# bm812i.net
KiCad netlist of a schematic drawn in EAGLE
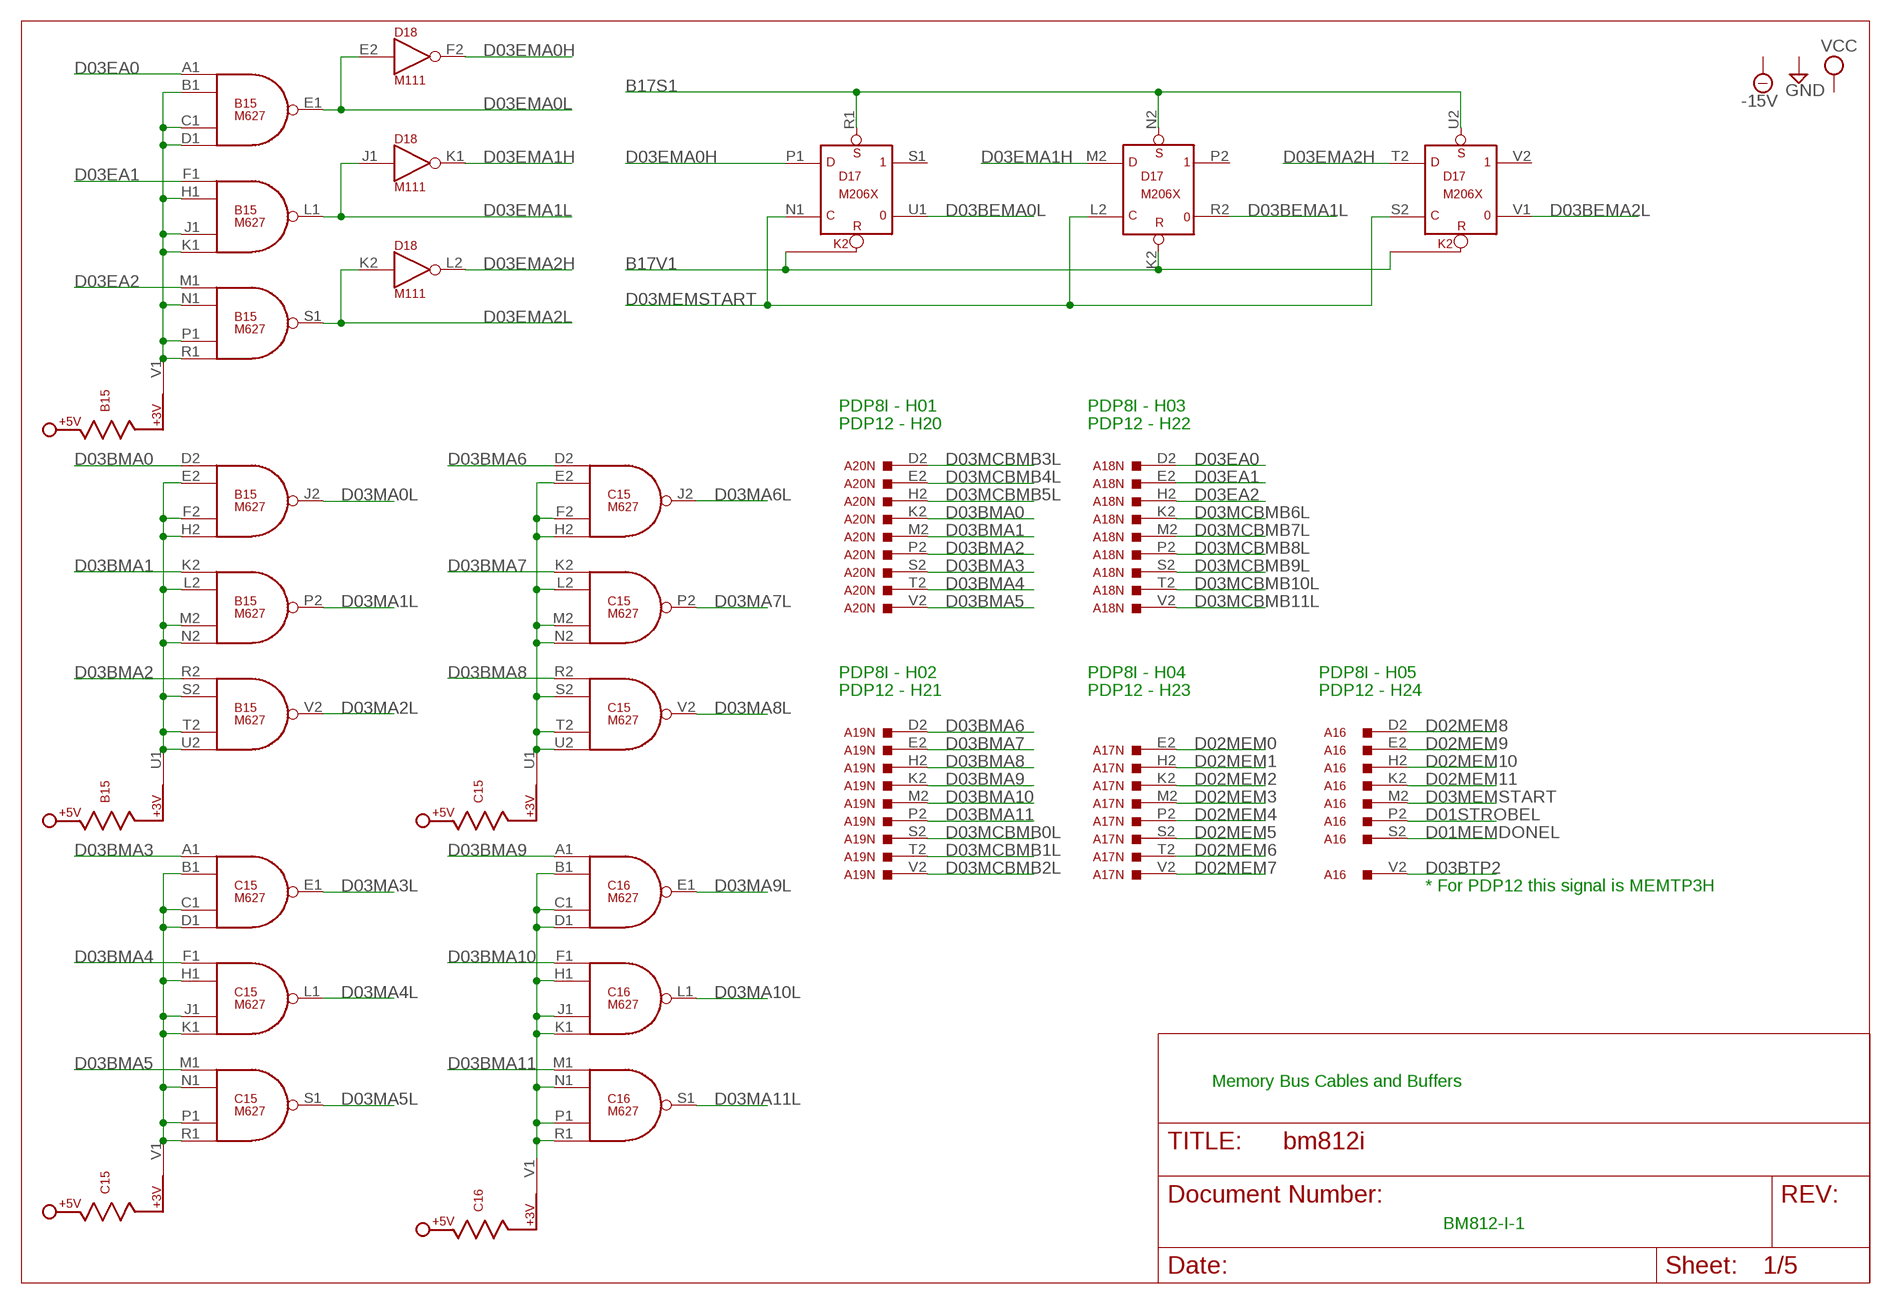
[diagram p0: schematic, sheet 1]
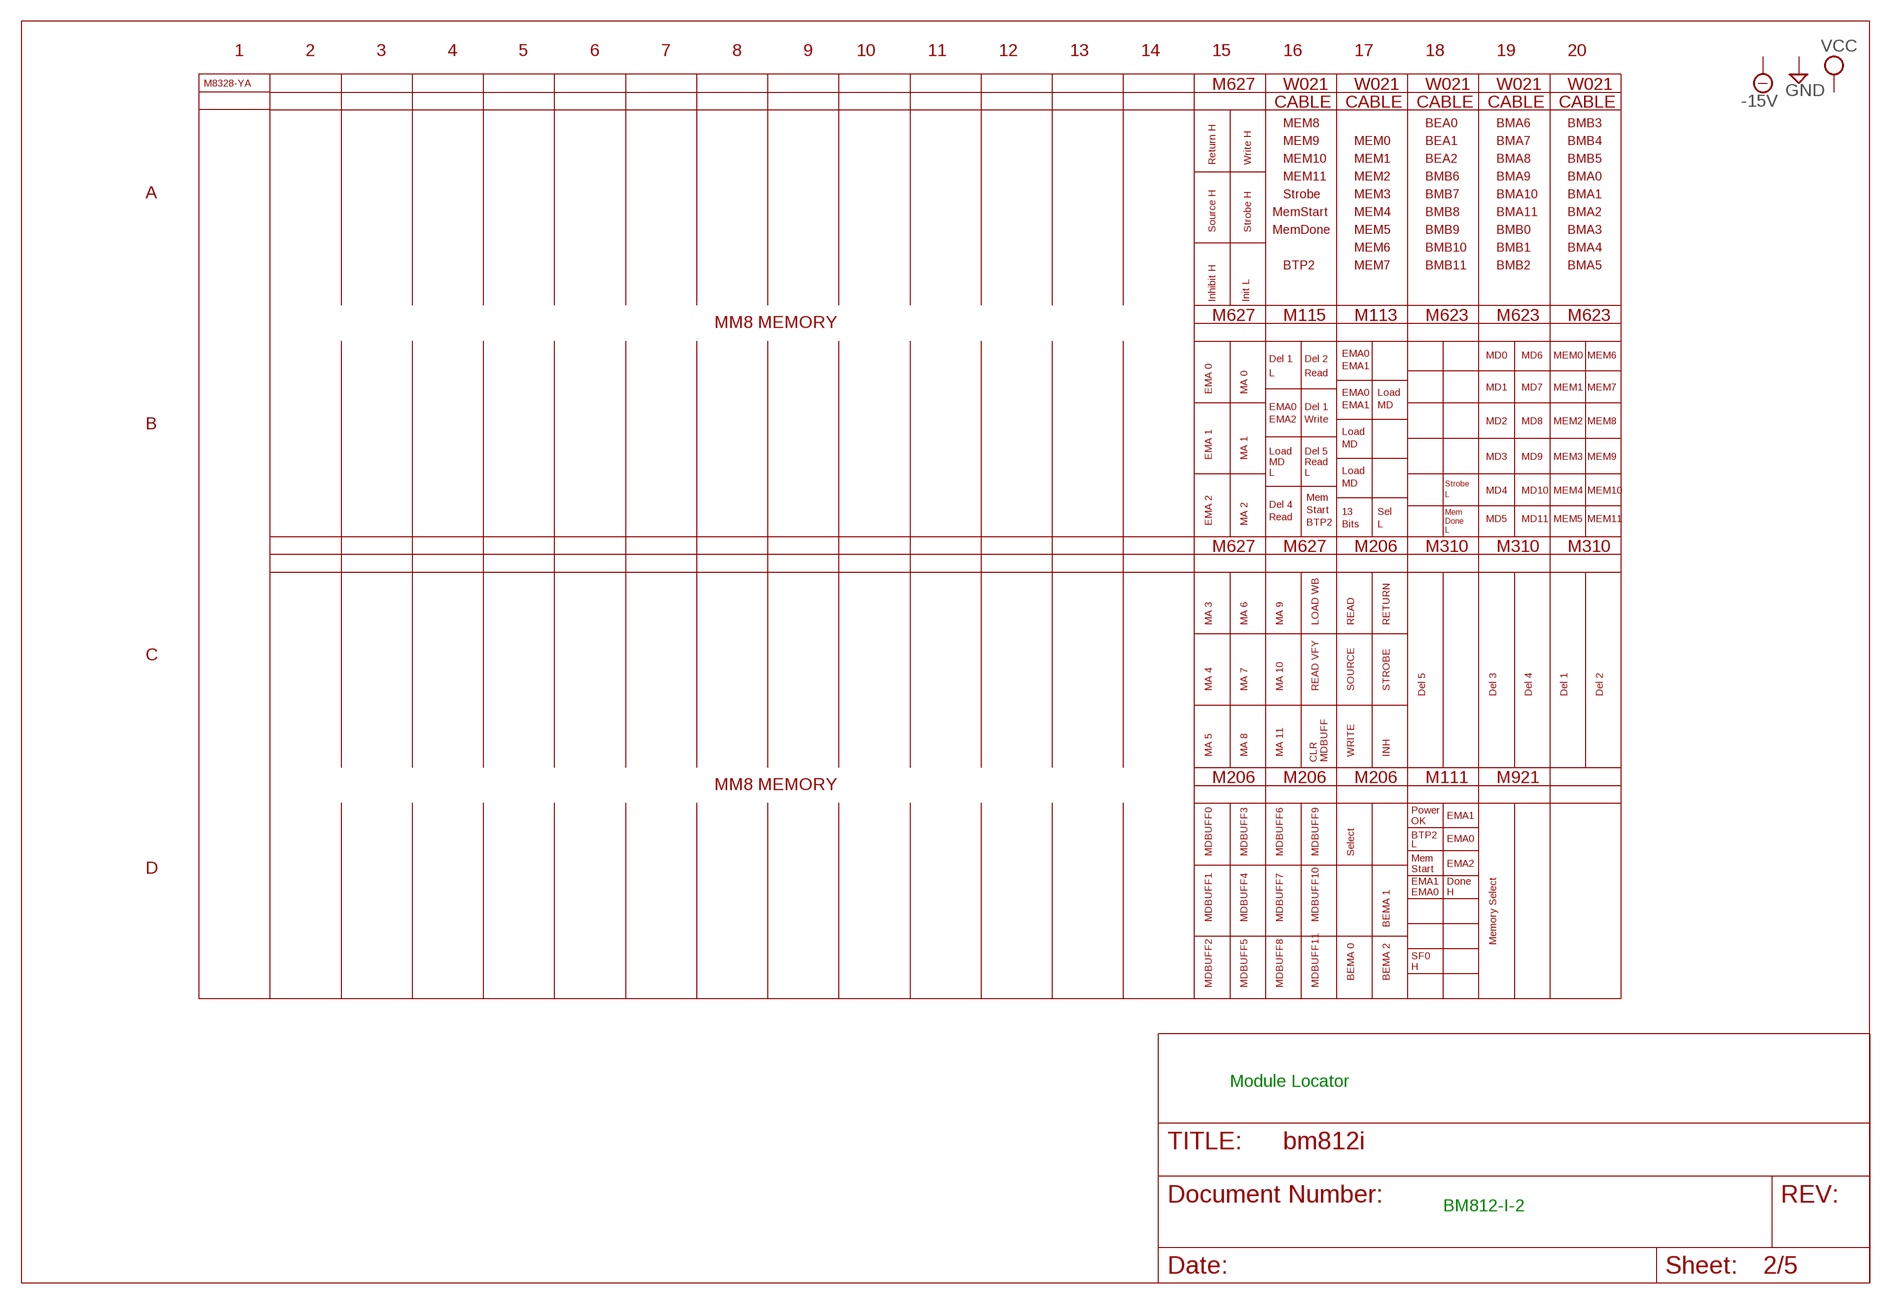
[diagram p1: schematic, sheet 2]
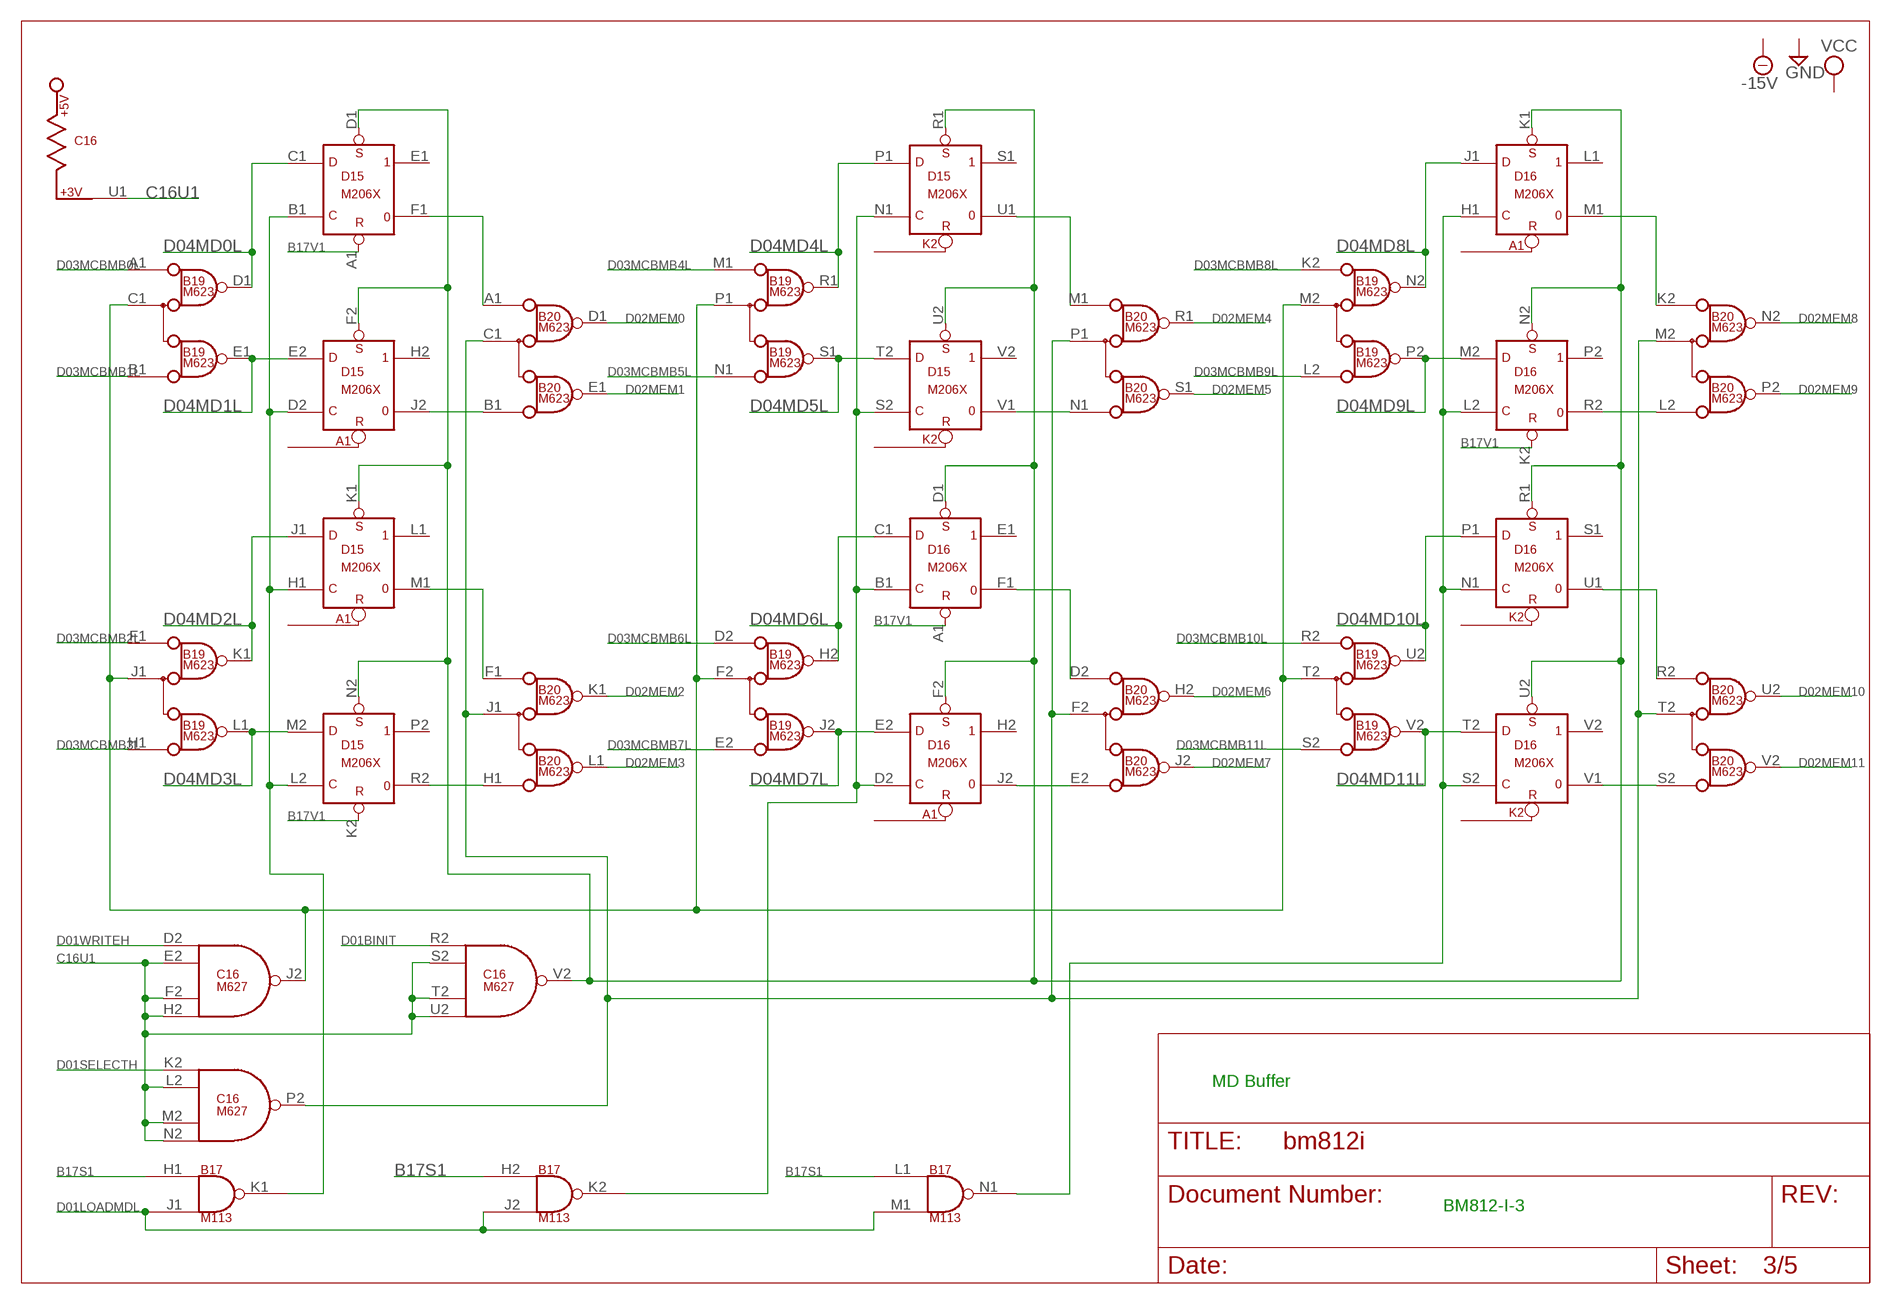
[diagram p2: schematic, sheet 3]
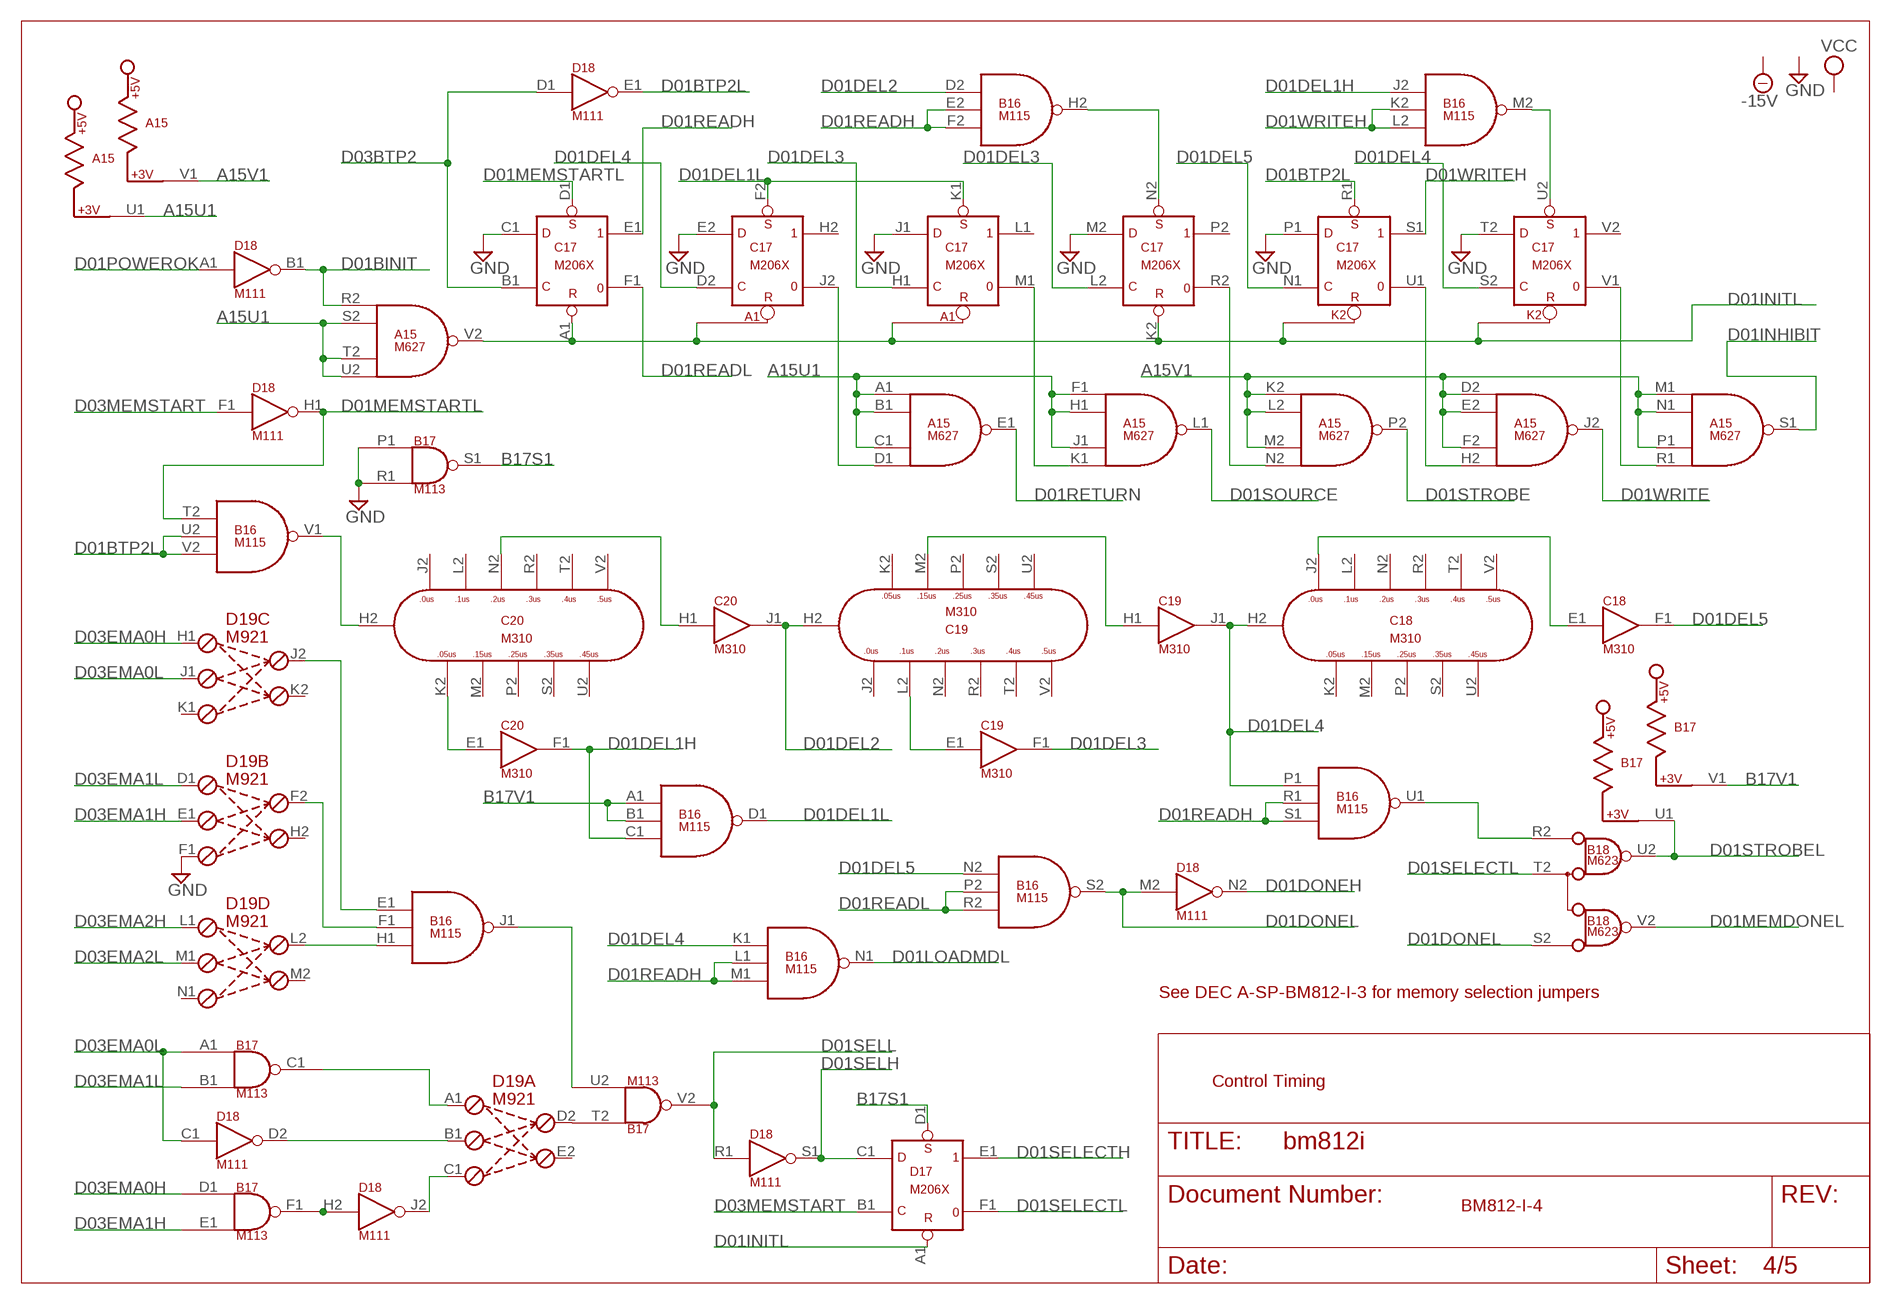
[diagram p3: schematic, sheet 4]
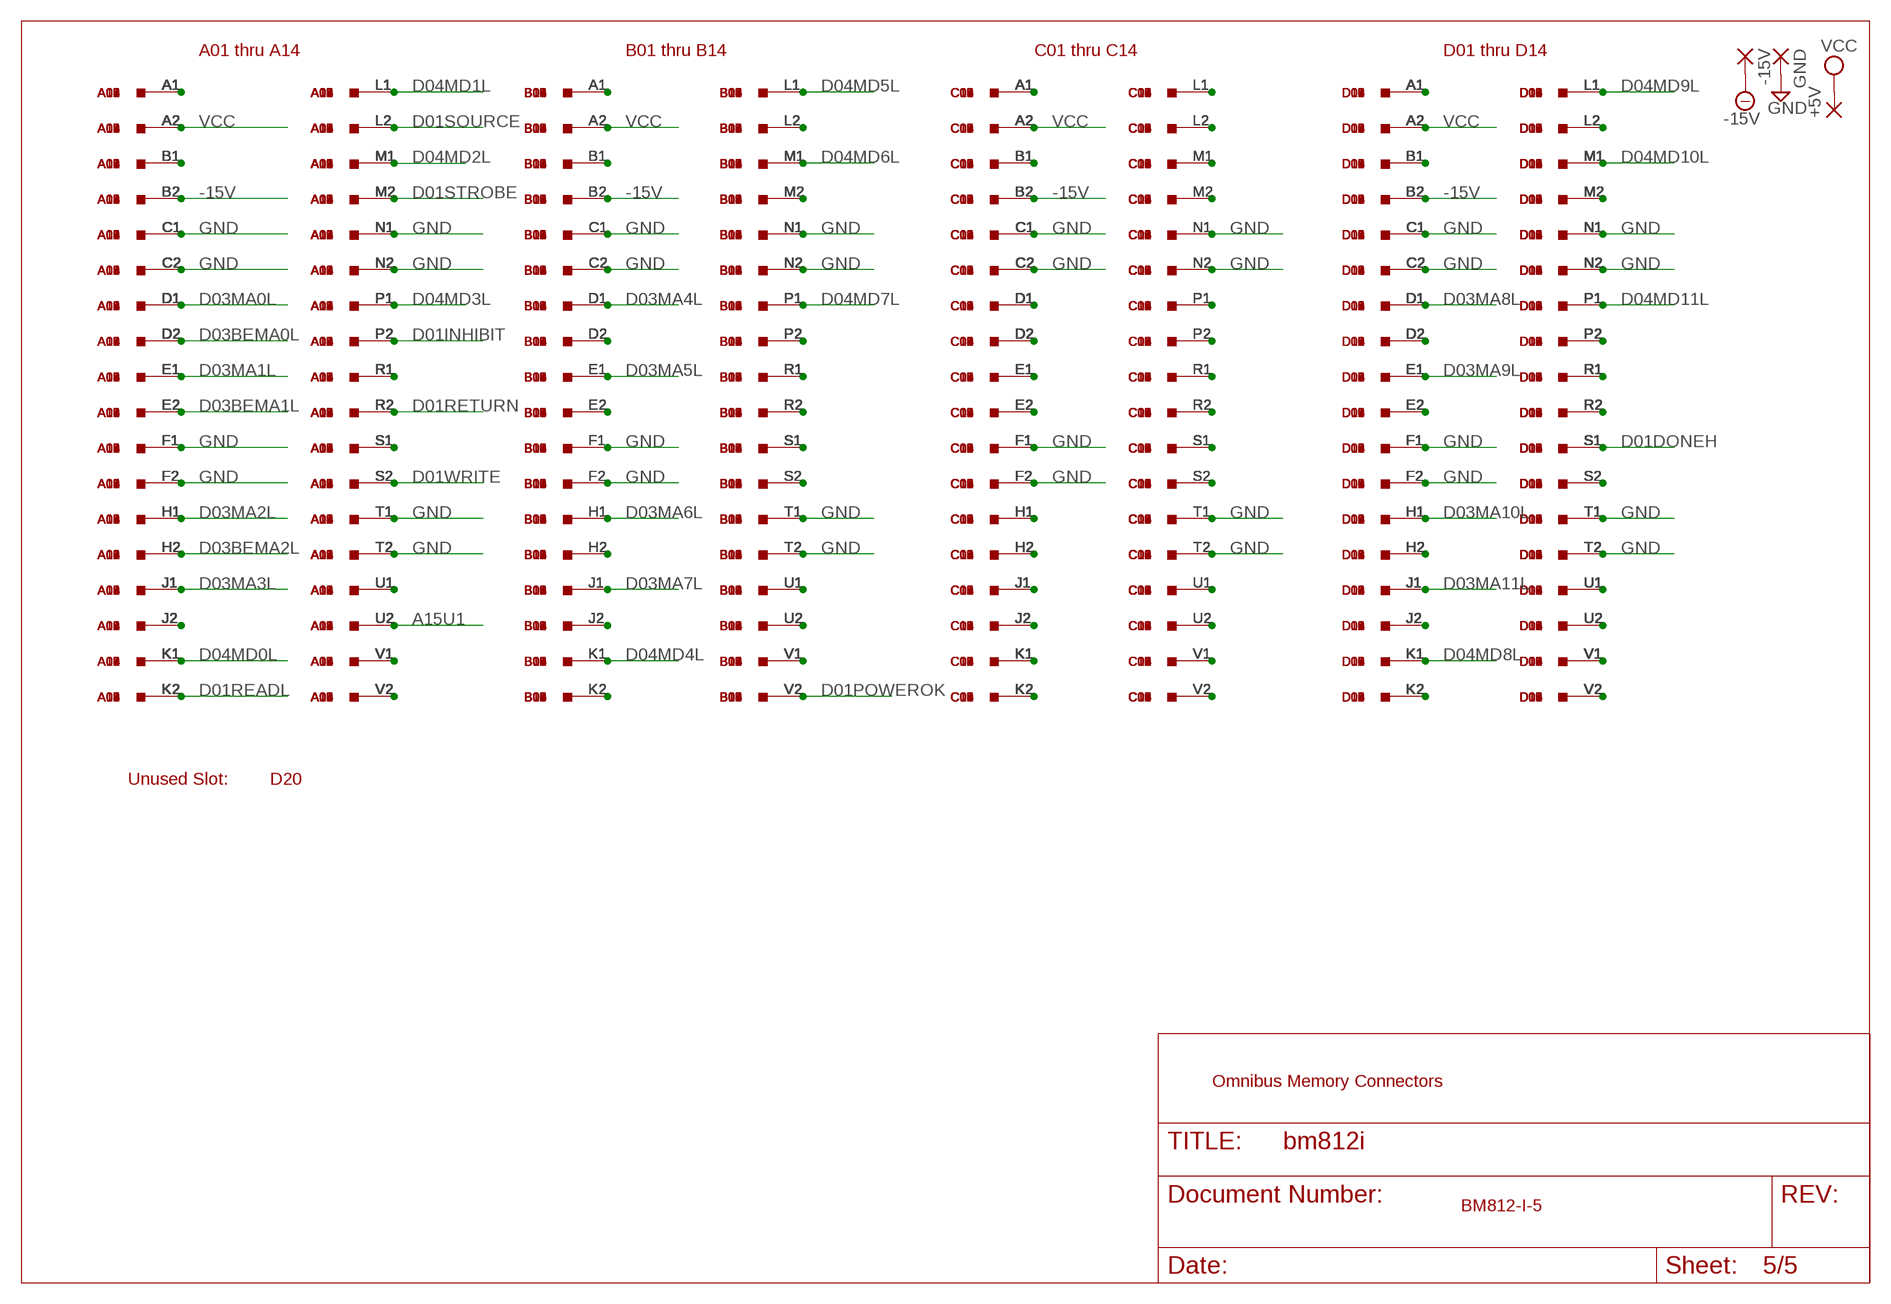
[diagram p4: schematic, sheet 5]

(export (version "E")
  (design (tool "Eeschema 10.0.6"))
  (components
    (comp (ref "+5V")
      (value "2,54/0,8")
      (footprint "eagle-import:2,54_0,8")
      (libsource (lib "eagle-import") (part "2,54/0,8"))
    )
    (comp (ref "-15V")
      (value "2,54/0,8")
      (footprint "eagle-import:2,54_0,8")
      (libsource (lib "eagle-import") (part "2,54/0,8"))
    )
    (comp (ref "A01")
      (value "M916")
      (footprint "eagle-import:H807")
      (libsource (lib "eagle-import") (part "M916"))
    )
    (comp (ref "A02")
      (value "M916")
      (footprint "eagle-import:H807")
      (libsource (lib "eagle-import") (part "M916"))
    )
    (comp (ref "A03")
      (value "M916")
      (footprint "eagle-import:H807")
      (libsource (lib "eagle-import") (part "M916"))
    )
    (comp (ref "A04")
      (value "M916")
      (footprint "eagle-import:H807")
      (libsource (lib "eagle-import") (part "M916"))
    )
    (comp (ref "A05")
      (value "M916")
      (footprint "eagle-import:H807")
      (libsource (lib "eagle-import") (part "M916"))
    )
    (comp (ref "A06")
      (value "M916")
      (footprint "eagle-import:H807")
      (libsource (lib "eagle-import") (part "M916"))
    )
    (comp (ref "A07")
      (value "M916")
      (footprint "eagle-import:H807")
      (libsource (lib "eagle-import") (part "M916"))
    )
    (comp (ref "A08")
      (value "M916")
      (footprint "eagle-import:H807")
      (libsource (lib "eagle-import") (part "M916"))
    )
    (comp (ref "A09")
      (value "M916")
      (footprint "eagle-import:H807")
      (libsource (lib "eagle-import") (part "M916"))
    )
    (comp (ref "A10")
      (value "M916")
      (footprint "eagle-import:H807")
      (libsource (lib "eagle-import") (part "M916"))
    )
    (comp (ref "A11")
      (value "M916")
      (footprint "eagle-import:H807")
      (libsource (lib "eagle-import") (part "M916"))
    )
    (comp (ref "A12")
      (value "M916")
      (footprint "eagle-import:H807")
      (libsource (lib "eagle-import") (part "M916"))
    )
    (comp (ref "A13")
      (value "M916")
      (footprint "eagle-import:H807")
      (libsource (lib "eagle-import") (part "M916"))
    )
    (comp (ref "A14")
      (value "M916")
      (footprint "eagle-import:H807")
      (libsource (lib "eagle-import") (part "M916"))
    )
    (comp (ref "B01")
      (value "M916")
      (footprint "eagle-import:H807")
      (libsource (lib "eagle-import") (part "M916"))
    )
    (comp (ref "B02")
      (value "M916")
      (footprint "eagle-import:H807")
      (libsource (lib "eagle-import") (part "M916"))
    )
    (comp (ref "B03")
      (value "M916")
      (footprint "eagle-import:H807")
      (libsource (lib "eagle-import") (part "M916"))
    )
    (comp (ref "B04")
      (value "M916")
      (footprint "eagle-import:H807")
      (libsource (lib "eagle-import") (part "M916"))
    )
    (comp (ref "B05")
      (value "M916")
      (footprint "eagle-import:H807")
      (libsource (lib "eagle-import") (part "M916"))
    )
    (comp (ref "B06")
      (value "M916")
      (footprint "eagle-import:H807")
      (libsource (lib "eagle-import") (part "M916"))
    )
    (comp (ref "B07")
      (value "M916")
      (footprint "eagle-import:H807")
      (libsource (lib "eagle-import") (part "M916"))
    )
    (comp (ref "B08")
      (value "M916")
      (footprint "eagle-import:H807")
      (libsource (lib "eagle-import") (part "M916"))
    )
    (comp (ref "B09")
      (value "M916")
      (footprint "eagle-import:H807")
      (libsource (lib "eagle-import") (part "M916"))
    )
    (comp (ref "B10")
      (value "M916")
      (footprint "eagle-import:H807")
      (libsource (lib "eagle-import") (part "M916"))
    )
    (comp (ref "B11")
      (value "M916")
      (footprint "eagle-import:H807")
      (libsource (lib "eagle-import") (part "M916"))
    )
    (comp (ref "B12")
      (value "M916")
      (footprint "eagle-import:H807")
      (libsource (lib "eagle-import") (part "M916"))
    )
    (comp (ref "B13")
      (value "M916")
      (footprint "eagle-import:H807")
      (libsource (lib "eagle-import") (part "M916"))
    )
    (comp (ref "B14")
      (value "M916")
      (footprint "eagle-import:H807")
      (libsource (lib "eagle-import") (part "M916"))
    )
    (comp (ref "C01")
      (value "M916")
      (footprint "eagle-import:H807")
      (libsource (lib "eagle-import") (part "M916"))
    )
    (comp (ref "C02")
      (value "M916")
      (footprint "eagle-import:H807")
      (libsource (lib "eagle-import") (part "M916"))
    )
    (comp (ref "C03")
      (value "M916")
      (footprint "eagle-import:H807")
      (libsource (lib "eagle-import") (part "M916"))
    )
    (comp (ref "C04")
      (value "M916")
      (footprint "eagle-import:H807")
      (libsource (lib "eagle-import") (part "M916"))
    )
    (comp (ref "C05")
      (value "M916")
      (footprint "eagle-import:H807")
      (libsource (lib "eagle-import") (part "M916"))
    )
    (comp (ref "C06")
      (value "M916")
      (footprint "eagle-import:H807")
      (libsource (lib "eagle-import") (part "M916"))
    )
    (comp (ref "C07")
      (value "M916")
      (footprint "eagle-import:H807")
      (libsource (lib "eagle-import") (part "M916"))
    )
    (comp (ref "C08")
      (value "M916")
      (footprint "eagle-import:H807")
      (libsource (lib "eagle-import") (part "M916"))
    )
    (comp (ref "C09")
      (value "M916")
      (footprint "eagle-import:H807")
      (libsource (lib "eagle-import") (part "M916"))
    )
    (comp (ref "C10")
      (value "M916")
      (footprint "eagle-import:H807")
      (libsource (lib "eagle-import") (part "M916"))
    )
    (comp (ref "C11")
      (value "M916")
      (footprint "eagle-import:H807")
      (libsource (lib "eagle-import") (part "M916"))
    )
    (comp (ref "C12")
      (value "M916")
      (footprint "eagle-import:H807")
      (libsource (lib "eagle-import") (part "M916"))
    )
    (comp (ref "C13")
      (value "M916")
      (footprint "eagle-import:H807")
      (libsource (lib "eagle-import") (part "M916"))
    )
    (comp (ref "C14")
      (value "M916")
      (footprint "eagle-import:H807")
      (libsource (lib "eagle-import") (part "M916"))
    )
    (comp (ref "D01")
      (value "M916")
      (footprint "eagle-import:H807")
      (libsource (lib "eagle-import") (part "M916"))
    )
    (comp (ref "D02")
      (value "M916")
      (footprint "eagle-import:H807")
      (libsource (lib "eagle-import") (part "M916"))
    )
    (comp (ref "D03")
      (value "M916")
      (footprint "eagle-import:H807")
      (libsource (lib "eagle-import") (part "M916"))
    )
    (comp (ref "D04")
      (value "M916")
      (footprint "eagle-import:H807")
      (libsource (lib "eagle-import") (part "M916"))
    )
    (comp (ref "D05")
      (value "M916")
      (footprint "eagle-import:H807")
      (libsource (lib "eagle-import") (part "M916"))
    )
    (comp (ref "D06")
      (value "M916")
      (footprint "eagle-import:H807")
      (libsource (lib "eagle-import") (part "M916"))
    )
    (comp (ref "D07")
      (value "M916")
      (footprint "eagle-import:H807")
      (libsource (lib "eagle-import") (part "M916"))
    )
    (comp (ref "D08")
      (value "M916")
      (footprint "eagle-import:H807")
      (libsource (lib "eagle-import") (part "M916"))
    )
    (comp (ref "D09")
      (value "M916")
      (footprint "eagle-import:H807")
      (libsource (lib "eagle-import") (part "M916"))
    )
    (comp (ref "D10")
      (value "M916")
      (footprint "eagle-import:H807")
      (libsource (lib "eagle-import") (part "M916"))
    )
    (comp (ref "D11")
      (value "M916")
      (footprint "eagle-import:H807")
      (libsource (lib "eagle-import") (part "M916"))
    )
    (comp (ref "D12")
      (value "M916")
      (footprint "eagle-import:H807")
      (libsource (lib "eagle-import") (part "M916"))
    )
    (comp (ref "D13")
      (value "M916")
      (footprint "eagle-import:H807")
      (libsource (lib "eagle-import") (part "M916"))
    )
    (comp (ref "D14")
      (value "M916")
      (footprint "eagle-import:H807")
      (libsource (lib "eagle-import") (part "M916"))
    )
    (comp (ref "D20")
      (value "H807")
      (footprint "eagle-import:H807")
      (libsource (lib "eagle-import") (part "H807"))
    )
    (comp (ref "GND")
      (value "2,54/0,8")
      (footprint "eagle-import:2,54_0,8")
      (libsource (lib "eagle-import") (part "2,54/0,8"))
    )
    (comp (ref "A16")
      (value "M903")
      (footprint "eagle-import:H807")
      (libsource (lib "eagle-import") (part "M903"))
    )
    (comp (ref "A17N")
      (value "M903")
      (footprint "eagle-import:H807")
      (libsource (lib "eagle-import") (part "M903"))
    )
    (comp (ref "A18N")
      (value "M903")
      (footprint "eagle-import:H807")
      (libsource (lib "eagle-import") (part "M903"))
    )
    (comp (ref "A19N")
      (value "M903")
      (footprint "eagle-import:H807")
      (libsource (lib "eagle-import") (part "M903"))
    )
    (comp (ref "A20N")
      (value "M903")
      (footprint "eagle-import:H807")
      (libsource (lib "eagle-import") (part "M903"))
    )
    (comp (ref "B15")
      (value "M627")
      (footprint "eagle-import:H807")
      (libsource (lib "eagle-import") (part "M627"))
    )
    (comp (ref "C15")
      (value "M627")
      (footprint "eagle-import:H807")
      (libsource (lib "eagle-import") (part "M627"))
    )
    (comp (ref "C16")
      (value "M627")
      (footprint "eagle-import:H807")
      (libsource (lib "eagle-import") (part "M627"))
    )
    (comp (ref "D17")
      (value "M206X")
      (footprint "eagle-import:H807")
      (libsource (lib "eagle-import") (part "M206X"))
    )
    (comp (ref "D18")
      (value "M111")
      (footprint "eagle-import:H807")
      (libsource (lib "eagle-import") (part "M111"))
    )
    (comp (ref "A15")
      (value "M627")
      (footprint "eagle-import:H807")
      (libsource (lib "eagle-import") (part "M627"))
    )
    (comp (ref "B16")
      (value "M115")
      (footprint "eagle-import:H807")
      (libsource (lib "eagle-import") (part "M115"))
    )
    (comp (ref "B17")
      (value "M113")
      (footprint "eagle-import:H807")
      (libsource (lib "eagle-import") (part "M113"))
    )
    (comp (ref "B18")
      (value "M623")
      (footprint "eagle-import:H807")
      (libsource (lib "eagle-import") (part "M623"))
    )
    (comp (ref "C17")
      (value "M206X")
      (footprint "eagle-import:H807")
      (libsource (lib "eagle-import") (part "M206X"))
    )
    (comp (ref "C18")
      (value "M310")
      (footprint "eagle-import:H807")
      (libsource (lib "eagle-import") (part "M310"))
    )
    (comp (ref "C19")
      (value "M310")
      (footprint "eagle-import:H807")
      (libsource (lib "eagle-import") (part "M310"))
    )
    (comp (ref "C20")
      (value "M310")
      (footprint "eagle-import:H807")
      (libsource (lib "eagle-import") (part "M310"))
    )
    (comp (ref "D19")
      (value "M921")
      (footprint "eagle-import:H807")
      (libsource (lib "eagle-import") (part "M921"))
    )
    (comp (ref "B19")
      (value "M623")
      (footprint "eagle-import:H807")
      (libsource (lib "eagle-import") (part "M623"))
    )
    (comp (ref "B20")
      (value "M623")
      (footprint "eagle-import:H807")
      (libsource (lib "eagle-import") (part "M623"))
    )
    (comp (ref "D15")
      (value "M206X")
      (footprint "eagle-import:H807")
      (libsource (lib "eagle-import") (part "M206X"))
    )
    (comp (ref "D16")
      (value "M206X")
      (footprint "eagle-import:H807")
      (libsource (lib "eagle-import") (part "M206X"))
    )
  )
  (nets
    (net (code "1") (name "-15V") (class "Default")
      (node (ref "-15V") (pin "1") (pinfunction "P_1") (pintype "passive"))
      (node (ref "A01") (pin "B2") (pinfunction "P$2_B2") (pintype "bidirectional"))
      (node (ref "A02") (pin "B2") (pinfunction "P$2_B2") (pintype "bidirectional"))
      (node (ref "A03") (pin "B2") (pinfunction "P$2_B2") (pintype "bidirectional"))
      (node (ref "A04") (pin "B2") (pinfunction "P$2_B2") (pintype "bidirectional"))
      (node (ref "A05") (pin "B2") (pinfunction "P$2_B2") (pintype "bidirectional"))
      (node (ref "A06") (pin "B2") (pinfunction "P$2_B2") (pintype "bidirectional"))
      (node (ref "A07") (pin "B2") (pinfunction "P$2_B2") (pintype "bidirectional"))
      (node (ref "A08") (pin "B2") (pinfunction "P$2_B2") (pintype "bidirectional"))
      (node (ref "A09") (pin "B2") (pinfunction "P$2_B2") (pintype "bidirectional"))
      (node (ref "A10") (pin "B2") (pinfunction "P$2_B2") (pintype "bidirectional"))
      (node (ref "A11") (pin "B2") (pinfunction "P$2_B2") (pintype "bidirectional"))
      (node (ref "A12") (pin "B2") (pinfunction "P$2_B2") (pintype "bidirectional"))
      (node (ref "A13") (pin "B2") (pinfunction "P$2_B2") (pintype "bidirectional"))
      (node (ref "A14") (pin "B2") (pinfunction "P$2_B2") (pintype "bidirectional"))
      (node (ref "B01") (pin "B2") (pinfunction "P$2_B2") (pintype "bidirectional"))
      (node (ref "B02") (pin "B2") (pinfunction "P$2_B2") (pintype "bidirectional"))
      (node (ref "B03") (pin "B2") (pinfunction "P$2_B2") (pintype "bidirectional"))
      (node (ref "B04") (pin "B2") (pinfunction "P$2_B2") (pintype "bidirectional"))
      (node (ref "B05") (pin "B2") (pinfunction "P$2_B2") (pintype "bidirectional"))
      (node (ref "B06") (pin "B2") (pinfunction "P$2_B2") (pintype "bidirectional"))
      (node (ref "B07") (pin "B2") (pinfunction "P$2_B2") (pintype "bidirectional"))
      (node (ref "B08") (pin "B2") (pinfunction "P$2_B2") (pintype "bidirectional"))
      (node (ref "B09") (pin "B2") (pinfunction "P$2_B2") (pintype "bidirectional"))
      (node (ref "B10") (pin "B2") (pinfunction "P$2_B2") (pintype "bidirectional"))
      (node (ref "B11") (pin "B2") (pinfunction "P$2_B2") (pintype "bidirectional"))
      (node (ref "B12") (pin "B2") (pinfunction "P$2_B2") (pintype "bidirectional"))
      (node (ref "B13") (pin "B2") (pinfunction "P$2_B2") (pintype "bidirectional"))
      (node (ref "B14") (pin "B2") (pinfunction "P$2_B2") (pintype "bidirectional"))
      (node (ref "C01") (pin "B2") (pinfunction "P$2_B2") (pintype "bidirectional"))
      (node (ref "C02") (pin "B2") (pinfunction "P$2_B2") (pintype "bidirectional"))
      (node (ref "C03") (pin "B2") (pinfunction "P$2_B2") (pintype "bidirectional"))
      (node (ref "C04") (pin "B2") (pinfunction "P$2_B2") (pintype "bidirectional"))
      (node (ref "C05") (pin "B2") (pinfunction "P$2_B2") (pintype "bidirectional"))
      (node (ref "C06") (pin "B2") (pinfunction "P$2_B2") (pintype "bidirectional"))
      (node (ref "C07") (pin "B2") (pinfunction "P$2_B2") (pintype "bidirectional"))
      (node (ref "C08") (pin "B2") (pinfunction "P$2_B2") (pintype "bidirectional"))
      (node (ref "C09") (pin "B2") (pinfunction "P$2_B2") (pintype "bidirectional"))
      (node (ref "C10") (pin "B2") (pinfunction "P$2_B2") (pintype "bidirectional"))
      (node (ref "C11") (pin "B2") (pinfunction "P$2_B2") (pintype "bidirectional"))
      (node (ref "C12") (pin "B2") (pinfunction "P$2_B2") (pintype "bidirectional"))
      (node (ref "C13") (pin "B2") (pinfunction "P$2_B2") (pintype "bidirectional"))
      (node (ref "C14") (pin "B2") (pinfunction "P$2_B2") (pintype "bidirectional"))
      (node (ref "D01") (pin "B2") (pinfunction "P$2_B2") (pintype "bidirectional"))
      (node (ref "D02") (pin "B2") (pinfunction "P$2_B2") (pintype "bidirectional"))
      (node (ref "D03") (pin "B2") (pinfunction "P$2_B2") (pintype "bidirectional"))
      (node (ref "D04") (pin "B2") (pinfunction "P$2_B2") (pintype "bidirectional"))
      (node (ref "D05") (pin "B2") (pinfunction "P$2_B2") (pintype "bidirectional"))
      (node (ref "D06") (pin "B2") (pinfunction "P$2_B2") (pintype "bidirectional"))
      (node (ref "D07") (pin "B2") (pinfunction "P$2_B2") (pintype "bidirectional"))
      (node (ref "D08") (pin "B2") (pinfunction "P$2_B2") (pintype "bidirectional"))
      (node (ref "D09") (pin "B2") (pinfunction "P$2_B2") (pintype "bidirectional"))
      (node (ref "D10") (pin "B2") (pinfunction "P$2_B2") (pintype "bidirectional"))
      (node (ref "D11") (pin "B2") (pinfunction "P$2_B2") (pintype "bidirectional"))
      (node (ref "D12") (pin "B2") (pinfunction "P$2_B2") (pintype "bidirectional"))
      (node (ref "D13") (pin "B2") (pinfunction "P$2_B2") (pintype "bidirectional"))
      (node (ref "D14") (pin "B2") (pinfunction "P$2_B2") (pintype "bidirectional"))
    )
    (net (code "2") (name "A15U1") (class "Default")
      (node (ref "A01") (pin "U2") (pinfunction "P$2_U2") (pintype "bidirectional"))
      (node (ref "A02") (pin "U2") (pinfunction "P$2_U2") (pintype "bidirectional"))
      (node (ref "A03") (pin "U2") (pinfunction "P$2_U2") (pintype "bidirectional"))
      (node (ref "A04") (pin "U2") (pinfunction "P$2_U2") (pintype "bidirectional"))
      (node (ref "A05") (pin "U2") (pinfunction "P$2_U2") (pintype "bidirectional"))
      (node (ref "A06") (pin "U2") (pinfunction "P$2_U2") (pintype "bidirectional"))
      (node (ref "A07") (pin "U2") (pinfunction "P$2_U2") (pintype "bidirectional"))
      (node (ref "A08") (pin "U2") (pinfunction "P$2_U2") (pintype "bidirectional"))
      (node (ref "A09") (pin "U2") (pinfunction "P$2_U2") (pintype "bidirectional"))
      (node (ref "A10") (pin "U2") (pinfunction "P$2_U2") (pintype "bidirectional"))
      (node (ref "A11") (pin "U2") (pinfunction "P$2_U2") (pintype "bidirectional"))
      (node (ref "A12") (pin "U2") (pinfunction "P$2_U2") (pintype "bidirectional"))
      (node (ref "A13") (pin "U2") (pinfunction "P$2_U2") (pintype "bidirectional"))
      (node (ref "A14") (pin "U2") (pinfunction "P$2_U2") (pintype "bidirectional"))
      (node (ref "A15") (pin "A1") (pinfunction "IN1_A1") (pintype "input"))
      (node (ref "A15") (pin "B1") (pinfunction "IN2_B1") (pintype "input"))
      (node (ref "A15") (pin "C1") (pinfunction "IN3_C1") (pintype "input"))
      (node (ref "A15") (pin "F1") (pinfunction "IN1_F1") (pintype "input"))
      (node (ref "A15") (pin "H1") (pinfunction "IN2_H1") (pintype "input"))
      (node (ref "A15") (pin "J1") (pinfunction "IN3_J1") (pintype "input"))
      (node (ref "A15") (pin "S2") (pinfunction "IN2_S2") (pintype "input"))
      (node (ref "A15") (pin "T2") (pinfunction "IN3_T2") (pintype "input"))
      (node (ref "A15") (pin "U1") (pinfunction "P$1_U1") (pintype "passive"))
      (node (ref "A15") (pin "U2") (pinfunction "IN4_U2") (pintype "input"))
    )
    (net (code "3") (name "A15V1") (class "Default")
      (node (ref "A15") (pin "D2") (pinfunction "IN1_D2") (pintype "input"))
      (node (ref "A15") (pin "E2") (pinfunction "IN2_E2") (pintype "input"))
      (node (ref "A15") (pin "F2") (pinfunction "IN3_F2") (pintype "input"))
      (node (ref "A15") (pin "K2") (pinfunction "IN1_K2") (pintype "input"))
      (node (ref "A15") (pin "L2") (pinfunction "IN2_L2") (pintype "input"))
      (node (ref "A15") (pin "M1") (pinfunction "IN1_M1") (pintype "input"))
      (node (ref "A15") (pin "M2") (pinfunction "IN3_M2") (pintype "input"))
      (node (ref "A15") (pin "N1") (pinfunction "IN2_N1") (pintype "input"))
      (node (ref "A15") (pin "P1") (pinfunction "IN3_P1") (pintype "input"))
      (node (ref "A15") (pin "V1") (pinfunction "P$1_V1") (pintype "passive"))
    )
    (net (code "4") (name "B17S1") (class "Default")
      (node (ref "B17") (pin "H1") (pinfunction "IN1_H1") (pintype "input"))
      (node (ref "B17") (pin "H2") (pinfunction "IN1_H2") (pintype "input"))
      (node (ref "B17") (pin "L1") (pinfunction "IN1_L1") (pintype "input"))
      (node (ref "B17") (pin "S1") (pinfunction "OUT_S1") (pintype "output"))
      (node (ref "D17") (pin "D1") (pinfunction "S_D1") (pintype "input"))
      (node (ref "D17") (pin "N2") (pinfunction "S_N2") (pintype "input"))
      (node (ref "D17") (pin "R1") (pinfunction "S_R1") (pintype "input"))
      (node (ref "D17") (pin "U2") (pinfunction "S_U2") (pintype "input"))
    )
    (net (code "5") (name "B17V1") (class "Default")
      (node (ref "B16") (pin "A1") (pinfunction "IN1_A1") (pintype "input"))
      (node (ref "B16") (pin "B1") (pinfunction "IN2_B1") (pintype "input"))
      (node (ref "B17") (pin "V1") (pinfunction "P$1_V1") (pintype "passive"))
      (node (ref "D15") (pin "A1") (pinfunction "R_A1") (pintype "input"))
      (node (ref "D15") (pin "K2") (pinfunction "R_K2") (pintype "input"))
      (node (ref "D16") (pin "A1") (pinfunction "R_A1") (pintype "input"))
      (node (ref "D16") (pin "K2") (pinfunction "R_K2") (pintype "input"))
      (node (ref "D17") (pin "K2") (pinfunction "R_K2") (pintype "input"))
    )
    (net (code "6") (name "C16U1") (class "Default")
      (node (ref "C16") (pin "E2") (pinfunction "IN2_E2") (pintype "input"))
      (node (ref "C16") (pin "F2") (pinfunction "IN3_F2") (pintype "input"))
      (node (ref "C16") (pin "H2") (pinfunction "IN4_H2") (pintype "input"))
      (node (ref "C16") (pin "L2") (pinfunction "IN2_L2") (pintype "input"))
      (node (ref "C16") (pin "M2") (pinfunction "IN3_M2") (pintype "input"))
      (node (ref "C16") (pin "N2") (pinfunction "IN4_N2") (pintype "input"))
      (node (ref "C16") (pin "S2") (pinfunction "IN2_S2") (pintype "input"))
      (node (ref "C16") (pin "T2") (pinfunction "IN3_T2") (pintype "input"))
      (node (ref "C16") (pin "U1") (pinfunction "P$1_U1") (pintype "passive"))
      (node (ref "C16") (pin "U2") (pinfunction "IN4_U2") (pintype "input"))
    )
    (net (code "7") (name "D01BINIT") (class "Default")
      (node (ref "A15") (pin "R2") (pinfunction "IN1_R2") (pintype "input"))
      (node (ref "C16") (pin "R2") (pinfunction "IN1_R2") (pintype "input"))
      (node (ref "D18") (pin "B1") (pinfunction "OUT_B1") (pintype "output"))
    )
    (net (code "8") (name "D01BTP2L") (class "Default")
      (node (ref "B16") (pin "U2") (pinfunction "IN2_U2") (pintype "input"))
      (node (ref "B16") (pin "V2") (pinfunction "IN3_V2") (pintype "input"))
      (node (ref "C17") (pin "R1") (pinfunction "S_R1") (pintype "input"))
      (node (ref "D18") (pin "E1") (pinfunction "OUT_E1") (pintype "output"))
    )
    (net (code "9") (name "D01DEL1H") (class "Default")
      (node (ref "B16") (pin "C1") (pinfunction "IN3_C1") (pintype "input"))
      (node (ref "B16") (pin "J2") (pinfunction "IN1_J2") (pintype "input"))
      (node (ref "C20") (pin "F1") (pinfunction "OUT_F1") (pintype "output"))
    )
    (net (code "10") (name "D01DEL1L") (class "Default")
      (node (ref "B16") (pin "D1") (pinfunction "OUT_D1") (pintype "output"))
      (node (ref "C17") (pin "F2") (pinfunction "S_F2") (pintype "input"))
      (node (ref "C17") (pin "K1") (pinfunction "S_K1") (pintype "input"))
    )
    (net (code "11") (name "D01DEL2") (class "Default")
      (node (ref "B16") (pin "D2") (pinfunction "IN1_D2") (pintype "input"))
      (node (ref "C19") (pin "H2") (pinfunction "H2_H2") (pintype "input"))
      (node (ref "C20") (pin "J1") (pinfunction "OUT_J1") (pintype "output"))
    )
    (net (code "12") (name "D01DEL3") (class "Default")
      (node (ref "C17") (pin "H1") (pinfunction "C_H1") (pintype "input"))
      (node (ref "C17") (pin "L2") (pinfunction "C_L2") (pintype "input"))
      (node (ref "C19") (pin "F1") (pinfunction "OUT_F1") (pintype "output"))
    )
    (net (code "13") (name "D01DEL4") (class "Default")
      (node (ref "B16") (pin "K1") (pinfunction "IN1_K1") (pintype "input"))
      (node (ref "B16") (pin "P1") (pinfunction "IN1_P1") (pintype "input"))
      (node (ref "C17") (pin "D2") (pinfunction "C_D2") (pintype "input"))
      (node (ref "C17") (pin "S2") (pinfunction "C_S2") (pintype "input"))
      (node (ref "C18") (pin "H2") (pinfunction "H2_H2") (pintype "input"))
      (node (ref "C19") (pin "J1") (pinfunction "OUT_J1") (pintype "output"))
    )
    (net (code "14") (name "D01DEL5") (class "Default")
      (node (ref "B16") (pin "N2") (pinfunction "IN1_N2") (pintype "input"))
      (node (ref "C17") (pin "N1") (pinfunction "C_N1") (pintype "input"))
      (node (ref "C18") (pin "F1") (pinfunction "OUT_F1") (pintype "output"))
    )
    (net (code "15") (name "D01DONEH") (class "Default")
      (node (ref "D01") (pin "S1") (pinfunction "P$2_S1") (pintype "bidirectional"))
      (node (ref "D02") (pin "S1") (pinfunction "P$2_S1") (pintype "bidirectional"))
      (node (ref "D03") (pin "S1") (pinfunction "P$2_S1") (pintype "bidirectional"))
      (node (ref "D04") (pin "S1") (pinfunction "P$2_S1") (pintype "bidirectional"))
      (node (ref "D05") (pin "S1") (pinfunction "P$2_S1") (pintype "bidirectional"))
      (node (ref "D06") (pin "S1") (pinfunction "P$2_S1") (pintype "bidirectional"))
      (node (ref "D07") (pin "S1") (pinfunction "P$2_S1") (pintype "bidirectional"))
      (node (ref "D08") (pin "S1") (pinfunction "P$2_S1") (pintype "bidirectional"))
      (node (ref "D09") (pin "S1") (pinfunction "P$2_S1") (pintype "bidirectional"))
      (node (ref "D10") (pin "S1") (pinfunction "P$2_S1") (pintype "bidirectional"))
      (node (ref "D11") (pin "S1") (pinfunction "P$2_S1") (pintype "bidirectional"))
      (node (ref "D12") (pin "S1") (pinfunction "P$2_S1") (pintype "bidirectional"))
      (node (ref "D13") (pin "S1") (pinfunction "P$2_S1") (pintype "bidirectional"))
      (node (ref "D14") (pin "S1") (pinfunction "P$2_S1") (pintype "bidirectional"))
      (node (ref "D18") (pin "N2") (pinfunction "OUT_N2") (pintype "output"))
    )
    (net (code "16") (name "D01DONEL") (class "Default")
      (node (ref "B16") (pin "S2") (pinfunction "OUT_S2") (pintype "output"))
      (node (ref "B18") (pin "S2") (pinfunction "B_S2") (pintype "input"))
      (node (ref "D18") (pin "M2") (pinfunction "IN_M2") (pintype "input"))
    )
    (net (code "17") (name "D01INHIBIT") (class "Default")
      (node (ref "A01") (pin "P2") (pinfunction "P$2_P2") (pintype "bidirectional"))
      (node (ref "A02") (pin "P2") (pinfunction "P$2_P2") (pintype "bidirectional"))
      (node (ref "A03") (pin "P2") (pinfunction "P$2_P2") (pintype "bidirectional"))
      (node (ref "A04") (pin "P2") (pinfunction "P$2_P2") (pintype "bidirectional"))
      (node (ref "A05") (pin "P2") (pinfunction "P$2_P2") (pintype "bidirectional"))
      (node (ref "A06") (pin "P2") (pinfunction "P$2_P2") (pintype "bidirectional"))
      (node (ref "A07") (pin "P2") (pinfunction "P$2_P2") (pintype "bidirectional"))
      (node (ref "A08") (pin "P2") (pinfunction "P$2_P2") (pintype "bidirectional"))
      (node (ref "A09") (pin "P2") (pinfunction "P$2_P2") (pintype "bidirectional"))
      (node (ref "A10") (pin "P2") (pinfunction "P$2_P2") (pintype "bidirectional"))
      (node (ref "A11") (pin "P2") (pinfunction "P$2_P2") (pintype "bidirectional"))
      (node (ref "A12") (pin "P2") (pinfunction "P$2_P2") (pintype "bidirectional"))
      (node (ref "A13") (pin "P2") (pinfunction "P$2_P2") (pintype "bidirectional"))
      (node (ref "A14") (pin "P2") (pinfunction "P$2_P2") (pintype "bidirectional"))
      (node (ref "A15") (pin "S1") (pinfunction "OUT_S1") (pintype "output"))
    )
    (net (code "18") (name "D01INITL") (class "Default")
      (node (ref "A15") (pin "V2") (pinfunction "OUT_V2") (pintype "output"))
      (node (ref "C17") (pin "A1") (pinfunction "R_A1") (pintype "input"))
      (node (ref "C17") (pin "K2") (pinfunction "R_K2") (pintype "input"))
      (node (ref "D17") (pin "A1") (pinfunction "R_A1") (pintype "input"))
    )
    (net (code "19") (name "D01LOADMDL") (class "Default")
      (node (ref "B16") (pin "N1") (pinfunction "OUT_N1") (pintype "output"))
      (node (ref "B17") (pin "J1") (pinfunction "IN2_J1") (pintype "input"))
      (node (ref "B17") (pin "J2") (pinfunction "IN2_J2") (pintype "input"))
      (node (ref "B17") (pin "M1") (pinfunction "IN2_M1") (pintype "input"))
    )
    (net (code "20") (name "D01MEMDONEL") (class "Default")
      (node (ref "A16") (pin "S2") (pinfunction "P$2_S2") (pintype "bidirectional"))
      (node (ref "B18") (pin "V2") (pinfunction "E_V2") (pintype "open_collector"))
    )
    (net (code "21") (name "D01MEMSTARTL") (class "Default")
      (node (ref "B16") (pin "T2") (pinfunction "IN1_T2") (pintype "input"))
      (node (ref "C17") (pin "D1") (pinfunction "S_D1") (pintype "input"))
      (node (ref "D18") (pin "H1") (pinfunction "OUT_H1") (pintype "output"))
    )
    (net (code "22") (name "D01POWEROK") (class "Default")
      (node (ref "B01") (pin "V2") (pinfunction "P$2_V2") (pintype "bidirectional"))
      (node (ref "B02") (pin "V2") (pinfunction "P$2_V2") (pintype "bidirectional"))
      (node (ref "B03") (pin "V2") (pinfunction "P$2_V2") (pintype "bidirectional"))
      (node (ref "B04") (pin "V2") (pinfunction "P$2_V2") (pintype "bidirectional"))
      (node (ref "B05") (pin "V2") (pinfunction "P$2_V2") (pintype "bidirectional"))
      (node (ref "B06") (pin "V2") (pinfunction "P$2_V2") (pintype "bidirectional"))
      (node (ref "B07") (pin "V2") (pinfunction "P$2_V2") (pintype "bidirectional"))
      (node (ref "B08") (pin "V2") (pinfunction "P$2_V2") (pintype "bidirectional"))
      (node (ref "B09") (pin "V2") (pinfunction "P$2_V2") (pintype "bidirectional"))
      (node (ref "B10") (pin "V2") (pinfunction "P$2_V2") (pintype "bidirectional"))
      (node (ref "B11") (pin "V2") (pinfunction "P$2_V2") (pintype "bidirectional"))
      (node (ref "B12") (pin "V2") (pinfunction "P$2_V2") (pintype "bidirectional"))
      (node (ref "B13") (pin "V2") (pinfunction "P$2_V2") (pintype "bidirectional"))
      (node (ref "B14") (pin "V2") (pinfunction "P$2_V2") (pintype "bidirectional"))
      (node (ref "D18") (pin "A1") (pinfunction "IN_A1") (pintype "input"))
    )
    (net (code "23") (name "D01READH") (class "Default")
      (node (ref "B16") (pin "E2") (pinfunction "IN2_E2") (pintype "input"))
      (node (ref "B16") (pin "F2") (pinfunction "IN3_F2") (pintype "input"))
      (node (ref "B16") (pin "L1") (pinfunction "IN2_L1") (pintype "input"))
      (node (ref "B16") (pin "M1") (pinfunction "IN3_M1") (pintype "input"))
      (node (ref "B16") (pin "R1") (pinfunction "IN2_R1") (pintype "input"))
      (node (ref "B16") (pin "S1") (pinfunction "IN3_S1") (pintype "input"))
      (node (ref "C17") (pin "E1") (pinfunction "1_E1") (pintype "output"))
    )
    (net (code "24") (name "D01READL") (class "Default")
      (node (ref "A01") (pin "K2") (pinfunction "P$2_K2") (pintype "bidirectional"))
      (node (ref "A02") (pin "K2") (pinfunction "P$2_K2") (pintype "bidirectional"))
      (node (ref "A03") (pin "K2") (pinfunction "P$2_K2") (pintype "bidirectional"))
      (node (ref "A04") (pin "K2") (pinfunction "P$2_K2") (pintype "bidirectional"))
      (node (ref "A05") (pin "K2") (pinfunction "P$2_K2") (pintype "bidirectional"))
      (node (ref "A06") (pin "K2") (pinfunction "P$2_K2") (pintype "bidirectional"))
      (node (ref "A07") (pin "K2") (pinfunction "P$2_K2") (pintype "bidirectional"))
      (node (ref "A08") (pin "K2") (pinfunction "P$2_K2") (pintype "bidirectional"))
      (node (ref "A09") (pin "K2") (pinfunction "P$2_K2") (pintype "bidirectional"))
      (node (ref "A10") (pin "K2") (pinfunction "P$2_K2") (pintype "bidirectional"))
      (node (ref "A11") (pin "K2") (pinfunction "P$2_K2") (pintype "bidirectional"))
      (node (ref "A12") (pin "K2") (pinfunction "P$2_K2") (pintype "bidirectional"))
      (node (ref "A13") (pin "K2") (pinfunction "P$2_K2") (pintype "bidirectional"))
      (node (ref "A14") (pin "K2") (pinfunction "P$2_K2") (pintype "bidirectional"))
      (node (ref "B16") (pin "P2") (pinfunction "IN2_P2") (pintype "input"))
      (node (ref "B16") (pin "R2") (pinfunction "IN3_R2") (pintype "input"))
      (node (ref "C17") (pin "F1") (pinfunction "0_F1") (pintype "output"))
    )
    (net (code "25") (name "D01RETURN") (class "Default")
      (node (ref "A01") (pin "R2") (pinfunction "P$2_R2") (pintype "bidirectional"))
      (node (ref "A02") (pin "R2") (pinfunction "P$2_R2") (pintype "bidirectional"))
      (node (ref "A03") (pin "R2") (pinfunction "P$2_R2") (pintype "bidirectional"))
      (node (ref "A04") (pin "R2") (pinfunction "P$2_R2") (pintype "bidirectional"))
      (node (ref "A05") (pin "R2") (pinfunction "P$2_R2") (pintype "bidirectional"))
      (node (ref "A06") (pin "R2") (pinfunction "P$2_R2") (pintype "bidirectional"))
      (node (ref "A07") (pin "R2") (pinfunction "P$2_R2") (pintype "bidirectional"))
      (node (ref "A08") (pin "R2") (pinfunction "P$2_R2") (pintype "bidirectional"))
      (node (ref "A09") (pin "R2") (pinfunction "P$2_R2") (pintype "bidirectional"))
      (node (ref "A10") (pin "R2") (pinfunction "P$2_R2") (pintype "bidirectional"))
      (node (ref "A11") (pin "R2") (pinfunction "P$2_R2") (pintype "bidirectional"))
      (node (ref "A12") (pin "R2") (pinfunction "P$2_R2") (pintype "bidirectional"))
      (node (ref "A13") (pin "R2") (pinfunction "P$2_R2") (pintype "bidirectional"))
      (node (ref "A14") (pin "R2") (pinfunction "P$2_R2") (pintype "bidirectional"))
      (node (ref "A15") (pin "E1") (pinfunction "OUT_E1") (pintype "output"))
    )
    (net (code "26") (name "D01SELECTH") (class "Default")
      (node (ref "C16") (pin "K2") (pinfunction "IN1_K2") (pintype "input"))
      (node (ref "D17") (pin "E1") (pinfunction "1_E1") (pintype "output"))
    )
    (net (code "27") (name "D01SELECTL") (class "Default")
      (node (ref "B18") (pin "T2") (pinfunction "C_T2") (pintype "input"))
      (node (ref "D17") (pin "F1") (pinfunction "0_F1") (pintype "output"))
    )
    (net (code "28") (name "D01SELH") (class "Default")
      (node (ref "D17") (pin "C1") (pinfunction "D_C1") (pintype "input"))
      (node (ref "D18") (pin "S1") (pinfunction "OUT_S1") (pintype "output"))
    )
    (net (code "29") (name "D01SELL") (class "Default")
      (node (ref "B17") (pin "V2") (pinfunction "OUT_V2") (pintype "output"))
      (node (ref "D18") (pin "R1") (pinfunction "IN_R1") (pintype "input"))
    )
    (net (code "30") (name "D01SOURCE") (class "Default")
      (node (ref "A01") (pin "L2") (pinfunction "P$2_L2") (pintype "bidirectional"))
      (node (ref "A02") (pin "L2") (pinfunction "P$2_L2") (pintype "bidirectional"))
      (node (ref "A03") (pin "L2") (pinfunction "P$2_L2") (pintype "bidirectional"))
      (node (ref "A04") (pin "L2") (pinfunction "P$2_L2") (pintype "bidirectional"))
      (node (ref "A05") (pin "L2") (pinfunction "P$2_L2") (pintype "bidirectional"))
      (node (ref "A06") (pin "L2") (pinfunction "P$2_L2") (pintype "bidirectional"))
      (node (ref "A07") (pin "L2") (pinfunction "P$2_L2") (pintype "bidirectional"))
      (node (ref "A08") (pin "L2") (pinfunction "P$2_L2") (pintype "bidirectional"))
      (node (ref "A09") (pin "L2") (pinfunction "P$2_L2") (pintype "bidirectional"))
      (node (ref "A10") (pin "L2") (pinfunction "P$2_L2") (pintype "bidirectional"))
      (node (ref "A11") (pin "L2") (pinfunction "P$2_L2") (pintype "bidirectional"))
      (node (ref "A12") (pin "L2") (pinfunction "P$2_L2") (pintype "bidirectional"))
      (node (ref "A13") (pin "L2") (pinfunction "P$2_L2") (pintype "bidirectional"))
      (node (ref "A14") (pin "L2") (pinfunction "P$2_L2") (pintype "bidirectional"))
      (node (ref "A15") (pin "L1") (pinfunction "OUT_L1") (pintype "output"))
    )
    (net (code "31") (name "D01STROBE") (class "Default")
      (node (ref "A01") (pin "M2") (pinfunction "P$2_M2") (pintype "bidirectional"))
      (node (ref "A02") (pin "M2") (pinfunction "P$2_M2") (pintype "bidirectional"))
      (node (ref "A03") (pin "M2") (pinfunction "P$2_M2") (pintype "bidirectional"))
      (node (ref "A04") (pin "M2") (pinfunction "P$2_M2") (pintype "bidirectional"))
      (node (ref "A05") (pin "M2") (pinfunction "P$2_M2") (pintype "bidirectional"))
      (node (ref "A06") (pin "M2") (pinfunction "P$2_M2") (pintype "bidirectional"))
      (node (ref "A07") (pin "M2") (pinfunction "P$2_M2") (pintype "bidirectional"))
      (node (ref "A08") (pin "M2") (pinfunction "P$2_M2") (pintype "bidirectional"))
      (node (ref "A09") (pin "M2") (pinfunction "P$2_M2") (pintype "bidirectional"))
      (node (ref "A10") (pin "M2") (pinfunction "P$2_M2") (pintype "bidirectional"))
      (node (ref "A11") (pin "M2") (pinfunction "P$2_M2") (pintype "bidirectional"))
      (node (ref "A12") (pin "M2") (pinfunction "P$2_M2") (pintype "bidirectional"))
      (node (ref "A13") (pin "M2") (pinfunction "P$2_M2") (pintype "bidirectional"))
      (node (ref "A14") (pin "M2") (pinfunction "P$2_M2") (pintype "bidirectional"))
      (node (ref "A15") (pin "P2") (pinfunction "OUT_P2") (pintype "output"))
    )
    (net (code "32") (name "D01STROBEL") (class "Default")
      (node (ref "A16") (pin "P2") (pinfunction "P$2_P2") (pintype "bidirectional"))
      (node (ref "B17") (pin "U1") (pinfunction "P$1_U1") (pintype "passive"))
      (node (ref "B18") (pin "U2") (pinfunction "D_U2") (pintype "open_collector"))
    )
    (net (code "33") (name "D01WRITE") (class "Default")
      (node (ref "A01") (pin "S2") (pinfunction "P$2_S2") (pintype "bidirectional"))
      (node (ref "A02") (pin "S2") (pinfunction "P$2_S2") (pintype "bidirectional"))
      (node (ref "A03") (pin "S2") (pinfunction "P$2_S2") (pintype "bidirectional"))
      (node (ref "A04") (pin "S2") (pinfunction "P$2_S2") (pintype "bidirectional"))
      (node (ref "A05") (pin "S2") (pinfunction "P$2_S2") (pintype "bidirectional"))
      (node (ref "A06") (pin "S2") (pinfunction "P$2_S2") (pintype "bidirectional"))
      (node (ref "A07") (pin "S2") (pinfunction "P$2_S2") (pintype "bidirectional"))
      (node (ref "A08") (pin "S2") (pinfunction "P$2_S2") (pintype "bidirectional"))
      (node (ref "A09") (pin "S2") (pinfunction "P$2_S2") (pintype "bidirectional"))
      (node (ref "A10") (pin "S2") (pinfunction "P$2_S2") (pintype "bidirectional"))
      (node (ref "A11") (pin "S2") (pinfunction "P$2_S2") (pintype "bidirectional"))
      (node (ref "A12") (pin "S2") (pinfunction "P$2_S2") (pintype "bidirectional"))
      (node (ref "A13") (pin "S2") (pinfunction "P$2_S2") (pintype "bidirectional"))
      (node (ref "A14") (pin "S2") (pinfunction "P$2_S2") (pintype "bidirectional"))
      (node (ref "A15") (pin "J2") (pinfunction "OUT_J2") (pintype "output"))
    )
    (net (code "34") (name "D01WRITEH") (class "Default")
      (node (ref "B16") (pin "K2") (pinfunction "IN2_K2") (pintype "input"))
      (node (ref "B16") (pin "L2") (pinfunction "IN3_L2") (pintype "input"))
      (node (ref "C16") (pin "D2") (pinfunction "IN1_D2") (pintype "input"))
      (node (ref "C17") (pin "S1") (pinfunction "1_S1") (pintype "output"))
    )
    (net (code "35") (name "D02MEM0") (class "Default")
      (node (ref "A17N") (pin "E2") (pinfunction "P$2_E2") (pintype "bidirectional"))
      (node (ref "B20") (pin "D1") (pinfunction "D_D1") (pintype "open_collector"))
    )
    (net (code "36") (name "D02MEM1") (class "Default")
      (node (ref "A17N") (pin "H2") (pinfunction "P$2_H2") (pintype "bidirectional"))
      (node (ref "B20") (pin "E1") (pinfunction "E_E1") (pintype "open_collector"))
    )
    (net (code "37") (name "D02MEM2") (class "Default")
      (node (ref "A17N") (pin "K2") (pinfunction "P$2_K2") (pintype "bidirectional"))
      (node (ref "B20") (pin "K1") (pinfunction "D_K1") (pintype "open_collector"))
    )
    (net (code "38") (name "D02MEM3") (class "Default")
      (node (ref "A17N") (pin "M2") (pinfunction "P$2_M2") (pintype "bidirectional"))
      (node (ref "B20") (pin "L1") (pinfunction "E_L1") (pintype "open_collector"))
    )
    (net (code "39") (name "D02MEM4") (class "Default")
      (node (ref "A17N") (pin "P2") (pinfunction "P$2_P2") (pintype "bidirectional"))
      (node (ref "B20") (pin "R1") (pinfunction "D_R1") (pintype "open_collector"))
    )
    (net (code "40") (name "D02MEM5") (class "Default")
      (node (ref "A17N") (pin "S2") (pinfunction "P$2_S2") (pintype "bidirectional"))
      (node (ref "B20") (pin "S1") (pinfunction "E_S1") (pintype "open_collector"))
    )
    (net (code "41") (name "D02MEM6") (class "Default")
      (node (ref "A17N") (pin "T2") (pinfunction "P$2_T2") (pintype "bidirectional"))
      (node (ref "B20") (pin "H2") (pinfunction "D_H2") (pintype "open_collector"))
    )
    (net (code "42") (name "D02MEM7") (class "Default")
      (node (ref "A17N") (pin "V2") (pinfunction "P$2_V2") (pintype "bidirectional"))
      (node (ref "B20") (pin "J2") (pinfunction "E_J2") (pintype "open_collector"))
    )
    (net (code "43") (name "D02MEM8") (class "Default")
      (node (ref "A16") (pin "D2") (pinfunction "P$2_D2") (pintype "bidirectional"))
      (node (ref "B20") (pin "N2") (pinfunction "D_N2") (pintype "open_collector"))
    )
    (net (code "44") (name "D02MEM9") (class "Default")
      (node (ref "A16") (pin "E2") (pinfunction "P$2_E2") (pintype "bidirectional"))
      (node (ref "B20") (pin "P2") (pinfunction "E_P2") (pintype "open_collector"))
    )
    (net (code "45") (name "D02MEM10") (class "Default")
      (node (ref "A16") (pin "H2") (pinfunction "P$2_H2") (pintype "bidirectional"))
      (node (ref "B20") (pin "U2") (pinfunction "D_U2") (pintype "open_collector"))
    )
    (net (code "46") (name "D02MEM11") (class "Default")
      (node (ref "A16") (pin "K2") (pinfunction "P$2_K2") (pintype "bidirectional"))
      (node (ref "B20") (pin "V2") (pinfunction "E_V2") (pintype "open_collector"))
    )
    (net (code "47") (name "D03BEMA0L") (class "Default")
      (node (ref "A01") (pin "D2") (pinfunction "P$2_D2") (pintype "bidirectional"))
      (node (ref "A02") (pin "D2") (pinfunction "P$2_D2") (pintype "bidirectional"))
      (node (ref "A03") (pin "D2") (pinfunction "P$2_D2") (pintype "bidirectional"))
      (node (ref "A04") (pin "D2") (pinfunction "P$2_D2") (pintype "bidirectional"))
      (node (ref "A05") (pin "D2") (pinfunction "P$2_D2") (pintype "bidirectional"))
      (node (ref "A06") (pin "D2") (pinfunction "P$2_D2") (pintype "bidirectional"))
      (node (ref "A07") (pin "D2") (pinfunction "P$2_D2") (pintype "bidirectional"))
      (node (ref "A08") (pin "D2") (pinfunction "P$2_D2") (pintype "bidirectional"))
      (node (ref "A09") (pin "D2") (pinfunction "P$2_D2") (pintype "bidirectional"))
      (node (ref "A10") (pin "D2") (pinfunction "P$2_D2") (pintype "bidirectional"))
      (node (ref "A11") (pin "D2") (pinfunction "P$2_D2") (pintype "bidirectional"))
      (node (ref "A12") (pin "D2") (pinfunction "P$2_D2") (pintype "bidirectional"))
      (node (ref "A13") (pin "D2") (pinfunction "P$2_D2") (pintype "bidirectional"))
      (node (ref "A14") (pin "D2") (pinfunction "P$2_D2") (pintype "bidirectional"))
      (node (ref "D17") (pin "U1") (pinfunction "0_U1") (pintype "output"))
    )
    (net (code "48") (name "D03BEMA1L") (class "Default")
      (node (ref "A01") (pin "E2") (pinfunction "P$2_E2") (pintype "bidirectional"))
      (node (ref "A02") (pin "E2") (pinfunction "P$2_E2") (pintype "bidirectional"))
      (node (ref "A03") (pin "E2") (pinfunction "P$2_E2") (pintype "bidirectional"))
      (node (ref "A04") (pin "E2") (pinfunction "P$2_E2") (pintype "bidirectional"))
      (node (ref "A05") (pin "E2") (pinfunction "P$2_E2") (pintype "bidirectional"))
      (node (ref "A06") (pin "E2") (pinfunction "P$2_E2") (pintype "bidirectional"))
      (node (ref "A07") (pin "E2") (pinfunction "P$2_E2") (pintype "bidirectional"))
      (node (ref "A08") (pin "E2") (pinfunction "P$2_E2") (pintype "bidirectional"))
      (node (ref "A09") (pin "E2") (pinfunction "P$2_E2") (pintype "bidirectional"))
      (node (ref "A10") (pin "E2") (pinfunction "P$2_E2") (pintype "bidirectional"))
      (node (ref "A11") (pin "E2") (pinfunction "P$2_E2") (pintype "bidirectional"))
      (node (ref "A12") (pin "E2") (pinfunction "P$2_E2") (pintype "bidirectional"))
      (node (ref "A13") (pin "E2") (pinfunction "P$2_E2") (pintype "bidirectional"))
      (node (ref "A14") (pin "E2") (pinfunction "P$2_E2") (pintype "bidirectional"))
      (node (ref "D17") (pin "R2") (pinfunction "0_R2") (pintype "output"))
    )
    (net (code "49") (name "D03BEMA2L") (class "Default")
      (node (ref "A01") (pin "H2") (pinfunction "P$2_H2") (pintype "bidirectional"))
      (node (ref "A02") (pin "H2") (pinfunction "P$2_H2") (pintype "bidirectional"))
      (node (ref "A03") (pin "H2") (pinfunction "P$2_H2") (pintype "bidirectional"))
      (node (ref "A04") (pin "H2") (pinfunction "P$2_H2") (pintype "bidirectional"))
      (node (ref "A05") (pin "H2") (pinfunction "P$2_H2") (pintype "bidirectional"))
      (node (ref "A06") (pin "H2") (pinfunction "P$2_H2") (pintype "bidirectional"))
      (node (ref "A07") (pin "H2") (pinfunction "P$2_H2") (pintype "bidirectional"))
      (node (ref "A08") (pin "H2") (pinfunction "P$2_H2") (pintype "bidirectional"))
      (node (ref "A09") (pin "H2") (pinfunction "P$2_H2") (pintype "bidirectional"))
      (node (ref "A10") (pin "H2") (pinfunction "P$2_H2") (pintype "bidirectional"))
      (node (ref "A11") (pin "H2") (pinfunction "P$2_H2") (pintype "bidirectional"))
      (node (ref "A12") (pin "H2") (pinfunction "P$2_H2") (pintype "bidirectional"))
      (node (ref "A13") (pin "H2") (pinfunction "P$2_H2") (pintype "bidirectional"))
      (node (ref "A14") (pin "H2") (pinfunction "P$2_H2") (pintype "bidirectional"))
      (node (ref "D17") (pin "V1") (pinfunction "0_V1") (pintype "output"))
    )
    (net (code "50") (name "D03BMA0") (class "Default")
      (node (ref "A20N") (pin "K2") (pinfunction "P$2_K2") (pintype "bidirectional"))
      (node (ref "B15") (pin "D2") (pinfunction "IN1_D2") (pintype "input"))
    )
    (net (code "51") (name "D03BMA1") (class "Default")
      (node (ref "A20N") (pin "M2") (pinfunction "P$2_M2") (pintype "bidirectional"))
      (node (ref "B15") (pin "K2") (pinfunction "IN1_K2") (pintype "input"))
    )
    (net (code "52") (name "D03BMA2") (class "Default")
      (node (ref "A20N") (pin "P2") (pinfunction "P$2_P2") (pintype "bidirectional"))
      (node (ref "B15") (pin "R2") (pinfunction "IN1_R2") (pintype "input"))
    )
    (net (code "53") (name "D03BMA3") (class "Default")
      (node (ref "A20N") (pin "S2") (pinfunction "P$2_S2") (pintype "bidirectional"))
      (node (ref "C15") (pin "A1") (pinfunction "IN1_A1") (pintype "input"))
    )
    (net (code "54") (name "D03BMA4") (class "Default")
      (node (ref "A20N") (pin "T2") (pinfunction "P$2_T2") (pintype "bidirectional"))
      (node (ref "C15") (pin "F1") (pinfunction "IN1_F1") (pintype "input"))
    )
    (net (code "55") (name "D03BMA5") (class "Default")
      (node (ref "A20N") (pin "V2") (pinfunction "P$2_V2") (pintype "bidirectional"))
      (node (ref "C15") (pin "M1") (pinfunction "IN1_M1") (pintype "input"))
    )
    (net (code "56") (name "D03BMA6") (class "Default")
      (node (ref "A19N") (pin "D2") (pinfunction "P$2_D2") (pintype "bidirectional"))
      (node (ref "C15") (pin "D2") (pinfunction "IN1_D2") (pintype "input"))
    )
    (net (code "57") (name "D03BMA7") (class "Default")
      (node (ref "A19N") (pin "E2") (pinfunction "P$2_E2") (pintype "bidirectional"))
      (node (ref "C15") (pin "K2") (pinfunction "IN1_K2") (pintype "input"))
    )
    (net (code "58") (name "D03BMA8") (class "Default")
      (node (ref "A19N") (pin "H2") (pinfunction "P$2_H2") (pintype "bidirectional"))
      (node (ref "C15") (pin "R2") (pinfunction "IN1_R2") (pintype "input"))
    )
    (net (code "59") (name "D03BMA9") (class "Default")
      (node (ref "A19N") (pin "K2") (pinfunction "P$2_K2") (pintype "bidirectional"))
      (node (ref "C16") (pin "A1") (pinfunction "IN1_A1") (pintype "input"))
    )
    (net (code "60") (name "D03BMA10") (class "Default")
      (node (ref "A19N") (pin "M2") (pinfunction "P$2_M2") (pintype "bidirectional"))
      (node (ref "C16") (pin "F1") (pinfunction "IN1_F1") (pintype "input"))
    )
    (net (code "61") (name "D03BMA11") (class "Default")
      (node (ref "A19N") (pin "P2") (pinfunction "P$2_P2") (pintype "bidirectional"))
      (node (ref "C16") (pin "M1") (pinfunction "IN1_M1") (pintype "input"))
    )
    (net (code "62") (name "D03BTP2") (class "Default")
      (node (ref "A16") (pin "V2") (pinfunction "P$2_V2") (pintype "bidirectional"))
      (node (ref "C17") (pin "B1") (pinfunction "C_B1") (pintype "input"))
      (node (ref "D18") (pin "D1") (pinfunction "IN_D1") (pintype "input"))
    )
    (net (code "63") (name "D03EA0") (class "Default")
      (node (ref "A18N") (pin "D2") (pinfunction "P$2_D2") (pintype "bidirectional"))
      (node (ref "B15") (pin "A1") (pinfunction "IN1_A1") (pintype "input"))
    )
    (net (code "64") (name "D03EA1") (class "Default")
      (node (ref "A18N") (pin "E2") (pinfunction "P$2_E2") (pintype "bidirectional"))
      (node (ref "B15") (pin "F1") (pinfunction "IN1_F1") (pintype "input"))
    )
    (net (code "65") (name "D03EA2") (class "Default")
      (node (ref "A18N") (pin "H2") (pinfunction "P$2_H2") (pintype "bidirectional"))
      (node (ref "B15") (pin "M1") (pinfunction "IN1_M1") (pintype "input"))
    )
    (net (code "66") (name "D03EMA0H") (class "Default")
      (node (ref "B17") (pin "D1") (pinfunction "IN1_D1") (pintype "input"))
      (node (ref "D17") (pin "P1") (pinfunction "D_P1") (pintype "input"))
      (node (ref "D18") (pin "F2") (pinfunction "OUT_F2") (pintype "output"))
      (node (ref "D19") (pin "H1") (pinfunction "L1_H1") (pintype "bidirectional"))
    )
    (net (code "67") (name "D03EMA0L") (class "Default")
      (node (ref "B15") (pin "E1") (pinfunction "OUT_E1") (pintype "output"))
      (node (ref "B17") (pin "A1") (pinfunction "IN1_A1") (pintype "input"))
      (node (ref "D18") (pin "C1") (pinfunction "IN_C1") (pintype "input"))
      (node (ref "D18") (pin "E2") (pinfunction "IN_E2") (pintype "input"))
      (node (ref "D19") (pin "J1") (pinfunction "L2_J1") (pintype "bidirectional"))
    )
    (net (code "68") (name "D03EMA1H") (class "Default")
      (node (ref "B17") (pin "E1") (pinfunction "IN2_E1") (pintype "input"))
      (node (ref "D17") (pin "M2") (pinfunction "D_M2") (pintype "input"))
      (node (ref "D18") (pin "K1") (pinfunction "OUT_K1") (pintype "output"))
      (node (ref "D19") (pin "E1") (pinfunction "L2_E1") (pintype "bidirectional"))
    )
    (net (code "69") (name "D03EMA1L") (class "Default")
      (node (ref "B15") (pin "L1") (pinfunction "OUT_L1") (pintype "output"))
      (node (ref "B17") (pin "B1") (pinfunction "IN2_B1") (pintype "input"))
      (node (ref "D18") (pin "J1") (pinfunction "IN_J1") (pintype "input"))
      (node (ref "D19") (pin "D1") (pinfunction "L1_D1") (pintype "bidirectional"))
    )
    (net (code "70") (name "D03EMA2H") (class "Default")
      (node (ref "D17") (pin "T2") (pinfunction "D_T2") (pintype "input"))
      (node (ref "D18") (pin "L2") (pinfunction "OUT_L2") (pintype "output"))
      (node (ref "D19") (pin "L1") (pinfunction "L1_L1") (pintype "bidirectional"))
    )
    (net (code "71") (name "D03EMA2L") (class "Default")
      (node (ref "B15") (pin "S1") (pinfunction "OUT_S1") (pintype "output"))
      (node (ref "D18") (pin "K2") (pinfunction "IN_K2") (pintype "input"))
      (node (ref "D19") (pin "M1") (pinfunction "L2_M1") (pintype "bidirectional"))
    )
    (net (code "72") (name "D03MA0L") (class "Default")
      (node (ref "A01") (pin "D1") (pinfunction "P$2_D1") (pintype "bidirectional"))
      (node (ref "A02") (pin "D1") (pinfunction "P$2_D1") (pintype "bidirectional"))
      (node (ref "A03") (pin "D1") (pinfunction "P$2_D1") (pintype "bidirectional"))
      (node (ref "A04") (pin "D1") (pinfunction "P$2_D1") (pintype "bidirectional"))
      (node (ref "A05") (pin "D1") (pinfunction "P$2_D1") (pintype "bidirectional"))
      (node (ref "A06") (pin "D1") (pinfunction "P$2_D1") (pintype "bidirectional"))
      (node (ref "A07") (pin "D1") (pinfunction "P$2_D1") (pintype "bidirectional"))
      (node (ref "A08") (pin "D1") (pinfunction "P$2_D1") (pintype "bidirectional"))
      (node (ref "A09") (pin "D1") (pinfunction "P$2_D1") (pintype "bidirectional"))
      (node (ref "A10") (pin "D1") (pinfunction "P$2_D1") (pintype "bidirectional"))
      (node (ref "A11") (pin "D1") (pinfunction "P$2_D1") (pintype "bidirectional"))
      (node (ref "A12") (pin "D1") (pinfunction "P$2_D1") (pintype "bidirectional"))
      (node (ref "A13") (pin "D1") (pinfunction "P$2_D1") (pintype "bidirectional"))
      (node (ref "A14") (pin "D1") (pinfunction "P$2_D1") (pintype "bidirectional"))
      (node (ref "B15") (pin "J2") (pinfunction "OUT_J2") (pintype "output"))
    )
    (net (code "73") (name "D03MA1L") (class "Default")
      (node (ref "A01") (pin "E1") (pinfunction "P$2_E1") (pintype "bidirectional"))
      (node (ref "A02") (pin "E1") (pinfunction "P$2_E1") (pintype "bidirectional"))
      (node (ref "A03") (pin "E1") (pinfunction "P$2_E1") (pintype "bidirectional"))
      (node (ref "A04") (pin "E1") (pinfunction "P$2_E1") (pintype "bidirectional"))
      (node (ref "A05") (pin "E1") (pinfunction "P$2_E1") (pintype "bidirectional"))
      (node (ref "A06") (pin "E1") (pinfunction "P$2_E1") (pintype "bidirectional"))
      (node (ref "A07") (pin "E1") (pinfunction "P$2_E1") (pintype "bidirectional"))
      (node (ref "A08") (pin "E1") (pinfunction "P$2_E1") (pintype "bidirectional"))
      (node (ref "A09") (pin "E1") (pinfunction "P$2_E1") (pintype "bidirectional"))
      (node (ref "A10") (pin "E1") (pinfunction "P$2_E1") (pintype "bidirectional"))
      (node (ref "A11") (pin "E1") (pinfunction "P$2_E1") (pintype "bidirectional"))
      (node (ref "A12") (pin "E1") (pinfunction "P$2_E1") (pintype "bidirectional"))
      (node (ref "A13") (pin "E1") (pinfunction "P$2_E1") (pintype "bidirectional"))
      (node (ref "A14") (pin "E1") (pinfunction "P$2_E1") (pintype "bidirectional"))
      (node (ref "B15") (pin "P2") (pinfunction "OUT_P2") (pintype "output"))
    )
    (net (code "74") (name "D03MA2L") (class "Default")
      (node (ref "A01") (pin "H1") (pinfunction "P$2_H1") (pintype "bidirectional"))
      (node (ref "A02") (pin "H1") (pinfunction "P$2_H1") (pintype "bidirectional"))
      (node (ref "A03") (pin "H1") (pinfunction "P$2_H1") (pintype "bidirectional"))
      (node (ref "A04") (pin "H1") (pinfunction "P$2_H1") (pintype "bidirectional"))
      (node (ref "A05") (pin "H1") (pinfunction "P$2_H1") (pintype "bidirectional"))
      (node (ref "A06") (pin "H1") (pinfunction "P$2_H1") (pintype "bidirectional"))
      (node (ref "A07") (pin "H1") (pinfunction "P$2_H1") (pintype "bidirectional"))
      (node (ref "A08") (pin "H1") (pinfunction "P$2_H1") (pintype "bidirectional"))
      (node (ref "A09") (pin "H1") (pinfunction "P$2_H1") (pintype "bidirectional"))
      (node (ref "A10") (pin "H1") (pinfunction "P$2_H1") (pintype "bidirectional"))
      (node (ref "A11") (pin "H1") (pinfunction "P$2_H1") (pintype "bidirectional"))
      (node (ref "A12") (pin "H1") (pinfunction "P$2_H1") (pintype "bidirectional"))
      (node (ref "A13") (pin "H1") (pinfunction "P$2_H1") (pintype "bidirectional"))
      (node (ref "A14") (pin "H1") (pinfunction "P$2_H1") (pintype "bidirectional"))
      (node (ref "B15") (pin "V2") (pinfunction "OUT_V2") (pintype "output"))
    )
    (net (code "75") (name "D03MA3L") (class "Default")
      (node (ref "A01") (pin "J1") (pinfunction "P$2_J1") (pintype "bidirectional"))
      (node (ref "A02") (pin "J1") (pinfunction "P$2_J1") (pintype "bidirectional"))
      (node (ref "A03") (pin "J1") (pinfunction "P$2_J1") (pintype "bidirectional"))
      (node (ref "A04") (pin "J1") (pinfunction "P$2_J1") (pintype "bidirectional"))
      (node (ref "A05") (pin "J1") (pinfunction "P$2_J1") (pintype "bidirectional"))
      (node (ref "A06") (pin "J1") (pinfunction "P$2_J1") (pintype "bidirectional"))
      (node (ref "A07") (pin "J1") (pinfunction "P$2_J1") (pintype "bidirectional"))
      (node (ref "A08") (pin "J1") (pinfunction "P$2_J1") (pintype "bidirectional"))
      (node (ref "A09") (pin "J1") (pinfunction "P$2_J1") (pintype "bidirectional"))
      (node (ref "A10") (pin "J1") (pinfunction "P$2_J1") (pintype "bidirectional"))
      (node (ref "A11") (pin "J1") (pinfunction "P$2_J1") (pintype "bidirectional"))
      (node (ref "A12") (pin "J1") (pinfunction "P$2_J1") (pintype "bidirectional"))
      (node (ref "A13") (pin "J1") (pinfunction "P$2_J1") (pintype "bidirectional"))
      (node (ref "A14") (pin "J1") (pinfunction "P$2_J1") (pintype "bidirectional"))
      (node (ref "C15") (pin "E1") (pinfunction "OUT_E1") (pintype "output"))
    )
    (net (code "76") (name "D03MA4L") (class "Default")
      (node (ref "B01") (pin "D1") (pinfunction "P$2_D1") (pintype "bidirectional"))
      (node (ref "B02") (pin "D1") (pinfunction "P$2_D1") (pintype "bidirectional"))
      (node (ref "B03") (pin "D1") (pinfunction "P$2_D1") (pintype "bidirectional"))
      (node (ref "B04") (pin "D1") (pinfunction "P$2_D1") (pintype "bidirectional"))
      (node (ref "B05") (pin "D1") (pinfunction "P$2_D1") (pintype "bidirectional"))
      (node (ref "B06") (pin "D1") (pinfunction "P$2_D1") (pintype "bidirectional"))
      (node (ref "B07") (pin "D1") (pinfunction "P$2_D1") (pintype "bidirectional"))
      (node (ref "B08") (pin "D1") (pinfunction "P$2_D1") (pintype "bidirectional"))
      (node (ref "B09") (pin "D1") (pinfunction "P$2_D1") (pintype "bidirectional"))
      (node (ref "B10") (pin "D1") (pinfunction "P$2_D1") (pintype "bidirectional"))
      (node (ref "B11") (pin "D1") (pinfunction "P$2_D1") (pintype "bidirectional"))
      (node (ref "B12") (pin "D1") (pinfunction "P$2_D1") (pintype "bidirectional"))
      (node (ref "B13") (pin "D1") (pinfunction "P$2_D1") (pintype "bidirectional"))
      (node (ref "B14") (pin "D1") (pinfunction "P$2_D1") (pintype "bidirectional"))
      (node (ref "C15") (pin "L1") (pinfunction "OUT_L1") (pintype "output"))
    )
    (net (code "77") (name "D03MA5L") (class "Default")
      (node (ref "B01") (pin "E1") (pinfunction "P$2_E1") (pintype "bidirectional"))
      (node (ref "B02") (pin "E1") (pinfunction "P$2_E1") (pintype "bidirectional"))
      (node (ref "B03") (pin "E1") (pinfunction "P$2_E1") (pintype "bidirectional"))
      (node (ref "B04") (pin "E1") (pinfunction "P$2_E1") (pintype "bidirectional"))
      (node (ref "B05") (pin "E1") (pinfunction "P$2_E1") (pintype "bidirectional"))
      (node (ref "B06") (pin "E1") (pinfunction "P$2_E1") (pintype "bidirectional"))
      (node (ref "B07") (pin "E1") (pinfunction "P$2_E1") (pintype "bidirectional"))
      (node (ref "B08") (pin "E1") (pinfunction "P$2_E1") (pintype "bidirectional"))
      (node (ref "B09") (pin "E1") (pinfunction "P$2_E1") (pintype "bidirectional"))
      (node (ref "B10") (pin "E1") (pinfunction "P$2_E1") (pintype "bidirectional"))
      (node (ref "B11") (pin "E1") (pinfunction "P$2_E1") (pintype "bidirectional"))
      (node (ref "B12") (pin "E1") (pinfunction "P$2_E1") (pintype "bidirectional"))
      (node (ref "B13") (pin "E1") (pinfunction "P$2_E1") (pintype "bidirectional"))
      (node (ref "B14") (pin "E1") (pinfunction "P$2_E1") (pintype "bidirectional"))
      (node (ref "C15") (pin "S1") (pinfunction "OUT_S1") (pintype "output"))
    )
    (net (code "78") (name "D03MA6L") (class "Default")
      (node (ref "B01") (pin "H1") (pinfunction "P$2_H1") (pintype "bidirectional"))
      (node (ref "B02") (pin "H1") (pinfunction "P$2_H1") (pintype "bidirectional"))
      (node (ref "B03") (pin "H1") (pinfunction "P$2_H1") (pintype "bidirectional"))
      (node (ref "B04") (pin "H1") (pinfunction "P$2_H1") (pintype "bidirectional"))
      (node (ref "B05") (pin "H1") (pinfunction "P$2_H1") (pintype "bidirectional"))
      (node (ref "B06") (pin "H1") (pinfunction "P$2_H1") (pintype "bidirectional"))
      (node (ref "B07") (pin "H1") (pinfunction "P$2_H1") (pintype "bidirectional"))
      (node (ref "B08") (pin "H1") (pinfunction "P$2_H1") (pintype "bidirectional"))
      (node (ref "B09") (pin "H1") (pinfunction "P$2_H1") (pintype "bidirectional"))
      (node (ref "B10") (pin "H1") (pinfunction "P$2_H1") (pintype "bidirectional"))
      (node (ref "B11") (pin "H1") (pinfunction "P$2_H1") (pintype "bidirectional"))
      (node (ref "B12") (pin "H1") (pinfunction "P$2_H1") (pintype "bidirectional"))
      (node (ref "B13") (pin "H1") (pinfunction "P$2_H1") (pintype "bidirectional"))
      (node (ref "B14") (pin "H1") (pinfunction "P$2_H1") (pintype "bidirectional"))
      (node (ref "C15") (pin "J2") (pinfunction "OUT_J2") (pintype "output"))
    )
    (net (code "79") (name "D03MA7L") (class "Default")
      (node (ref "B01") (pin "J1") (pinfunction "P$2_J1") (pintype "bidirectional"))
      (node (ref "B02") (pin "J1") (pinfunction "P$2_J1") (pintype "bidirectional"))
      (node (ref "B03") (pin "J1") (pinfunction "P$2_J1") (pintype "bidirectional"))
      (node (ref "B04") (pin "J1") (pinfunction "P$2_J1") (pintype "bidirectional"))
      (node (ref "B05") (pin "J1") (pinfunction "P$2_J1") (pintype "bidirectional"))
      (node (ref "B06") (pin "J1") (pinfunction "P$2_J1") (pintype "bidirectional"))
      (node (ref "B07") (pin "J1") (pinfunction "P$2_J1") (pintype "bidirectional"))
      (node (ref "B08") (pin "J1") (pinfunction "P$2_J1") (pintype "bidirectional"))
      (node (ref "B09") (pin "J1") (pinfunction "P$2_J1") (pintype "bidirectional"))
      (node (ref "B10") (pin "J1") (pinfunction "P$2_J1") (pintype "bidirectional"))
      (node (ref "B11") (pin "J1") (pinfunction "P$2_J1") (pintype "bidirectional"))
      (node (ref "B12") (pin "J1") (pinfunction "P$2_J1") (pintype "bidirectional"))
      (node (ref "B13") (pin "J1") (pinfunction "P$2_J1") (pintype "bidirectional"))
      (node (ref "B14") (pin "J1") (pinfunction "P$2_J1") (pintype "bidirectional"))
      (node (ref "C15") (pin "P2") (pinfunction "OUT_P2") (pintype "output"))
    )
    (net (code "80") (name "D03MA8L") (class "Default")
      (node (ref "C15") (pin "V2") (pinfunction "OUT_V2") (pintype "output"))
      (node (ref "D01") (pin "D1") (pinfunction "P$2_D1") (pintype "bidirectional"))
      (node (ref "D02") (pin "D1") (pinfunction "P$2_D1") (pintype "bidirectional"))
      (node (ref "D03") (pin "D1") (pinfunction "P$2_D1") (pintype "bidirectional"))
      (node (ref "D04") (pin "D1") (pinfunction "P$2_D1") (pintype "bidirectional"))
      (node (ref "D05") (pin "D1") (pinfunction "P$2_D1") (pintype "bidirectional"))
      (node (ref "D06") (pin "D1") (pinfunction "P$2_D1") (pintype "bidirectional"))
      (node (ref "D07") (pin "D1") (pinfunction "P$2_D1") (pintype "bidirectional"))
      (node (ref "D08") (pin "D1") (pinfunction "P$2_D1") (pintype "bidirectional"))
      (node (ref "D09") (pin "D1") (pinfunction "P$2_D1") (pintype "bidirectional"))
      (node (ref "D10") (pin "D1") (pinfunction "P$2_D1") (pintype "bidirectional"))
      (node (ref "D11") (pin "D1") (pinfunction "P$2_D1") (pintype "bidirectional"))
      (node (ref "D12") (pin "D1") (pinfunction "P$2_D1") (pintype "bidirectional"))
      (node (ref "D13") (pin "D1") (pinfunction "P$2_D1") (pintype "bidirectional"))
      (node (ref "D14") (pin "D1") (pinfunction "P$2_D1") (pintype "bidirectional"))
    )
    (net (code "81") (name "D03MA9L") (class "Default")
      (node (ref "C16") (pin "E1") (pinfunction "OUT_E1") (pintype "output"))
      (node (ref "D01") (pin "E1") (pinfunction "P$2_E1") (pintype "bidirectional"))
      (node (ref "D02") (pin "E1") (pinfunction "P$2_E1") (pintype "bidirectional"))
      (node (ref "D03") (pin "E1") (pinfunction "P$2_E1") (pintype "bidirectional"))
      (node (ref "D04") (pin "E1") (pinfunction "P$2_E1") (pintype "bidirectional"))
      (node (ref "D05") (pin "E1") (pinfunction "P$2_E1") (pintype "bidirectional"))
      (node (ref "D06") (pin "E1") (pinfunction "P$2_E1") (pintype "bidirectional"))
      (node (ref "D07") (pin "E1") (pinfunction "P$2_E1") (pintype "bidirectional"))
      (node (ref "D08") (pin "E1") (pinfunction "P$2_E1") (pintype "bidirectional"))
      (node (ref "D09") (pin "E1") (pinfunction "P$2_E1") (pintype "bidirectional"))
      (node (ref "D10") (pin "E1") (pinfunction "P$2_E1") (pintype "bidirectional"))
      (node (ref "D11") (pin "E1") (pinfunction "P$2_E1") (pintype "bidirectional"))
      (node (ref "D12") (pin "E1") (pinfunction "P$2_E1") (pintype "bidirectional"))
      (node (ref "D13") (pin "E1") (pinfunction "P$2_E1") (pintype "bidirectional"))
      (node (ref "D14") (pin "E1") (pinfunction "P$2_E1") (pintype "bidirectional"))
    )
    (net (code "82") (name "D03MA10L") (class "Default")
      (node (ref "C16") (pin "L1") (pinfunction "OUT_L1") (pintype "output"))
      (node (ref "D01") (pin "H1") (pinfunction "P$2_H1") (pintype "bidirectional"))
      (node (ref "D02") (pin "H1") (pinfunction "P$2_H1") (pintype "bidirectional"))
      (node (ref "D03") (pin "H1") (pinfunction "P$2_H1") (pintype "bidirectional"))
      (node (ref "D04") (pin "H1") (pinfunction "P$2_H1") (pintype "bidirectional"))
      (node (ref "D05") (pin "H1") (pinfunction "P$2_H1") (pintype "bidirectional"))
      (node (ref "D06") (pin "H1") (pinfunction "P$2_H1") (pintype "bidirectional"))
      (node (ref "D07") (pin "H1") (pinfunction "P$2_H1") (pintype "bidirectional"))
      (node (ref "D08") (pin "H1") (pinfunction "P$2_H1") (pintype "bidirectional"))
      (node (ref "D09") (pin "H1") (pinfunction "P$2_H1") (pintype "bidirectional"))
      (node (ref "D10") (pin "H1") (pinfunction "P$2_H1") (pintype "bidirectional"))
      (node (ref "D11") (pin "H1") (pinfunction "P$2_H1") (pintype "bidirectional"))
      (node (ref "D12") (pin "H1") (pinfunction "P$2_H1") (pintype "bidirectional"))
      (node (ref "D13") (pin "H1") (pinfunction "P$2_H1") (pintype "bidirectional"))
      (node (ref "D14") (pin "H1") (pinfunction "P$2_H1") (pintype "bidirectional"))
    )
    (net (code "83") (name "D03MA11L") (class "Default")
      (node (ref "C16") (pin "S1") (pinfunction "OUT_S1") (pintype "output"))
      (node (ref "D01") (pin "J1") (pinfunction "P$2_J1") (pintype "bidirectional"))
      (node (ref "D02") (pin "J1") (pinfunction "P$2_J1") (pintype "bidirectional"))
      (node (ref "D03") (pin "J1") (pinfunction "P$2_J1") (pintype "bidirectional"))
      (node (ref "D04") (pin "J1") (pinfunction "P$2_J1") (pintype "bidirectional"))
      (node (ref "D05") (pin "J1") (pinfunction "P$2_J1") (pintype "bidirectional"))
      (node (ref "D06") (pin "J1") (pinfunction "P$2_J1") (pintype "bidirectional"))
      (node (ref "D07") (pin "J1") (pinfunction "P$2_J1") (pintype "bidirectional"))
      (node (ref "D08") (pin "J1") (pinfunction "P$2_J1") (pintype "bidirectional"))
      (node (ref "D09") (pin "J1") (pinfunction "P$2_J1") (pintype "bidirectional"))
      (node (ref "D10") (pin "J1") (pinfunction "P$2_J1") (pintype "bidirectional"))
      (node (ref "D11") (pin "J1") (pinfunction "P$2_J1") (pintype "bidirectional"))
      (node (ref "D12") (pin "J1") (pinfunction "P$2_J1") (pintype "bidirectional"))
      (node (ref "D13") (pin "J1") (pinfunction "P$2_J1") (pintype "bidirectional"))
      (node (ref "D14") (pin "J1") (pinfunction "P$2_J1") (pintype "bidirectional"))
    )
    (net (code "84") (name "D03MCBMB0L") (class "Default")
      (node (ref "A19N") (pin "S2") (pinfunction "P$2_S2") (pintype "bidirectional"))
      (node (ref "B19") (pin "A1") (pinfunction "A_A1") (pintype "input"))
    )
    (net (code "85") (name "D03MCBMB1L") (class "Default")
      (node (ref "A19N") (pin "T2") (pinfunction "P$2_T2") (pintype "bidirectional"))
      (node (ref "B19") (pin "B1") (pinfunction "B_B1") (pintype "input"))
    )
    (net (code "86") (name "D03MCBMB2L") (class "Default")
      (node (ref "A19N") (pin "V2") (pinfunction "P$2_V2") (pintype "bidirectional"))
      (node (ref "B19") (pin "F1") (pinfunction "A_F1") (pintype "input"))
    )
    (net (code "87") (name "D03MCBMB3L") (class "Default")
      (node (ref "A20N") (pin "D2") (pinfunction "P$2_D2") (pintype "bidirectional"))
      (node (ref "B19") (pin "H1") (pinfunction "B_H1") (pintype "input"))
    )
    (net (code "88") (name "D03MCBMB4L") (class "Default")
      (node (ref "A20N") (pin "E2") (pinfunction "P$2_E2") (pintype "bidirectional"))
      (node (ref "B19") (pin "M1") (pinfunction "A_M1") (pintype "input"))
    )
    (net (code "89") (name "D03MCBMB5L") (class "Default")
      (node (ref "A20N") (pin "H2") (pinfunction "P$2_H2") (pintype "bidirectional"))
      (node (ref "B19") (pin "N1") (pinfunction "B_N1") (pintype "input"))
    )
    (net (code "90") (name "D03MCBMB6L") (class "Default")
      (node (ref "A18N") (pin "K2") (pinfunction "P$2_K2") (pintype "bidirectional"))
      (node (ref "B19") (pin "D2") (pinfunction "A_D2") (pintype "input"))
    )
    (net (code "91") (name "D03MCBMB7L") (class "Default")
      (node (ref "A18N") (pin "M2") (pinfunction "P$2_M2") (pintype "bidirectional"))
      (node (ref "B19") (pin "E2") (pinfunction "B_E2") (pintype "input"))
    )
    (net (code "92") (name "D03MCBMB8L") (class "Default")
      (node (ref "A18N") (pin "P2") (pinfunction "P$2_P2") (pintype "bidirectional"))
      (node (ref "B19") (pin "K2") (pinfunction "A_K2") (pintype "input"))
    )
    (net (code "93") (name "D03MCBMB9L") (class "Default")
      (node (ref "A18N") (pin "S2") (pinfunction "P$2_S2") (pintype "bidirectional"))
      (node (ref "B19") (pin "L2") (pinfunction "B_L2") (pintype "input"))
    )
    (net (code "94") (name "D03MCBMB10L") (class "Default")
      (node (ref "A18N") (pin "T2") (pinfunction "P$2_T2") (pintype "bidirectional"))
      (node (ref "B19") (pin "R2") (pinfunction "A_R2") (pintype "input"))
    )
    (net (code "95") (name "D03MCBMB11L") (class "Default")
      (node (ref "A18N") (pin "V2") (pinfunction "P$2_V2") (pintype "bidirectional"))
      (node (ref "B19") (pin "S2") (pinfunction "B_S2") (pintype "input"))
    )
    (net (code "96") (name "D03MEMSTART") (class "Default")
      (node (ref "A16") (pin "M2") (pinfunction "P$2_M2") (pintype "bidirectional"))
      (node (ref "D17") (pin "B1") (pinfunction "C_B1") (pintype "input"))
      (node (ref "D17") (pin "L2") (pinfunction "C_L2") (pintype "input"))
      (node (ref "D17") (pin "N1") (pinfunction "C_N1") (pintype "input"))
      (node (ref "D17") (pin "S2") (pinfunction "C_S2") (pintype "input"))
      (node (ref "D18") (pin "F1") (pinfunction "IN_F1") (pintype "input"))
    )
    (net (code "97") (name "D04MD0L") (class "Default")
      (node (ref "A01") (pin "K1") (pinfunction "P$2_K1") (pintype "bidirectional"))
      (node (ref "A02") (pin "K1") (pinfunction "P$2_K1") (pintype "bidirectional"))
      (node (ref "A03") (pin "K1") (pinfunction "P$2_K1") (pintype "bidirectional"))
      (node (ref "A04") (pin "K1") (pinfunction "P$2_K1") (pintype "bidirectional"))
      (node (ref "A05") (pin "K1") (pinfunction "P$2_K1") (pintype "bidirectional"))
      (node (ref "A06") (pin "K1") (pinfunction "P$2_K1") (pintype "bidirectional"))
      (node (ref "A07") (pin "K1") (pinfunction "P$2_K1") (pintype "bidirectional"))
      (node (ref "A08") (pin "K1") (pinfunction "P$2_K1") (pintype "bidirectional"))
      (node (ref "A09") (pin "K1") (pinfunction "P$2_K1") (pintype "bidirectional"))
      (node (ref "A10") (pin "K1") (pinfunction "P$2_K1") (pintype "bidirectional"))
      (node (ref "A11") (pin "K1") (pinfunction "P$2_K1") (pintype "bidirectional"))
      (node (ref "A12") (pin "K1") (pinfunction "P$2_K1") (pintype "bidirectional"))
      (node (ref "A13") (pin "K1") (pinfunction "P$2_K1") (pintype "bidirectional"))
      (node (ref "A14") (pin "K1") (pinfunction "P$2_K1") (pintype "bidirectional"))
      (node (ref "B19") (pin "D1") (pinfunction "D_D1") (pintype "open_collector"))
      (node (ref "D15") (pin "C1") (pinfunction "D_C1") (pintype "input"))
    )
    (net (code "98") (name "D04MD1L") (class "Default")
      (node (ref "A01") (pin "L1") (pinfunction "P$2_L1") (pintype "bidirectional"))
      (node (ref "A02") (pin "L1") (pinfunction "P$2_L1") (pintype "bidirectional"))
      (node (ref "A03") (pin "L1") (pinfunction "P$2_L1") (pintype "bidirectional"))
      (node (ref "A04") (pin "L1") (pinfunction "P$2_L1") (pintype "bidirectional"))
      (node (ref "A05") (pin "L1") (pinfunction "P$2_L1") (pintype "bidirectional"))
      (node (ref "A06") (pin "L1") (pinfunction "P$2_L1") (pintype "bidirectional"))
      (node (ref "A07") (pin "L1") (pinfunction "P$2_L1") (pintype "bidirectional"))
      (node (ref "A08") (pin "L1") (pinfunction "P$2_L1") (pintype "bidirectional"))
      (node (ref "A09") (pin "L1") (pinfunction "P$2_L1") (pintype "bidirectional"))
      (node (ref "A10") (pin "L1") (pinfunction "P$2_L1") (pintype "bidirectional"))
      (node (ref "A11") (pin "L1") (pinfunction "P$2_L1") (pintype "bidirectional"))
      (node (ref "A12") (pin "L1") (pinfunction "P$2_L1") (pintype "bidirectional"))
      (node (ref "A13") (pin "L1") (pinfunction "P$2_L1") (pintype "bidirectional"))
      (node (ref "A14") (pin "L1") (pinfunction "P$2_L1") (pintype "bidirectional"))
      (node (ref "B19") (pin "E1") (pinfunction "E_E1") (pintype "open_collector"))
      (node (ref "D15") (pin "E2") (pinfunction "D_E2") (pintype "input"))
    )
    (net (code "99") (name "D04MD2L") (class "Default")
      (node (ref "A01") (pin "M1") (pinfunction "P$2_M1") (pintype "bidirectional"))
      (node (ref "A02") (pin "M1") (pinfunction "P$2_M1") (pintype "bidirectional"))
      (node (ref "A03") (pin "M1") (pinfunction "P$2_M1") (pintype "bidirectional"))
      (node (ref "A04") (pin "M1") (pinfunction "P$2_M1") (pintype "bidirectional"))
      (node (ref "A05") (pin "M1") (pinfunction "P$2_M1") (pintype "bidirectional"))
      (node (ref "A06") (pin "M1") (pinfunction "P$2_M1") (pintype "bidirectional"))
      (node (ref "A07") (pin "M1") (pinfunction "P$2_M1") (pintype "bidirectional"))
      (node (ref "A08") (pin "M1") (pinfunction "P$2_M1") (pintype "bidirectional"))
      (node (ref "A09") (pin "M1") (pinfunction "P$2_M1") (pintype "bidirectional"))
      (node (ref "A10") (pin "M1") (pinfunction "P$2_M1") (pintype "bidirectional"))
      (node (ref "A11") (pin "M1") (pinfunction "P$2_M1") (pintype "bidirectional"))
      (node (ref "A12") (pin "M1") (pinfunction "P$2_M1") (pintype "bidirectional"))
      (node (ref "A13") (pin "M1") (pinfunction "P$2_M1") (pintype "bidirectional"))
      (node (ref "A14") (pin "M1") (pinfunction "P$2_M1") (pintype "bidirectional"))
      (node (ref "B19") (pin "K1") (pinfunction "D_K1") (pintype "open_collector"))
      (node (ref "D15") (pin "J1") (pinfunction "D_J1") (pintype "input"))
    )
    (net (code "100") (name "D04MD3L") (class "Default")
      (node (ref "A01") (pin "P1") (pinfunction "P$2_P1") (pintype "bidirectional"))
      (node (ref "A02") (pin "P1") (pinfunction "P$2_P1") (pintype "bidirectional"))
      (node (ref "A03") (pin "P1") (pinfunction "P$2_P1") (pintype "bidirectional"))
      (node (ref "A04") (pin "P1") (pinfunction "P$2_P1") (pintype "bidirectional"))
      (node (ref "A05") (pin "P1") (pinfunction "P$2_P1") (pintype "bidirectional"))
      (node (ref "A06") (pin "P1") (pinfunction "P$2_P1") (pintype "bidirectional"))
      (node (ref "A07") (pin "P1") (pinfunction "P$2_P1") (pintype "bidirectional"))
      (node (ref "A08") (pin "P1") (pinfunction "P$2_P1") (pintype "bidirectional"))
      (node (ref "A09") (pin "P1") (pinfunction "P$2_P1") (pintype "bidirectional"))
      (node (ref "A10") (pin "P1") (pinfunction "P$2_P1") (pintype "bidirectional"))
      (node (ref "A11") (pin "P1") (pinfunction "P$2_P1") (pintype "bidirectional"))
      (node (ref "A12") (pin "P1") (pinfunction "P$2_P1") (pintype "bidirectional"))
      (node (ref "A13") (pin "P1") (pinfunction "P$2_P1") (pintype "bidirectional"))
      (node (ref "A14") (pin "P1") (pinfunction "P$2_P1") (pintype "bidirectional"))
      (node (ref "B19") (pin "L1") (pinfunction "E_L1") (pintype "open_collector"))
      (node (ref "D15") (pin "M2") (pinfunction "D_M2") (pintype "input"))
    )
    (net (code "101") (name "D04MD4L") (class "Default")
      (node (ref "B01") (pin "K1") (pinfunction "P$2_K1") (pintype "bidirectional"))
      (node (ref "B02") (pin "K1") (pinfunction "P$2_K1") (pintype "bidirectional"))
      (node (ref "B03") (pin "K1") (pinfunction "P$2_K1") (pintype "bidirectional"))
      (node (ref "B04") (pin "K1") (pinfunction "P$2_K1") (pintype "bidirectional"))
      (node (ref "B05") (pin "K1") (pinfunction "P$2_K1") (pintype "bidirectional"))
      (node (ref "B06") (pin "K1") (pinfunction "P$2_K1") (pintype "bidirectional"))
      (node (ref "B07") (pin "K1") (pinfunction "P$2_K1") (pintype "bidirectional"))
      (node (ref "B08") (pin "K1") (pinfunction "P$2_K1") (pintype "bidirectional"))
      (node (ref "B09") (pin "K1") (pinfunction "P$2_K1") (pintype "bidirectional"))
      (node (ref "B10") (pin "K1") (pinfunction "P$2_K1") (pintype "bidirectional"))
      (node (ref "B11") (pin "K1") (pinfunction "P$2_K1") (pintype "bidirectional"))
      (node (ref "B12") (pin "K1") (pinfunction "P$2_K1") (pintype "bidirectional"))
      (node (ref "B13") (pin "K1") (pinfunction "P$2_K1") (pintype "bidirectional"))
      (node (ref "B14") (pin "K1") (pinfunction "P$2_K1") (pintype "bidirectional"))
      (node (ref "B19") (pin "R1") (pinfunction "D_R1") (pintype "open_collector"))
      (node (ref "D15") (pin "P1") (pinfunction "D_P1") (pintype "input"))
    )
    (net (code "102") (name "D04MD5L") (class "Default")
      (node (ref "B01") (pin "L1") (pinfunction "P$2_L1") (pintype "bidirectional"))
      (node (ref "B02") (pin "L1") (pinfunction "P$2_L1") (pintype "bidirectional"))
      (node (ref "B03") (pin "L1") (pinfunction "P$2_L1") (pintype "bidirectional"))
      (node (ref "B04") (pin "L1") (pinfunction "P$2_L1") (pintype "bidirectional"))
      (node (ref "B05") (pin "L1") (pinfunction "P$2_L1") (pintype "bidirectional"))
      (node (ref "B06") (pin "L1") (pinfunction "P$2_L1") (pintype "bidirectional"))
      (node (ref "B07") (pin "L1") (pinfunction "P$2_L1") (pintype "bidirectional"))
      (node (ref "B08") (pin "L1") (pinfunction "P$2_L1") (pintype "bidirectional"))
      (node (ref "B09") (pin "L1") (pinfunction "P$2_L1") (pintype "bidirectional"))
      (node (ref "B10") (pin "L1") (pinfunction "P$2_L1") (pintype "bidirectional"))
      (node (ref "B11") (pin "L1") (pinfunction "P$2_L1") (pintype "bidirectional"))
      (node (ref "B12") (pin "L1") (pinfunction "P$2_L1") (pintype "bidirectional"))
      (node (ref "B13") (pin "L1") (pinfunction "P$2_L1") (pintype "bidirectional"))
      (node (ref "B14") (pin "L1") (pinfunction "P$2_L1") (pintype "bidirectional"))
      (node (ref "B19") (pin "S1") (pinfunction "E_S1") (pintype "open_collector"))
      (node (ref "D15") (pin "T2") (pinfunction "D_T2") (pintype "input"))
    )
    (net (code "103") (name "D04MD6L") (class "Default")
      (node (ref "B01") (pin "M1") (pinfunction "P$2_M1") (pintype "bidirectional"))
      (node (ref "B02") (pin "M1") (pinfunction "P$2_M1") (pintype "bidirectional"))
      (node (ref "B03") (pin "M1") (pinfunction "P$2_M1") (pintype "bidirectional"))
      (node (ref "B04") (pin "M1") (pinfunction "P$2_M1") (pintype "bidirectional"))
      (node (ref "B05") (pin "M1") (pinfunction "P$2_M1") (pintype "bidirectional"))
      (node (ref "B06") (pin "M1") (pinfunction "P$2_M1") (pintype "bidirectional"))
      (node (ref "B07") (pin "M1") (pinfunction "P$2_M1") (pintype "bidirectional"))
      (node (ref "B08") (pin "M1") (pinfunction "P$2_M1") (pintype "bidirectional"))
      (node (ref "B09") (pin "M1") (pinfunction "P$2_M1") (pintype "bidirectional"))
      (node (ref "B10") (pin "M1") (pinfunction "P$2_M1") (pintype "bidirectional"))
      (node (ref "B11") (pin "M1") (pinfunction "P$2_M1") (pintype "bidirectional"))
      (node (ref "B12") (pin "M1") (pinfunction "P$2_M1") (pintype "bidirectional"))
      (node (ref "B13") (pin "M1") (pinfunction "P$2_M1") (pintype "bidirectional"))
      (node (ref "B14") (pin "M1") (pinfunction "P$2_M1") (pintype "bidirectional"))
      (node (ref "B19") (pin "H2") (pinfunction "D_H2") (pintype "open_collector"))
      (node (ref "D16") (pin "C1") (pinfunction "D_C1") (pintype "input"))
    )
    (net (code "104") (name "D04MD7L") (class "Default")
      (node (ref "B01") (pin "P1") (pinfunction "P$2_P1") (pintype "bidirectional"))
      (node (ref "B02") (pin "P1") (pinfunction "P$2_P1") (pintype "bidirectional"))
      (node (ref "B03") (pin "P1") (pinfunction "P$2_P1") (pintype "bidirectional"))
      (node (ref "B04") (pin "P1") (pinfunction "P$2_P1") (pintype "bidirectional"))
      (node (ref "B05") (pin "P1") (pinfunction "P$2_P1") (pintype "bidirectional"))
      (node (ref "B06") (pin "P1") (pinfunction "P$2_P1") (pintype "bidirectional"))
      (node (ref "B07") (pin "P1") (pinfunction "P$2_P1") (pintype "bidirectional"))
      (node (ref "B08") (pin "P1") (pinfunction "P$2_P1") (pintype "bidirectional"))
      (node (ref "B09") (pin "P1") (pinfunction "P$2_P1") (pintype "bidirectional"))
      (node (ref "B10") (pin "P1") (pinfunction "P$2_P1") (pintype "bidirectional"))
      (node (ref "B11") (pin "P1") (pinfunction "P$2_P1") (pintype "bidirectional"))
      (node (ref "B12") (pin "P1") (pinfunction "P$2_P1") (pintype "bidirectional"))
      (node (ref "B13") (pin "P1") (pinfunction "P$2_P1") (pintype "bidirectional"))
      (node (ref "B14") (pin "P1") (pinfunction "P$2_P1") (pintype "bidirectional"))
      (node (ref "B19") (pin "J2") (pinfunction "E_J2") (pintype "open_collector"))
      (node (ref "D16") (pin "E2") (pinfunction "D_E2") (pintype "input"))
    )
    (net (code "105") (name "D04MD8L") (class "Default")
      (node (ref "B19") (pin "N2") (pinfunction "D_N2") (pintype "open_collector"))
      (node (ref "D01") (pin "K1") (pinfunction "P$2_K1") (pintype "bidirectional"))
      (node (ref "D02") (pin "K1") (pinfunction "P$2_K1") (pintype "bidirectional"))
      (node (ref "D03") (pin "K1") (pinfunction "P$2_K1") (pintype "bidirectional"))
      (node (ref "D04") (pin "K1") (pinfunction "P$2_K1") (pintype "bidirectional"))
      (node (ref "D05") (pin "K1") (pinfunction "P$2_K1") (pintype "bidirectional"))
      (node (ref "D06") (pin "K1") (pinfunction "P$2_K1") (pintype "bidirectional"))
      (node (ref "D07") (pin "K1") (pinfunction "P$2_K1") (pintype "bidirectional"))
      (node (ref "D08") (pin "K1") (pinfunction "P$2_K1") (pintype "bidirectional"))
      (node (ref "D09") (pin "K1") (pinfunction "P$2_K1") (pintype "bidirectional"))
      (node (ref "D10") (pin "K1") (pinfunction "P$2_K1") (pintype "bidirectional"))
      (node (ref "D11") (pin "K1") (pinfunction "P$2_K1") (pintype "bidirectional"))
      (node (ref "D12") (pin "K1") (pinfunction "P$2_K1") (pintype "bidirectional"))
      (node (ref "D13") (pin "K1") (pinfunction "P$2_K1") (pintype "bidirectional"))
      (node (ref "D14") (pin "K1") (pinfunction "P$2_K1") (pintype "bidirectional"))
      (node (ref "D16") (pin "J1") (pinfunction "D_J1") (pintype "input"))
    )
    (net (code "106") (name "D04MD9L") (class "Default")
      (node (ref "B19") (pin "P2") (pinfunction "E_P2") (pintype "open_collector"))
      (node (ref "D01") (pin "L1") (pinfunction "P$2_L1") (pintype "bidirectional"))
      (node (ref "D02") (pin "L1") (pinfunction "P$2_L1") (pintype "bidirectional"))
      (node (ref "D03") (pin "L1") (pinfunction "P$2_L1") (pintype "bidirectional"))
      (node (ref "D04") (pin "L1") (pinfunction "P$2_L1") (pintype "bidirectional"))
      (node (ref "D05") (pin "L1") (pinfunction "P$2_L1") (pintype "bidirectional"))
      (node (ref "D06") (pin "L1") (pinfunction "P$2_L1") (pintype "bidirectional"))
      (node (ref "D07") (pin "L1") (pinfunction "P$2_L1") (pintype "bidirectional"))
      (node (ref "D08") (pin "L1") (pinfunction "P$2_L1") (pintype "bidirectional"))
      (node (ref "D09") (pin "L1") (pinfunction "P$2_L1") (pintype "bidirectional"))
      (node (ref "D10") (pin "L1") (pinfunction "P$2_L1") (pintype "bidirectional"))
      (node (ref "D11") (pin "L1") (pinfunction "P$2_L1") (pintype "bidirectional"))
      (node (ref "D12") (pin "L1") (pinfunction "P$2_L1") (pintype "bidirectional"))
      (node (ref "D13") (pin "L1") (pinfunction "P$2_L1") (pintype "bidirectional"))
      (node (ref "D14") (pin "L1") (pinfunction "P$2_L1") (pintype "bidirectional"))
      (node (ref "D16") (pin "M2") (pinfunction "D_M2") (pintype "input"))
    )
    (net (code "107") (name "D04MD10L") (class "Default")
      (node (ref "B19") (pin "U2") (pinfunction "D_U2") (pintype "open_collector"))
      (node (ref "D01") (pin "M1") (pinfunction "P$2_M1") (pintype "bidirectional"))
      (node (ref "D02") (pin "M1") (pinfunction "P$2_M1") (pintype "bidirectional"))
      (node (ref "D03") (pin "M1") (pinfunction "P$2_M1") (pintype "bidirectional"))
      (node (ref "D04") (pin "M1") (pinfunction "P$2_M1") (pintype "bidirectional"))
      (node (ref "D05") (pin "M1") (pinfunction "P$2_M1") (pintype "bidirectional"))
      (node (ref "D06") (pin "M1") (pinfunction "P$2_M1") (pintype "bidirectional"))
      (node (ref "D07") (pin "M1") (pinfunction "P$2_M1") (pintype "bidirectional"))
      (node (ref "D08") (pin "M1") (pinfunction "P$2_M1") (pintype "bidirectional"))
      (node (ref "D09") (pin "M1") (pinfunction "P$2_M1") (pintype "bidirectional"))
      (node (ref "D10") (pin "M1") (pinfunction "P$2_M1") (pintype "bidirectional"))
      (node (ref "D11") (pin "M1") (pinfunction "P$2_M1") (pintype "bidirectional"))
      (node (ref "D12") (pin "M1") (pinfunction "P$2_M1") (pintype "bidirectional"))
      (node (ref "D13") (pin "M1") (pinfunction "P$2_M1") (pintype "bidirectional"))
      (node (ref "D14") (pin "M1") (pinfunction "P$2_M1") (pintype "bidirectional"))
      (node (ref "D16") (pin "P1") (pinfunction "D_P1") (pintype "input"))
    )
    (net (code "108") (name "D04MD11L") (class "Default")
      (node (ref "B19") (pin "V2") (pinfunction "E_V2") (pintype "open_collector"))
      (node (ref "D01") (pin "P1") (pinfunction "P$2_P1") (pintype "bidirectional"))
      (node (ref "D02") (pin "P1") (pinfunction "P$2_P1") (pintype "bidirectional"))
      (node (ref "D03") (pin "P1") (pinfunction "P$2_P1") (pintype "bidirectional"))
      (node (ref "D04") (pin "P1") (pinfunction "P$2_P1") (pintype "bidirectional"))
      (node (ref "D05") (pin "P1") (pinfunction "P$2_P1") (pintype "bidirectional"))
      (node (ref "D06") (pin "P1") (pinfunction "P$2_P1") (pintype "bidirectional"))
      (node (ref "D07") (pin "P1") (pinfunction "P$2_P1") (pintype "bidirectional"))
      (node (ref "D08") (pin "P1") (pinfunction "P$2_P1") (pintype "bidirectional"))
      (node (ref "D09") (pin "P1") (pinfunction "P$2_P1") (pintype "bidirectional"))
      (node (ref "D10") (pin "P1") (pinfunction "P$2_P1") (pintype "bidirectional"))
      (node (ref "D11") (pin "P1") (pinfunction "P$2_P1") (pintype "bidirectional"))
      (node (ref "D12") (pin "P1") (pinfunction "P$2_P1") (pintype "bidirectional"))
      (node (ref "D13") (pin "P1") (pinfunction "P$2_P1") (pintype "bidirectional"))
      (node (ref "D14") (pin "P1") (pinfunction "P$2_P1") (pintype "bidirectional"))
      (node (ref "D16") (pin "T2") (pinfunction "D_T2") (pintype "input"))
    )
    (net (code "109") (name "GND") (class "Default")
      (node (ref "A01") (pin "C1") (pinfunction "P$2_C1") (pintype "bidirectional"))
      (node (ref "A01") (pin "C2") (pinfunction "P$2_C2") (pintype "bidirectional"))
      (node (ref "A01") (pin "F1") (pinfunction "P$2_F1") (pintype "bidirectional"))
      (node (ref "A01") (pin "F2") (pinfunction "P$2_F2") (pintype "bidirectional"))
      (node (ref "A01") (pin "N1") (pinfunction "P$2_N1") (pintype "bidirectional"))
      (node (ref "A01") (pin "N2") (pinfunction "P$2_N2") (pintype "bidirectional"))
      (node (ref "A01") (pin "T1") (pinfunction "P$2_T1") (pintype "bidirectional"))
      (node (ref "A01") (pin "T2") (pinfunction "P$2_T2") (pintype "bidirectional"))
      (node (ref "A02") (pin "C1") (pinfunction "P$2_C1") (pintype "bidirectional"))
      (node (ref "A02") (pin "C2") (pinfunction "P$2_C2") (pintype "bidirectional"))
      (node (ref "A02") (pin "F1") (pinfunction "P$2_F1") (pintype "bidirectional"))
      (node (ref "A02") (pin "F2") (pinfunction "P$2_F2") (pintype "bidirectional"))
      (node (ref "A02") (pin "N1") (pinfunction "P$2_N1") (pintype "bidirectional"))
      (node (ref "A02") (pin "N2") (pinfunction "P$2_N2") (pintype "bidirectional"))
      (node (ref "A02") (pin "T1") (pinfunction "P$2_T1") (pintype "bidirectional"))
      (node (ref "A02") (pin "T2") (pinfunction "P$2_T2") (pintype "bidirectional"))
      (node (ref "A03") (pin "C1") (pinfunction "P$2_C1") (pintype "bidirectional"))
      (node (ref "A03") (pin "C2") (pinfunction "P$2_C2") (pintype "bidirectional"))
      (node (ref "A03") (pin "F1") (pinfunction "P$2_F1") (pintype "bidirectional"))
      (node (ref "A03") (pin "F2") (pinfunction "P$2_F2") (pintype "bidirectional"))
      (node (ref "A03") (pin "N1") (pinfunction "P$2_N1") (pintype "bidirectional"))
      (node (ref "A03") (pin "N2") (pinfunction "P$2_N2") (pintype "bidirectional"))
      (node (ref "A03") (pin "T1") (pinfunction "P$2_T1") (pintype "bidirectional"))
      (node (ref "A03") (pin "T2") (pinfunction "P$2_T2") (pintype "bidirectional"))
      (node (ref "A04") (pin "C1") (pinfunction "P$2_C1") (pintype "bidirectional"))
      (node (ref "A04") (pin "C2") (pinfunction "P$2_C2") (pintype "bidirectional"))
      (node (ref "A04") (pin "F1") (pinfunction "P$2_F1") (pintype "bidirectional"))
      (node (ref "A04") (pin "F2") (pinfunction "P$2_F2") (pintype "bidirectional"))
      (node (ref "A04") (pin "N1") (pinfunction "P$2_N1") (pintype "bidirectional"))
      (node (ref "A04") (pin "N2") (pinfunction "P$2_N2") (pintype "bidirectional"))
      (node (ref "A04") (pin "T1") (pinfunction "P$2_T1") (pintype "bidirectional"))
      (node (ref "A04") (pin "T2") (pinfunction "P$2_T2") (pintype "bidirectional"))
      (node (ref "A05") (pin "C1") (pinfunction "P$2_C1") (pintype "bidirectional"))
      (node (ref "A05") (pin "C2") (pinfunction "P$2_C2") (pintype "bidirectional"))
      (node (ref "A05") (pin "F1") (pinfunction "P$2_F1") (pintype "bidirectional"))
      (node (ref "A05") (pin "F2") (pinfunction "P$2_F2") (pintype "bidirectional"))
      (node (ref "A05") (pin "N1") (pinfunction "P$2_N1") (pintype "bidirectional"))
      (node (ref "A05") (pin "N2") (pinfunction "P$2_N2") (pintype "bidirectional"))
      (node (ref "A05") (pin "T1") (pinfunction "P$2_T1") (pintype "bidirectional"))
      (node (ref "A05") (pin "T2") (pinfunction "P$2_T2") (pintype "bidirectional"))
      (node (ref "A06") (pin "C1") (pinfunction "P$2_C1") (pintype "bidirectional"))
      (node (ref "A06") (pin "C2") (pinfunction "P$2_C2") (pintype "bidirectional"))
      (node (ref "A06") (pin "F1") (pinfunction "P$2_F1") (pintype "bidirectional"))
      (node (ref "A06") (pin "F2") (pinfunction "P$2_F2") (pintype "bidirectional"))
      (node (ref "A06") (pin "N1") (pinfunction "P$2_N1") (pintype "bidirectional"))
      (node (ref "A06") (pin "N2") (pinfunction "P$2_N2") (pintype "bidirectional"))
      (node (ref "A06") (pin "T1") (pinfunction "P$2_T1") (pintype "bidirectional"))
      (node (ref "A06") (pin "T2") (pinfunction "P$2_T2") (pintype "bidirectional"))
      (node (ref "A07") (pin "C1") (pinfunction "P$2_C1") (pintype "bidirectional"))
      (node (ref "A07") (pin "C2") (pinfunction "P$2_C2") (pintype "bidirectional"))
      (node (ref "A07") (pin "F1") (pinfunction "P$2_F1") (pintype "bidirectional"))
      (node (ref "A07") (pin "F2") (pinfunction "P$2_F2") (pintype "bidirectional"))
      (node (ref "A07") (pin "N1") (pinfunction "P$2_N1") (pintype "bidirectional"))
      (node (ref "A07") (pin "N2") (pinfunction "P$2_N2") (pintype "bidirectional"))
      (node (ref "A07") (pin "T1") (pinfunction "P$2_T1") (pintype "bidirectional"))
      (node (ref "A07") (pin "T2") (pinfunction "P$2_T2") (pintype "bidirectional"))
      (node (ref "A08") (pin "C1") (pinfunction "P$2_C1") (pintype "bidirectional"))
      (node (ref "A08") (pin "C2") (pinfunction "P$2_C2") (pintype "bidirectional"))
      (node (ref "A08") (pin "F1") (pinfunction "P$2_F1") (pintype "bidirectional"))
      (node (ref "A08") (pin "F2") (pinfunction "P$2_F2") (pintype "bidirectional"))
      (node (ref "A08") (pin "N1") (pinfunction "P$2_N1") (pintype "bidirectional"))
      (node (ref "A08") (pin "N2") (pinfunction "P$2_N2") (pintype "bidirectional"))
      (node (ref "A08") (pin "T1") (pinfunction "P$2_T1") (pintype "bidirectional"))
      (node (ref "A08") (pin "T2") (pinfunction "P$2_T2") (pintype "bidirectional"))
      (node (ref "A09") (pin "C1") (pinfunction "P$2_C1") (pintype "bidirectional"))
      (node (ref "A09") (pin "C2") (pinfunction "P$2_C2") (pintype "bidirectional"))
      (node (ref "A09") (pin "F1") (pinfunction "P$2_F1") (pintype "bidirectional"))
      (node (ref "A09") (pin "F2") (pinfunction "P$2_F2") (pintype "bidirectional"))
      (node (ref "A09") (pin "N1") (pinfunction "P$2_N1") (pintype "bidirectional"))
      (node (ref "A09") (pin "N2") (pinfunction "P$2_N2") (pintype "bidirectional"))
      (node (ref "A09") (pin "T1") (pinfunction "P$2_T1") (pintype "bidirectional"))
      (node (ref "A09") (pin "T2") (pinfunction "P$2_T2") (pintype "bidirectional"))
      (node (ref "A10") (pin "C1") (pinfunction "P$2_C1") (pintype "bidirectional"))
      (node (ref "A10") (pin "C2") (pinfunction "P$2_C2") (pintype "bidirectional"))
      (node (ref "A10") (pin "F1") (pinfunction "P$2_F1") (pintype "bidirectional"))
      (node (ref "A10") (pin "F2") (pinfunction "P$2_F2") (pintype "bidirectional"))
      (node (ref "A10") (pin "N1") (pinfunction "P$2_N1") (pintype "bidirectional"))
      (node (ref "A10") (pin "N2") (pinfunction "P$2_N2") (pintype "bidirectional"))
      (node (ref "A10") (pin "T1") (pinfunction "P$2_T1") (pintype "bidirectional"))
      (node (ref "A10") (pin "T2") (pinfunction "P$2_T2") (pintype "bidirectional"))
      (node (ref "A11") (pin "C1") (pinfunction "P$2_C1") (pintype "bidirectional"))
      (node (ref "A11") (pin "C2") (pinfunction "P$2_C2") (pintype "bidirectional"))
      (node (ref "A11") (pin "F1") (pinfunction "P$2_F1") (pintype "bidirectional"))
      (node (ref "A11") (pin "F2") (pinfunction "P$2_F2") (pintype "bidirectional"))
      (node (ref "A11") (pin "N1") (pinfunction "P$2_N1") (pintype "bidirectional"))
      (node (ref "A11") (pin "N2") (pinfunction "P$2_N2") (pintype "bidirectional"))
      (node (ref "A11") (pin "T1") (pinfunction "P$2_T1") (pintype "bidirectional"))
      (node (ref "A11") (pin "T2") (pinfunction "P$2_T2") (pintype "bidirectional"))
      (node (ref "A12") (pin "C1") (pinfunction "P$2_C1") (pintype "bidirectional"))
      (node (ref "A12") (pin "C2") (pinfunction "P$2_C2") (pintype "bidirectional"))
      (node (ref "A12") (pin "F1") (pinfunction "P$2_F1") (pintype "bidirectional"))
      (node (ref "A12") (pin "F2") (pinfunction "P$2_F2") (pintype "bidirectional"))
      (node (ref "A12") (pin "N1") (pinfunction "P$2_N1") (pintype "bidirectional"))
      (node (ref "A12") (pin "N2") (pinfunction "P$2_N2") (pintype "bidirectional"))
      (node (ref "A12") (pin "T1") (pinfunction "P$2_T1") (pintype "bidirectional"))
      (node (ref "A12") (pin "T2") (pinfunction "P$2_T2") (pintype "bidirectional"))
      (node (ref "A13") (pin "C1") (pinfunction "P$2_C1") (pintype "bidirectional"))
      (node (ref "A13") (pin "C2") (pinfunction "P$2_C2") (pintype "bidirectional"))
      (node (ref "A13") (pin "F1") (pinfunction "P$2_F1") (pintype "bidirectional"))
      (node (ref "A13") (pin "F2") (pinfunction "P$2_F2") (pintype "bidirectional"))
      (node (ref "A13") (pin "N1") (pinfunction "P$2_N1") (pintype "bidirectional"))
      (node (ref "A13") (pin "N2") (pinfunction "P$2_N2") (pintype "bidirectional"))
      (node (ref "A13") (pin "T1") (pinfunction "P$2_T1") (pintype "bidirectional"))
      (node (ref "A13") (pin "T2") (pinfunction "P$2_T2") (pintype "bidirectional"))
      (node (ref "A14") (pin "C1") (pinfunction "P$2_C1") (pintype "bidirectional"))
      (node (ref "A14") (pin "C2") (pinfunction "P$2_C2") (pintype "bidirectional"))
      (node (ref "A14") (pin "F1") (pinfunction "P$2_F1") (pintype "bidirectional"))
      (node (ref "A14") (pin "F2") (pinfunction "P$2_F2") (pintype "bidirectional"))
      (node (ref "A14") (pin "N1") (pinfunction "P$2_N1") (pintype "bidirectional"))
      (node (ref "A14") (pin "N2") (pinfunction "P$2_N2") (pintype "bidirectional"))
      (node (ref "A14") (pin "T1") (pinfunction "P$2_T1") (pintype "bidirectional"))
      (node (ref "A14") (pin "T2") (pinfunction "P$2_T2") (pintype "bidirectional"))
      (node (ref "B01") (pin "C1") (pinfunction "P$2_C1") (pintype "bidirectional"))
      (node (ref "B01") (pin "C2") (pinfunction "P$2_C2") (pintype "bidirectional"))
      (node (ref "B01") (pin "F1") (pinfunction "P$2_F1") (pintype "bidirectional"))
      (node (ref "B01") (pin "F2") (pinfunction "P$2_F2") (pintype "bidirectional"))
      (node (ref "B01") (pin "N1") (pinfunction "P$2_N1") (pintype "bidirectional"))
      (node (ref "B01") (pin "N2") (pinfunction "P$2_N2") (pintype "bidirectional"))
      (node (ref "B01") (pin "T1") (pinfunction "P$2_T1") (pintype "bidirectional"))
      (node (ref "B01") (pin "T2") (pinfunction "P$2_T2") (pintype "bidirectional"))
      (node (ref "B02") (pin "C1") (pinfunction "P$2_C1") (pintype "bidirectional"))
      (node (ref "B02") (pin "C2") (pinfunction "P$2_C2") (pintype "bidirectional"))
      (node (ref "B02") (pin "F1") (pinfunction "P$2_F1") (pintype "bidirectional"))
      (node (ref "B02") (pin "F2") (pinfunction "P$2_F2") (pintype "bidirectional"))
      (node (ref "B02") (pin "N1") (pinfunction "P$2_N1") (pintype "bidirectional"))
      (node (ref "B02") (pin "N2") (pinfunction "P$2_N2") (pintype "bidirectional"))
      (node (ref "B02") (pin "T1") (pinfunction "P$2_T1") (pintype "bidirectional"))
      (node (ref "B02") (pin "T2") (pinfunction "P$2_T2") (pintype "bidirectional"))
      (node (ref "B03") (pin "C1") (pinfunction "P$2_C1") (pintype "bidirectional"))
      (node (ref "B03") (pin "C2") (pinfunction "P$2_C2") (pintype "bidirectional"))
      (node (ref "B03") (pin "F1") (pinfunction "P$2_F1") (pintype "bidirectional"))
      (node (ref "B03") (pin "F2") (pinfunction "P$2_F2") (pintype "bidirectional"))
      (node (ref "B03") (pin "N1") (pinfunction "P$2_N1") (pintype "bidirectional"))
      (node (ref "B03") (pin "N2") (pinfunction "P$2_N2") (pintype "bidirectional"))
      (node (ref "B03") (pin "T1") (pinfunction "P$2_T1") (pintype "bidirectional"))
      (node (ref "B03") (pin "T2") (pinfunction "P$2_T2") (pintype "bidirectional"))
      (node (ref "B04") (pin "C1") (pinfunction "P$2_C1") (pintype "bidirectional"))
      (node (ref "B04") (pin "C2") (pinfunction "P$2_C2") (pintype "bidirectional"))
      (node (ref "B04") (pin "F1") (pinfunction "P$2_F1") (pintype "bidirectional"))
      (node (ref "B04") (pin "F2") (pinfunction "P$2_F2") (pintype "bidirectional"))
      (node (ref "B04") (pin "N1") (pinfunction "P$2_N1") (pintype "bidirectional"))
      (node (ref "B04") (pin "N2") (pinfunction "P$2_N2") (pintype "bidirectional"))
      (node (ref "B04") (pin "T1") (pinfunction "P$2_T1") (pintype "bidirectional"))
      (node (ref "B04") (pin "T2") (pinfunction "P$2_T2") (pintype "bidirectional"))
      (node (ref "B05") (pin "C1") (pinfunction "P$2_C1") (pintype "bidirectional"))
      (node (ref "B05") (pin "C2") (pinfunction "P$2_C2") (pintype "bidirectional"))
      (node (ref "B05") (pin "F1") (pinfunction "P$2_F1") (pintype "bidirectional"))
      (node (ref "B05") (pin "F2") (pinfunction "P$2_F2") (pintype "bidirectional"))
      (node (ref "B05") (pin "N1") (pinfunction "P$2_N1") (pintype "bidirectional"))
      (node (ref "B05") (pin "N2") (pinfunction "P$2_N2") (pintype "bidirectional"))
      (node (ref "B05") (pin "T1") (pinfunction "P$2_T1") (pintype "bidirectional"))
      (node (ref "B05") (pin "T2") (pinfunction "P$2_T2") (pintype "bidirectional"))
      (node (ref "B06") (pin "C1") (pinfunction "P$2_C1") (pintype "bidirectional"))
      (node (ref "B06") (pin "C2") (pinfunction "P$2_C2") (pintype "bidirectional"))
      (node (ref "B06") (pin "F1") (pinfunction "P$2_F1") (pintype "bidirectional"))
      (node (ref "B06") (pin "F2") (pinfunction "P$2_F2") (pintype "bidirectional"))
      (node (ref "B06") (pin "N1") (pinfunction "P$2_N1") (pintype "bidirectional"))
      (node (ref "B06") (pin "N2") (pinfunction "P$2_N2") (pintype "bidirectional"))
      (node (ref "B06") (pin "T1") (pinfunction "P$2_T1") (pintype "bidirectional"))
      (node (ref "B06") (pin "T2") (pinfunction "P$2_T2") (pintype "bidirectional"))
      (node (ref "B07") (pin "C1") (pinfunction "P$2_C1") (pintype "bidirectional"))
      (node (ref "B07") (pin "C2") (pinfunction "P$2_C2") (pintype "bidirectional"))
      (node (ref "B07") (pin "F1") (pinfunction "P$2_F1") (pintype "bidirectional"))
      (node (ref "B07") (pin "F2") (pinfunction "P$2_F2") (pintype "bidirectional"))
      (node (ref "B07") (pin "N1") (pinfunction "P$2_N1") (pintype "bidirectional"))
      (node (ref "B07") (pin "N2") (pinfunction "P$2_N2") (pintype "bidirectional"))
      (node (ref "B07") (pin "T1") (pinfunction "P$2_T1") (pintype "bidirectional"))
      (node (ref "B07") (pin "T2") (pinfunction "P$2_T2") (pintype "bidirectional"))
      (node (ref "B08") (pin "C1") (pinfunction "P$2_C1") (pintype "bidirectional"))
      (node (ref "B08") (pin "C2") (pinfunction "P$2_C2") (pintype "bidirectional"))
      (node (ref "B08") (pin "F1") (pinfunction "P$2_F1") (pintype "bidirectional"))
      (node (ref "B08") (pin "F2") (pinfunction "P$2_F2") (pintype "bidirectional"))
      (node (ref "B08") (pin "N1") (pinfunction "P$2_N1") (pintype "bidirectional"))
      (node (ref "B08") (pin "N2") (pinfunction "P$2_N2") (pintype "bidirectional"))
      (node (ref "B08") (pin "T1") (pinfunction "P$2_T1") (pintype "bidirectional"))
      (node (ref "B08") (pin "T2") (pinfunction "P$2_T2") (pintype "bidirectional"))
      (node (ref "B09") (pin "C1") (pinfunction "P$2_C1") (pintype "bidirectional"))
      (node (ref "B09") (pin "C2") (pinfunction "P$2_C2") (pintype "bidirectional"))
      (node (ref "B09") (pin "F1") (pinfunction "P$2_F1") (pintype "bidirectional"))
      (node (ref "B09") (pin "F2") (pinfunction "P$2_F2") (pintype "bidirectional"))
      (node (ref "B09") (pin "N1") (pinfunction "P$2_N1") (pintype "bidirectional"))
      (node (ref "B09") (pin "N2") (pinfunction "P$2_N2") (pintype "bidirectional"))
      (node (ref "B09") (pin "T1") (pinfunction "P$2_T1") (pintype "bidirectional"))
      (node (ref "B09") (pin "T2") (pinfunction "P$2_T2") (pintype "bidirectional"))
      (node (ref "B10") (pin "C1") (pinfunction "P$2_C1") (pintype "bidirectional"))
      (node (ref "B10") (pin "C2") (pinfunction "P$2_C2") (pintype "bidirectional"))
      (node (ref "B10") (pin "F1") (pinfunction "P$2_F1") (pintype "bidirectional"))
      (node (ref "B10") (pin "F2") (pinfunction "P$2_F2") (pintype "bidirectional"))
      (node (ref "B10") (pin "N1") (pinfunction "P$2_N1") (pintype "bidirectional"))
      (node (ref "B10") (pin "N2") (pinfunction "P$2_N2") (pintype "bidirectional"))
      (node (ref "B10") (pin "T1") (pinfunction "P$2_T1") (pintype "bidirectional"))
      (node (ref "B10") (pin "T2") (pinfunction "P$2_T2") (pintype "bidirectional"))
      (node (ref "B11") (pin "C1") (pinfunction "P$2_C1") (pintype "bidirectional"))
      (node (ref "B11") (pin "C2") (pinfunction "P$2_C2") (pintype "bidirectional"))
      (node (ref "B11") (pin "F1") (pinfunction "P$2_F1") (pintype "bidirectional"))
      (node (ref "B11") (pin "F2") (pinfunction "P$2_F2") (pintype "bidirectional"))
      (node (ref "B11") (pin "N1") (pinfunction "P$2_N1") (pintype "bidirectional"))
      (node (ref "B11") (pin "N2") (pinfunction "P$2_N2") (pintype "bidirectional"))
      (node (ref "B11") (pin "T1") (pinfunction "P$2_T1") (pintype "bidirectional"))
      (node (ref "B11") (pin "T2") (pinfunction "P$2_T2") (pintype "bidirectional"))
      (node (ref "B12") (pin "C1") (pinfunction "P$2_C1") (pintype "bidirectional"))
      (node (ref "B12") (pin "C2") (pinfunction "P$2_C2") (pintype "bidirectional"))
      (node (ref "B12") (pin "F1") (pinfunction "P$2_F1") (pintype "bidirectional"))
      (node (ref "B12") (pin "F2") (pinfunction "P$2_F2") (pintype "bidirectional"))
      (node (ref "B12") (pin "N1") (pinfunction "P$2_N1") (pintype "bidirectional"))
      (node (ref "B12") (pin "N2") (pinfunction "P$2_N2") (pintype "bidirectional"))
      (node (ref "B12") (pin "T1") (pinfunction "P$2_T1") (pintype "bidirectional"))
      (node (ref "B12") (pin "T2") (pinfunction "P$2_T2") (pintype "bidirectional"))
      (node (ref "B13") (pin "C1") (pinfunction "P$2_C1") (pintype "bidirectional"))
      (node (ref "B13") (pin "C2") (pinfunction "P$2_C2") (pintype "bidirectional"))
      (node (ref "B13") (pin "F1") (pinfunction "P$2_F1") (pintype "bidirectional"))
      (node (ref "B13") (pin "F2") (pinfunction "P$2_F2") (pintype "bidirectional"))
      (node (ref "B13") (pin "N1") (pinfunction "P$2_N1") (pintype "bidirectional"))
      (node (ref "B13") (pin "N2") (pinfunction "P$2_N2") (pintype "bidirectional"))
      (node (ref "B13") (pin "T1") (pinfunction "P$2_T1") (pintype "bidirectional"))
      (node (ref "B13") (pin "T2") (pinfunction "P$2_T2") (pintype "bidirectional"))
      (node (ref "B14") (pin "C1") (pinfunction "P$2_C1") (pintype "bidirectional"))
      (node (ref "B14") (pin "C2") (pinfunction "P$2_C2") (pintype "bidirectional"))
      (node (ref "B14") (pin "F1") (pinfunction "P$2_F1") (pintype "bidirectional"))
      (node (ref "B14") (pin "F2") (pinfunction "P$2_F2") (pintype "bidirectional"))
      (node (ref "B14") (pin "N1") (pinfunction "P$2_N1") (pintype "bidirectional"))
      (node (ref "B14") (pin "N2") (pinfunction "P$2_N2") (pintype "bidirectional"))
      (node (ref "B14") (pin "T1") (pinfunction "P$2_T1") (pintype "bidirectional"))
      (node (ref "B14") (pin "T2") (pinfunction "P$2_T2") (pintype "bidirectional"))
      (node (ref "B17") (pin "P1") (pinfunction "IN1_P1") (pintype "input"))
      (node (ref "B17") (pin "R1") (pinfunction "IN2_R1") (pintype "input"))
      (node (ref "C01") (pin "C1") (pinfunction "P$2_C1") (pintype "bidirectional"))
      (node (ref "C01") (pin "C2") (pinfunction "P$2_C2") (pintype "bidirectional"))
      (node (ref "C01") (pin "F1") (pinfunction "P$2_F1") (pintype "bidirectional"))
      (node (ref "C01") (pin "F2") (pinfunction "P$2_F2") (pintype "bidirectional"))
      (node (ref "C01") (pin "N1") (pinfunction "P$2_N1") (pintype "bidirectional"))
      (node (ref "C01") (pin "N2") (pinfunction "P$2_N2") (pintype "bidirectional"))
      (node (ref "C01") (pin "T1") (pinfunction "P$2_T1") (pintype "bidirectional"))
      (node (ref "C01") (pin "T2") (pinfunction "P$2_T2") (pintype "bidirectional"))
      (node (ref "C02") (pin "C1") (pinfunction "P$2_C1") (pintype "bidirectional"))
      (node (ref "C02") (pin "C2") (pinfunction "P$2_C2") (pintype "bidirectional"))
      (node (ref "C02") (pin "F1") (pinfunction "P$2_F1") (pintype "bidirectional"))
      (node (ref "C02") (pin "F2") (pinfunction "P$2_F2") (pintype "bidirectional"))
      (node (ref "C02") (pin "N1") (pinfunction "P$2_N1") (pintype "bidirectional"))
      (node (ref "C02") (pin "N2") (pinfunction "P$2_N2") (pintype "bidirectional"))
      (node (ref "C02") (pin "T1") (pinfunction "P$2_T1") (pintype "bidirectional"))
      (node (ref "C02") (pin "T2") (pinfunction "P$2_T2") (pintype "bidirectional"))
      (node (ref "C03") (pin "C1") (pinfunction "P$2_C1") (pintype "bidirectional"))
      (node (ref "C03") (pin "C2") (pinfunction "P$2_C2") (pintype "bidirectional"))
      (node (ref "C03") (pin "F1") (pinfunction "P$2_F1") (pintype "bidirectional"))
      (node (ref "C03") (pin "F2") (pinfunction "P$2_F2") (pintype "bidirectional"))
      (node (ref "C03") (pin "N1") (pinfunction "P$2_N1") (pintype "bidirectional"))
      (node (ref "C03") (pin "N2") (pinfunction "P$2_N2") (pintype "bidirectional"))
      (node (ref "C03") (pin "T1") (pinfunction "P$2_T1") (pintype "bidirectional"))
      (node (ref "C03") (pin "T2") (pinfunction "P$2_T2") (pintype "bidirectional"))
      (node (ref "C04") (pin "C1") (pinfunction "P$2_C1") (pintype "bidirectional"))
      (node (ref "C04") (pin "C2") (pinfunction "P$2_C2") (pintype "bidirectional"))
      (node (ref "C04") (pin "F1") (pinfunction "P$2_F1") (pintype "bidirectional"))
      (node (ref "C04") (pin "F2") (pinfunction "P$2_F2") (pintype "bidirectional"))
      (node (ref "C04") (pin "N1") (pinfunction "P$2_N1") (pintype "bidirectional"))
      (node (ref "C04") (pin "N2") (pinfunction "P$2_N2") (pintype "bidirectional"))
      (node (ref "C04") (pin "T1") (pinfunction "P$2_T1") (pintype "bidirectional"))
      (node (ref "C04") (pin "T2") (pinfunction "P$2_T2") (pintype "bidirectional"))
      (node (ref "C05") (pin "C1") (pinfunction "P$2_C1") (pintype "bidirectional"))
      (node (ref "C05") (pin "C2") (pinfunction "P$2_C2") (pintype "bidirectional"))
      (node (ref "C05") (pin "F1") (pinfunction "P$2_F1") (pintype "bidirectional"))
      (node (ref "C05") (pin "F2") (pinfunction "P$2_F2") (pintype "bidirectional"))
      (node (ref "C05") (pin "N1") (pinfunction "P$2_N1") (pintype "bidirectional"))
      (node (ref "C05") (pin "N2") (pinfunction "P$2_N2") (pintype "bidirectional"))
      (node (ref "C05") (pin "T1") (pinfunction "P$2_T1") (pintype "bidirectional"))
      (node (ref "C05") (pin "T2") (pinfunction "P$2_T2") (pintype "bidirectional"))
      (node (ref "C06") (pin "C1") (pinfunction "P$2_C1") (pintype "bidirectional"))
      (node (ref "C06") (pin "C2") (pinfunction "P$2_C2") (pintype "bidirectional"))
      (node (ref "C06") (pin "F1") (pinfunction "P$2_F1") (pintype "bidirectional"))
      (node (ref "C06") (pin "F2") (pinfunction "P$2_F2") (pintype "bidirectional"))
      (node (ref "C06") (pin "N1") (pinfunction "P$2_N1") (pintype "bidirectional"))
      (node (ref "C06") (pin "N2") (pinfunction "P$2_N2") (pintype "bidirectional"))
      (node (ref "C06") (pin "T1") (pinfunction "P$2_T1") (pintype "bidirectional"))
      (node (ref "C06") (pin "T2") (pinfunction "P$2_T2") (pintype "bidirectional"))
      (node (ref "C07") (pin "C1") (pinfunction "P$2_C1") (pintype "bidirectional"))
      (node (ref "C07") (pin "C2") (pinfunction "P$2_C2") (pintype "bidirectional"))
      (node (ref "C07") (pin "F1") (pinfunction "P$2_F1") (pintype "bidirectional"))
      (node (ref "C07") (pin "F2") (pinfunction "P$2_F2") (pintype "bidirectional"))
      (node (ref "C07") (pin "N1") (pinfunction "P$2_N1") (pintype "bidirectional"))
      (node (ref "C07") (pin "N2") (pinfunction "P$2_N2") (pintype "bidirectional"))
      (node (ref "C07") (pin "T1") (pinfunction "P$2_T1") (pintype "bidirectional"))
      (node (ref "C07") (pin "T2") (pinfunction "P$2_T2") (pintype "bidirectional"))
      (node (ref "C08") (pin "C1") (pinfunction "P$2_C1") (pintype "bidirectional"))
      (node (ref "C08") (pin "C2") (pinfunction "P$2_C2") (pintype "bidirectional"))
      (node (ref "C08") (pin "F1") (pinfunction "P$2_F1") (pintype "bidirectional"))
      (node (ref "C08") (pin "F2") (pinfunction "P$2_F2") (pintype "bidirectional"))
      (node (ref "C08") (pin "N1") (pinfunction "P$2_N1") (pintype "bidirectional"))
      (node (ref "C08") (pin "N2") (pinfunction "P$2_N2") (pintype "bidirectional"))
      (node (ref "C08") (pin "T1") (pinfunction "P$2_T1") (pintype "bidirectional"))
      (node (ref "C08") (pin "T2") (pinfunction "P$2_T2") (pintype "bidirectional"))
      (node (ref "C09") (pin "C1") (pinfunction "P$2_C1") (pintype "bidirectional"))
      (node (ref "C09") (pin "C2") (pinfunction "P$2_C2") (pintype "bidirectional"))
      (node (ref "C09") (pin "F1") (pinfunction "P$2_F1") (pintype "bidirectional"))
      (node (ref "C09") (pin "F2") (pinfunction "P$2_F2") (pintype "bidirectional"))
      (node (ref "C09") (pin "N1") (pinfunction "P$2_N1") (pintype "bidirectional"))
      (node (ref "C09") (pin "N2") (pinfunction "P$2_N2") (pintype "bidirectional"))
      (node (ref "C09") (pin "T1") (pinfunction "P$2_T1") (pintype "bidirectional"))
      (node (ref "C09") (pin "T2") (pinfunction "P$2_T2") (pintype "bidirectional"))
      (node (ref "C10") (pin "C1") (pinfunction "P$2_C1") (pintype "bidirectional"))
      (node (ref "C10") (pin "C2") (pinfunction "P$2_C2") (pintype "bidirectional"))
      (node (ref "C10") (pin "F1") (pinfunction "P$2_F1") (pintype "bidirectional"))
      (node (ref "C10") (pin "F2") (pinfunction "P$2_F2") (pintype "bidirectional"))
      (node (ref "C10") (pin "N1") (pinfunction "P$2_N1") (pintype "bidirectional"))
      (node (ref "C10") (pin "N2") (pinfunction "P$2_N2") (pintype "bidirectional"))
      (node (ref "C10") (pin "T1") (pinfunction "P$2_T1") (pintype "bidirectional"))
      (node (ref "C10") (pin "T2") (pinfunction "P$2_T2") (pintype "bidirectional"))
      (node (ref "C11") (pin "C1") (pinfunction "P$2_C1") (pintype "bidirectional"))
      (node (ref "C11") (pin "C2") (pinfunction "P$2_C2") (pintype "bidirectional"))
      (node (ref "C11") (pin "F1") (pinfunction "P$2_F1") (pintype "bidirectional"))
      (node (ref "C11") (pin "F2") (pinfunction "P$2_F2") (pintype "bidirectional"))
      (node (ref "C11") (pin "N1") (pinfunction "P$2_N1") (pintype "bidirectional"))
      (node (ref "C11") (pin "N2") (pinfunction "P$2_N2") (pintype "bidirectional"))
      (node (ref "C11") (pin "T1") (pinfunction "P$2_T1") (pintype "bidirectional"))
      (node (ref "C11") (pin "T2") (pinfunction "P$2_T2") (pintype "bidirectional"))
      (node (ref "C12") (pin "C1") (pinfunction "P$2_C1") (pintype "bidirectional"))
      (node (ref "C12") (pin "C2") (pinfunction "P$2_C2") (pintype "bidirectional"))
      (node (ref "C12") (pin "F1") (pinfunction "P$2_F1") (pintype "bidirectional"))
      (node (ref "C12") (pin "F2") (pinfunction "P$2_F2") (pintype "bidirectional"))
      (node (ref "C12") (pin "N1") (pinfunction "P$2_N1") (pintype "bidirectional"))
      (node (ref "C12") (pin "N2") (pinfunction "P$2_N2") (pintype "bidirectional"))
      (node (ref "C12") (pin "T1") (pinfunction "P$2_T1") (pintype "bidirectional"))
      (node (ref "C12") (pin "T2") (pinfunction "P$2_T2") (pintype "bidirectional"))
      (node (ref "C13") (pin "C1") (pinfunction "P$2_C1") (pintype "bidirectional"))
      (node (ref "C13") (pin "C2") (pinfunction "P$2_C2") (pintype "bidirectional"))
      (node (ref "C13") (pin "F1") (pinfunction "P$2_F1") (pintype "bidirectional"))
      (node (ref "C13") (pin "F2") (pinfunction "P$2_F2") (pintype "bidirectional"))
      (node (ref "C13") (pin "N1") (pinfunction "P$2_N1") (pintype "bidirectional"))
      (node (ref "C13") (pin "N2") (pinfunction "P$2_N2") (pintype "bidirectional"))
      (node (ref "C13") (pin "T1") (pinfunction "P$2_T1") (pintype "bidirectional"))
      (node (ref "C13") (pin "T2") (pinfunction "P$2_T2") (pintype "bidirectional"))
      (node (ref "C14") (pin "C1") (pinfunction "P$2_C1") (pintype "bidirectional"))
      (node (ref "C14") (pin "C2") (pinfunction "P$2_C2") (pintype "bidirectional"))
      (node (ref "C14") (pin "F1") (pinfunction "P$2_F1") (pintype "bidirectional"))
      (node (ref "C14") (pin "F2") (pinfunction "P$2_F2") (pintype "bidirectional"))
      (node (ref "C14") (pin "N1") (pinfunction "P$2_N1") (pintype "bidirectional"))
      (node (ref "C14") (pin "N2") (pinfunction "P$2_N2") (pintype "bidirectional"))
      (node (ref "C14") (pin "T1") (pinfunction "P$2_T1") (pintype "bidirectional"))
      (node (ref "C14") (pin "T2") (pinfunction "P$2_T2") (pintype "bidirectional"))
      (node (ref "C17") (pin "C1") (pinfunction "D_C1") (pintype "input"))
      (node (ref "C17") (pin "E2") (pinfunction "D_E2") (pintype "input"))
      (node (ref "C17") (pin "J1") (pinfunction "D_J1") (pintype "input"))
      (node (ref "C17") (pin "M2") (pinfunction "D_M2") (pintype "input"))
      (node (ref "C17") (pin "P1") (pinfunction "D_P1") (pintype "input"))
      (node (ref "C17") (pin "T2") (pinfunction "D_T2") (pintype "input"))
      (node (ref "D01") (pin "C1") (pinfunction "P$2_C1") (pintype "bidirectional"))
      (node (ref "D01") (pin "C2") (pinfunction "P$2_C2") (pintype "bidirectional"))
      (node (ref "D01") (pin "F1") (pinfunction "P$2_F1") (pintype "bidirectional"))
      (node (ref "D01") (pin "F2") (pinfunction "P$2_F2") (pintype "bidirectional"))
      (node (ref "D01") (pin "N1") (pinfunction "P$2_N1") (pintype "bidirectional"))
      (node (ref "D01") (pin "N2") (pinfunction "P$2_N2") (pintype "bidirectional"))
      (node (ref "D01") (pin "T1") (pinfunction "P$2_T1") (pintype "bidirectional"))
      (node (ref "D01") (pin "T2") (pinfunction "P$2_T2") (pintype "bidirectional"))
      (node (ref "D02") (pin "C1") (pinfunction "P$2_C1") (pintype "bidirectional"))
      (node (ref "D02") (pin "C2") (pinfunction "P$2_C2") (pintype "bidirectional"))
      (node (ref "D02") (pin "F1") (pinfunction "P$2_F1") (pintype "bidirectional"))
      (node (ref "D02") (pin "F2") (pinfunction "P$2_F2") (pintype "bidirectional"))
      (node (ref "D02") (pin "N1") (pinfunction "P$2_N1") (pintype "bidirectional"))
      (node (ref "D02") (pin "N2") (pinfunction "P$2_N2") (pintype "bidirectional"))
      (node (ref "D02") (pin "T1") (pinfunction "P$2_T1") (pintype "bidirectional"))
      (node (ref "D02") (pin "T2") (pinfunction "P$2_T2") (pintype "bidirectional"))
      (node (ref "D03") (pin "C1") (pinfunction "P$2_C1") (pintype "bidirectional"))
      (node (ref "D03") (pin "C2") (pinfunction "P$2_C2") (pintype "bidirectional"))
      (node (ref "D03") (pin "F1") (pinfunction "P$2_F1") (pintype "bidirectional"))
      (node (ref "D03") (pin "F2") (pinfunction "P$2_F2") (pintype "bidirectional"))
      (node (ref "D03") (pin "N1") (pinfunction "P$2_N1") (pintype "bidirectional"))
      (node (ref "D03") (pin "N2") (pinfunction "P$2_N2") (pintype "bidirectional"))
      (node (ref "D03") (pin "T1") (pinfunction "P$2_T1") (pintype "bidirectional"))
      (node (ref "D03") (pin "T2") (pinfunction "P$2_T2") (pintype "bidirectional"))
      (node (ref "D04") (pin "C1") (pinfunction "P$2_C1") (pintype "bidirectional"))
      (node (ref "D04") (pin "C2") (pinfunction "P$2_C2") (pintype "bidirectional"))
      (node (ref "D04") (pin "F1") (pinfunction "P$2_F1") (pintype "bidirectional"))
      (node (ref "D04") (pin "F2") (pinfunction "P$2_F2") (pintype "bidirectional"))
      (node (ref "D04") (pin "N1") (pinfunction "P$2_N1") (pintype "bidirectional"))
      (node (ref "D04") (pin "N2") (pinfunction "P$2_N2") (pintype "bidirectional"))
      (node (ref "D04") (pin "T1") (pinfunction "P$2_T1") (pintype "bidirectional"))
      (node (ref "D04") (pin "T2") (pinfunction "P$2_T2") (pintype "bidirectional"))
      (node (ref "D05") (pin "C1") (pinfunction "P$2_C1") (pintype "bidirectional"))
      (node (ref "D05") (pin "C2") (pinfunction "P$2_C2") (pintype "bidirectional"))
      (node (ref "D05") (pin "F1") (pinfunction "P$2_F1") (pintype "bidirectional"))
      (node (ref "D05") (pin "F2") (pinfunction "P$2_F2") (pintype "bidirectional"))
      (node (ref "D05") (pin "N1") (pinfunction "P$2_N1") (pintype "bidirectional"))
      (node (ref "D05") (pin "N2") (pinfunction "P$2_N2") (pintype "bidirectional"))
      (node (ref "D05") (pin "T1") (pinfunction "P$2_T1") (pintype "bidirectional"))
      (node (ref "D05") (pin "T2") (pinfunction "P$2_T2") (pintype "bidirectional"))
      (node (ref "D06") (pin "C1") (pinfunction "P$2_C1") (pintype "bidirectional"))
      (node (ref "D06") (pin "C2") (pinfunction "P$2_C2") (pintype "bidirectional"))
      (node (ref "D06") (pin "F1") (pinfunction "P$2_F1") (pintype "bidirectional"))
      (node (ref "D06") (pin "F2") (pinfunction "P$2_F2") (pintype "bidirectional"))
      (node (ref "D06") (pin "N1") (pinfunction "P$2_N1") (pintype "bidirectional"))
      (node (ref "D06") (pin "N2") (pinfunction "P$2_N2") (pintype "bidirectional"))
      (node (ref "D06") (pin "T1") (pinfunction "P$2_T1") (pintype "bidirectional"))
      (node (ref "D06") (pin "T2") (pinfunction "P$2_T2") (pintype "bidirectional"))
      (node (ref "D07") (pin "C1") (pinfunction "P$2_C1") (pintype "bidirectional"))
      (node (ref "D07") (pin "C2") (pinfunction "P$2_C2") (pintype "bidirectional"))
      (node (ref "D07") (pin "F1") (pinfunction "P$2_F1") (pintype "bidirectional"))
      (node (ref "D07") (pin "F2") (pinfunction "P$2_F2") (pintype "bidirectional"))
      (node (ref "D07") (pin "N1") (pinfunction "P$2_N1") (pintype "bidirectional"))
      (node (ref "D07") (pin "N2") (pinfunction "P$2_N2") (pintype "bidirectional"))
      (node (ref "D07") (pin "T1") (pinfunction "P$2_T1") (pintype "bidirectional"))
      (node (ref "D07") (pin "T2") (pinfunction "P$2_T2") (pintype "bidirectional"))
      (node (ref "D08") (pin "C1") (pinfunction "P$2_C1") (pintype "bidirectional"))
      (node (ref "D08") (pin "C2") (pinfunction "P$2_C2") (pintype "bidirectional"))
      (node (ref "D08") (pin "F1") (pinfunction "P$2_F1") (pintype "bidirectional"))
      (node (ref "D08") (pin "F2") (pinfunction "P$2_F2") (pintype "bidirectional"))
      (node (ref "D08") (pin "N1") (pinfunction "P$2_N1") (pintype "bidirectional"))
      (node (ref "D08") (pin "N2") (pinfunction "P$2_N2") (pintype "bidirectional"))
      (node (ref "D08") (pin "T1") (pinfunction "P$2_T1") (pintype "bidirectional"))
      (node (ref "D08") (pin "T2") (pinfunction "P$2_T2") (pintype "bidirectional"))
      (node (ref "D09") (pin "C1") (pinfunction "P$2_C1") (pintype "bidirectional"))
      (node (ref "D09") (pin "C2") (pinfunction "P$2_C2") (pintype "bidirectional"))
      (node (ref "D09") (pin "F1") (pinfunction "P$2_F1") (pintype "bidirectional"))
      (node (ref "D09") (pin "F2") (pinfunction "P$2_F2") (pintype "bidirectional"))
      (node (ref "D09") (pin "N1") (pinfunction "P$2_N1") (pintype "bidirectional"))
      (node (ref "D09") (pin "N2") (pinfunction "P$2_N2") (pintype "bidirectional"))
      (node (ref "D09") (pin "T1") (pinfunction "P$2_T1") (pintype "bidirectional"))
      (node (ref "D09") (pin "T2") (pinfunction "P$2_T2") (pintype "bidirectional"))
      (node (ref "D10") (pin "C1") (pinfunction "P$2_C1") (pintype "bidirectional"))
      (node (ref "D10") (pin "C2") (pinfunction "P$2_C2") (pintype "bidirectional"))
      (node (ref "D10") (pin "F1") (pinfunction "P$2_F1") (pintype "bidirectional"))
      (node (ref "D10") (pin "F2") (pinfunction "P$2_F2") (pintype "bidirectional"))
      (node (ref "D10") (pin "N1") (pinfunction "P$2_N1") (pintype "bidirectional"))
      (node (ref "D10") (pin "N2") (pinfunction "P$2_N2") (pintype "bidirectional"))
      (node (ref "D10") (pin "T1") (pinfunction "P$2_T1") (pintype "bidirectional"))
      (node (ref "D10") (pin "T2") (pinfunction "P$2_T2") (pintype "bidirectional"))
      (node (ref "D11") (pin "C1") (pinfunction "P$2_C1") (pintype "bidirectional"))
      (node (ref "D11") (pin "C2") (pinfunction "P$2_C2") (pintype "bidirectional"))
      (node (ref "D11") (pin "F1") (pinfunction "P$2_F1") (pintype "bidirectional"))
      (node (ref "D11") (pin "F2") (pinfunction "P$2_F2") (pintype "bidirectional"))
      (node (ref "D11") (pin "N1") (pinfunction "P$2_N1") (pintype "bidirectional"))
      (node (ref "D11") (pin "N2") (pinfunction "P$2_N2") (pintype "bidirectional"))
      (node (ref "D11") (pin "T1") (pinfunction "P$2_T1") (pintype "bidirectional"))
      (node (ref "D11") (pin "T2") (pinfunction "P$2_T2") (pintype "bidirectional"))
      (node (ref "D12") (pin "C1") (pinfunction "P$2_C1") (pintype "bidirectional"))
      (node (ref "D12") (pin "C2") (pinfunction "P$2_C2") (pintype "bidirectional"))
      (node (ref "D12") (pin "F1") (pinfunction "P$2_F1") (pintype "bidirectional"))
      (node (ref "D12") (pin "F2") (pinfunction "P$2_F2") (pintype "bidirectional"))
      (node (ref "D12") (pin "N1") (pinfunction "P$2_N1") (pintype "bidirectional"))
      (node (ref "D12") (pin "N2") (pinfunction "P$2_N2") (pintype "bidirectional"))
      (node (ref "D12") (pin "T1") (pinfunction "P$2_T1") (pintype "bidirectional"))
      (node (ref "D12") (pin "T2") (pinfunction "P$2_T2") (pintype "bidirectional"))
      (node (ref "D13") (pin "C1") (pinfunction "P$2_C1") (pintype "bidirectional"))
      (node (ref "D13") (pin "C2") (pinfunction "P$2_C2") (pintype "bidirectional"))
      (node (ref "D13") (pin "F1") (pinfunction "P$2_F1") (pintype "bidirectional"))
      (node (ref "D13") (pin "F2") (pinfunction "P$2_F2") (pintype "bidirectional"))
      (node (ref "D13") (pin "N1") (pinfunction "P$2_N1") (pintype "bidirectional"))
      (node (ref "D13") (pin "N2") (pinfunction "P$2_N2") (pintype "bidirectional"))
      (node (ref "D13") (pin "T1") (pinfunction "P$2_T1") (pintype "bidirectional"))
      (node (ref "D13") (pin "T2") (pinfunction "P$2_T2") (pintype "bidirectional"))
      (node (ref "D14") (pin "C1") (pinfunction "P$2_C1") (pintype "bidirectional"))
      (node (ref "D14") (pin "C2") (pinfunction "P$2_C2") (pintype "bidirectional"))
      (node (ref "D14") (pin "F1") (pinfunction "P$2_F1") (pintype "bidirectional"))
      (node (ref "D14") (pin "F2") (pinfunction "P$2_F2") (pintype "bidirectional"))
      (node (ref "D14") (pin "N1") (pinfunction "P$2_N1") (pintype "bidirectional"))
      (node (ref "D14") (pin "N2") (pinfunction "P$2_N2") (pintype "bidirectional"))
      (node (ref "D14") (pin "T1") (pinfunction "P$2_T1") (pintype "bidirectional"))
      (node (ref "D14") (pin "T2") (pinfunction "P$2_T2") (pintype "bidirectional"))
      (node (ref "D19") (pin "F1") (pinfunction "L3_F1") (pintype "bidirectional"))
      (node (ref "GND") (pin "1") (pinfunction "P_1") (pintype "passive"))
    )
    (net (code "110") (name "Net-(A01A-P$2)") (class "Default")
      (node (ref "A01") (pin "A1") (pinfunction "P$2_A1") (pintype "bidirectional"))
      (node (ref "A02") (pin "A1") (pinfunction "P$2_A1") (pintype "bidirectional"))
      (node (ref "A03") (pin "A1") (pinfunction "P$2_A1") (pintype "bidirectional"))
      (node (ref "A04") (pin "A1") (pinfunction "P$2_A1") (pintype "bidirectional"))
      (node (ref "A05") (pin "A1") (pinfunction "P$2_A1") (pintype "bidirectional"))
      (node (ref "A06") (pin "A1") (pinfunction "P$2_A1") (pintype "bidirectional"))
      (node (ref "A07") (pin "A1") (pinfunction "P$2_A1") (pintype "bidirectional"))
      (node (ref "A08") (pin "A1") (pinfunction "P$2_A1") (pintype "bidirectional"))
      (node (ref "A09") (pin "A1") (pinfunction "P$2_A1") (pintype "bidirectional"))
      (node (ref "A10") (pin "A1") (pinfunction "P$2_A1") (pintype "bidirectional"))
      (node (ref "A11") (pin "A1") (pinfunction "P$2_A1") (pintype "bidirectional"))
      (node (ref "A12") (pin "A1") (pinfunction "P$2_A1") (pintype "bidirectional"))
      (node (ref "A13") (pin "A1") (pinfunction "P$2_A1") (pintype "bidirectional"))
      (node (ref "A14") (pin "A1") (pinfunction "P$2_A1") (pintype "bidirectional"))
    )
    (net (code "111") (name "Net-(A01AA-P$2)") (class "Default")
      (node (ref "A01") (pin "R1") (pinfunction "P$2_R1") (pintype "bidirectional"))
      (node (ref "A02") (pin "R1") (pinfunction "P$2_R1") (pintype "bidirectional"))
      (node (ref "A03") (pin "R1") (pinfunction "P$2_R1") (pintype "bidirectional"))
      (node (ref "A04") (pin "R1") (pinfunction "P$2_R1") (pintype "bidirectional"))
      (node (ref "A05") (pin "R1") (pinfunction "P$2_R1") (pintype "bidirectional"))
      (node (ref "A06") (pin "R1") (pinfunction "P$2_R1") (pintype "bidirectional"))
      (node (ref "A07") (pin "R1") (pinfunction "P$2_R1") (pintype "bidirectional"))
      (node (ref "A08") (pin "R1") (pinfunction "P$2_R1") (pintype "bidirectional"))
      (node (ref "A09") (pin "R1") (pinfunction "P$2_R1") (pintype "bidirectional"))
      (node (ref "A10") (pin "R1") (pinfunction "P$2_R1") (pintype "bidirectional"))
      (node (ref "A11") (pin "R1") (pinfunction "P$2_R1") (pintype "bidirectional"))
      (node (ref "A12") (pin "R1") (pinfunction "P$2_R1") (pintype "bidirectional"))
      (node (ref "A13") (pin "R1") (pinfunction "P$2_R1") (pintype "bidirectional"))
      (node (ref "A14") (pin "R1") (pinfunction "P$2_R1") (pintype "bidirectional"))
    )
    (net (code "112") (name "Net-(A01AC-P$2)") (class "Default")
      (node (ref "A01") (pin "S1") (pinfunction "P$2_S1") (pintype "bidirectional"))
      (node (ref "A02") (pin "S1") (pinfunction "P$2_S1") (pintype "bidirectional"))
      (node (ref "A03") (pin "S1") (pinfunction "P$2_S1") (pintype "bidirectional"))
      (node (ref "A04") (pin "S1") (pinfunction "P$2_S1") (pintype "bidirectional"))
      (node (ref "A05") (pin "S1") (pinfunction "P$2_S1") (pintype "bidirectional"))
      (node (ref "A06") (pin "S1") (pinfunction "P$2_S1") (pintype "bidirectional"))
      (node (ref "A07") (pin "S1") (pinfunction "P$2_S1") (pintype "bidirectional"))
      (node (ref "A08") (pin "S1") (pinfunction "P$2_S1") (pintype "bidirectional"))
      (node (ref "A09") (pin "S1") (pinfunction "P$2_S1") (pintype "bidirectional"))
      (node (ref "A10") (pin "S1") (pinfunction "P$2_S1") (pintype "bidirectional"))
      (node (ref "A11") (pin "S1") (pinfunction "P$2_S1") (pintype "bidirectional"))
      (node (ref "A12") (pin "S1") (pinfunction "P$2_S1") (pintype "bidirectional"))
      (node (ref "A13") (pin "S1") (pinfunction "P$2_S1") (pintype "bidirectional"))
      (node (ref "A14") (pin "S1") (pinfunction "P$2_S1") (pintype "bidirectional"))
    )
    (net (code "113") (name "Net-(A01AG-P$2)") (class "Default")
      (node (ref "A01") (pin "U1") (pinfunction "P$2_U1") (pintype "bidirectional"))
      (node (ref "A02") (pin "U1") (pinfunction "P$2_U1") (pintype "bidirectional"))
      (node (ref "A03") (pin "U1") (pinfunction "P$2_U1") (pintype "bidirectional"))
      (node (ref "A04") (pin "U1") (pinfunction "P$2_U1") (pintype "bidirectional"))
      (node (ref "A05") (pin "U1") (pinfunction "P$2_U1") (pintype "bidirectional"))
      (node (ref "A06") (pin "U1") (pinfunction "P$2_U1") (pintype "bidirectional"))
      (node (ref "A07") (pin "U1") (pinfunction "P$2_U1") (pintype "bidirectional"))
      (node (ref "A08") (pin "U1") (pinfunction "P$2_U1") (pintype "bidirectional"))
      (node (ref "A09") (pin "U1") (pinfunction "P$2_U1") (pintype "bidirectional"))
      (node (ref "A10") (pin "U1") (pinfunction "P$2_U1") (pintype "bidirectional"))
      (node (ref "A11") (pin "U1") (pinfunction "P$2_U1") (pintype "bidirectional"))
      (node (ref "A12") (pin "U1") (pinfunction "P$2_U1") (pintype "bidirectional"))
      (node (ref "A13") (pin "U1") (pinfunction "P$2_U1") (pintype "bidirectional"))
      (node (ref "A14") (pin "U1") (pinfunction "P$2_U1") (pintype "bidirectional"))
    )
    (net (code "114") (name "Net-(A01AI-P$2)") (class "Default")
      (node (ref "A01") (pin "V1") (pinfunction "P$2_V1") (pintype "bidirectional"))
      (node (ref "A02") (pin "V1") (pinfunction "P$2_V1") (pintype "bidirectional"))
      (node (ref "A03") (pin "V1") (pinfunction "P$2_V1") (pintype "bidirectional"))
      (node (ref "A04") (pin "V1") (pinfunction "P$2_V1") (pintype "bidirectional"))
      (node (ref "A05") (pin "V1") (pinfunction "P$2_V1") (pintype "bidirectional"))
      (node (ref "A06") (pin "V1") (pinfunction "P$2_V1") (pintype "bidirectional"))
      (node (ref "A07") (pin "V1") (pinfunction "P$2_V1") (pintype "bidirectional"))
      (node (ref "A08") (pin "V1") (pinfunction "P$2_V1") (pintype "bidirectional"))
      (node (ref "A09") (pin "V1") (pinfunction "P$2_V1") (pintype "bidirectional"))
      (node (ref "A10") (pin "V1") (pinfunction "P$2_V1") (pintype "bidirectional"))
      (node (ref "A11") (pin "V1") (pinfunction "P$2_V1") (pintype "bidirectional"))
      (node (ref "A12") (pin "V1") (pinfunction "P$2_V1") (pintype "bidirectional"))
      (node (ref "A13") (pin "V1") (pinfunction "P$2_V1") (pintype "bidirectional"))
      (node (ref "A14") (pin "V1") (pinfunction "P$2_V1") (pintype "bidirectional"))
    )
    (net (code "115") (name "Net-(A01AJ-P$2)") (class "Default")
      (node (ref "A01") (pin "V2") (pinfunction "P$2_V2") (pintype "bidirectional"))
      (node (ref "A02") (pin "V2") (pinfunction "P$2_V2") (pintype "bidirectional"))
      (node (ref "A03") (pin "V2") (pinfunction "P$2_V2") (pintype "bidirectional"))
      (node (ref "A04") (pin "V2") (pinfunction "P$2_V2") (pintype "bidirectional"))
      (node (ref "A05") (pin "V2") (pinfunction "P$2_V2") (pintype "bidirectional"))
      (node (ref "A06") (pin "V2") (pinfunction "P$2_V2") (pintype "bidirectional"))
      (node (ref "A07") (pin "V2") (pinfunction "P$2_V2") (pintype "bidirectional"))
      (node (ref "A08") (pin "V2") (pinfunction "P$2_V2") (pintype "bidirectional"))
      (node (ref "A09") (pin "V2") (pinfunction "P$2_V2") (pintype "bidirectional"))
      (node (ref "A10") (pin "V2") (pinfunction "P$2_V2") (pintype "bidirectional"))
      (node (ref "A11") (pin "V2") (pinfunction "P$2_V2") (pintype "bidirectional"))
      (node (ref "A12") (pin "V2") (pinfunction "P$2_V2") (pintype "bidirectional"))
      (node (ref "A13") (pin "V2") (pinfunction "P$2_V2") (pintype "bidirectional"))
      (node (ref "A14") (pin "V2") (pinfunction "P$2_V2") (pintype "bidirectional"))
    )
    (net (code "116") (name "Net-(A01C-P$2)") (class "Default")
      (node (ref "A01") (pin "B1") (pinfunction "P$2_B1") (pintype "bidirectional"))
      (node (ref "A02") (pin "B1") (pinfunction "P$2_B1") (pintype "bidirectional"))
      (node (ref "A03") (pin "B1") (pinfunction "P$2_B1") (pintype "bidirectional"))
      (node (ref "A04") (pin "B1") (pinfunction "P$2_B1") (pintype "bidirectional"))
      (node (ref "A05") (pin "B1") (pinfunction "P$2_B1") (pintype "bidirectional"))
      (node (ref "A06") (pin "B1") (pinfunction "P$2_B1") (pintype "bidirectional"))
      (node (ref "A07") (pin "B1") (pinfunction "P$2_B1") (pintype "bidirectional"))
      (node (ref "A08") (pin "B1") (pinfunction "P$2_B1") (pintype "bidirectional"))
      (node (ref "A09") (pin "B1") (pinfunction "P$2_B1") (pintype "bidirectional"))
      (node (ref "A10") (pin "B1") (pinfunction "P$2_B1") (pintype "bidirectional"))
      (node (ref "A11") (pin "B1") (pinfunction "P$2_B1") (pintype "bidirectional"))
      (node (ref "A12") (pin "B1") (pinfunction "P$2_B1") (pintype "bidirectional"))
      (node (ref "A13") (pin "B1") (pinfunction "P$2_B1") (pintype "bidirectional"))
      (node (ref "A14") (pin "B1") (pinfunction "P$2_B1") (pintype "bidirectional"))
    )
    (net (code "117") (name "Net-(A01P-P$2)") (class "Default")
      (node (ref "A01") (pin "J2") (pinfunction "P$2_J2") (pintype "bidirectional"))
      (node (ref "A02") (pin "J2") (pinfunction "P$2_J2") (pintype "bidirectional"))
      (node (ref "A03") (pin "J2") (pinfunction "P$2_J2") (pintype "bidirectional"))
      (node (ref "A04") (pin "J2") (pinfunction "P$2_J2") (pintype "bidirectional"))
      (node (ref "A05") (pin "J2") (pinfunction "P$2_J2") (pintype "bidirectional"))
      (node (ref "A06") (pin "J2") (pinfunction "P$2_J2") (pintype "bidirectional"))
      (node (ref "A07") (pin "J2") (pinfunction "P$2_J2") (pintype "bidirectional"))
      (node (ref "A08") (pin "J2") (pinfunction "P$2_J2") (pintype "bidirectional"))
      (node (ref "A09") (pin "J2") (pinfunction "P$2_J2") (pintype "bidirectional"))
      (node (ref "A10") (pin "J2") (pinfunction "P$2_J2") (pintype "bidirectional"))
      (node (ref "A11") (pin "J2") (pinfunction "P$2_J2") (pintype "bidirectional"))
      (node (ref "A12") (pin "J2") (pinfunction "P$2_J2") (pintype "bidirectional"))
      (node (ref "A13") (pin "J2") (pinfunction "P$2_J2") (pintype "bidirectional"))
      (node (ref "A14") (pin "J2") (pinfunction "P$2_J2") (pintype "bidirectional"))
    )
    (net (code "118") (name "Net-(A15A-IN4)") (class "Default")
      (node (ref "A15") (pin "D1") (pinfunction "IN4_D1") (pintype "input"))
      (node (ref "C17") (pin "J2") (pinfunction "0_J2") (pintype "output"))
    )
    (net (code "119") (name "Net-(A15D-IN4)") (class "Default")
      (node (ref "A15") (pin "H2") (pinfunction "IN4_H2") (pintype "input"))
      (node (ref "C17") (pin "U1") (pinfunction "0_U1") (pintype "output"))
    )
    (net (code "120") (name "Net-(A15E-IN4)") (class "Default")
      (node (ref "A15") (pin "K1") (pinfunction "IN4_K1") (pintype "input"))
      (node (ref "C17") (pin "M1") (pinfunction "0_M1") (pintype "output"))
    )
    (net (code "121") (name "Net-(A15F-IN4)") (class "Default")
      (node (ref "A15") (pin "N2") (pinfunction "IN4_N2") (pintype "input"))
      (node (ref "C17") (pin "R2") (pinfunction "0_R2") (pintype "output"))
    )
    (net (code "122") (name "Net-(A15G-IN4)") (class "Default")
      (node (ref "A15") (pin "R1") (pinfunction "IN4_R1") (pintype "input"))
      (node (ref "C17") (pin "V1") (pinfunction "0_V1") (pintype "output"))
    )
    (net (code "123") (name "Net-(B01A-P$2)") (class "Default")
      (node (ref "B01") (pin "A1") (pinfunction "P$2_A1") (pintype "bidirectional"))
      (node (ref "B02") (pin "A1") (pinfunction "P$2_A1") (pintype "bidirectional"))
      (node (ref "B03") (pin "A1") (pinfunction "P$2_A1") (pintype "bidirectional"))
      (node (ref "B04") (pin "A1") (pinfunction "P$2_A1") (pintype "bidirectional"))
      (node (ref "B05") (pin "A1") (pinfunction "P$2_A1") (pintype "bidirectional"))
      (node (ref "B06") (pin "A1") (pinfunction "P$2_A1") (pintype "bidirectional"))
      (node (ref "B07") (pin "A1") (pinfunction "P$2_A1") (pintype "bidirectional"))
      (node (ref "B08") (pin "A1") (pinfunction "P$2_A1") (pintype "bidirectional"))
      (node (ref "B09") (pin "A1") (pinfunction "P$2_A1") (pintype "bidirectional"))
      (node (ref "B10") (pin "A1") (pinfunction "P$2_A1") (pintype "bidirectional"))
      (node (ref "B11") (pin "A1") (pinfunction "P$2_A1") (pintype "bidirectional"))
      (node (ref "B12") (pin "A1") (pinfunction "P$2_A1") (pintype "bidirectional"))
      (node (ref "B13") (pin "A1") (pinfunction "P$2_A1") (pintype "bidirectional"))
      (node (ref "B14") (pin "A1") (pinfunction "P$2_A1") (pintype "bidirectional"))
    )
    (net (code "124") (name "Net-(B01AA-P$2)") (class "Default")
      (node (ref "B01") (pin "R1") (pinfunction "P$2_R1") (pintype "bidirectional"))
      (node (ref "B02") (pin "R1") (pinfunction "P$2_R1") (pintype "bidirectional"))
      (node (ref "B03") (pin "R1") (pinfunction "P$2_R1") (pintype "bidirectional"))
      (node (ref "B04") (pin "R1") (pinfunction "P$2_R1") (pintype "bidirectional"))
      (node (ref "B05") (pin "R1") (pinfunction "P$2_R1") (pintype "bidirectional"))
      (node (ref "B06") (pin "R1") (pinfunction "P$2_R1") (pintype "bidirectional"))
      (node (ref "B07") (pin "R1") (pinfunction "P$2_R1") (pintype "bidirectional"))
      (node (ref "B08") (pin "R1") (pinfunction "P$2_R1") (pintype "bidirectional"))
      (node (ref "B09") (pin "R1") (pinfunction "P$2_R1") (pintype "bidirectional"))
      (node (ref "B10") (pin "R1") (pinfunction "P$2_R1") (pintype "bidirectional"))
      (node (ref "B11") (pin "R1") (pinfunction "P$2_R1") (pintype "bidirectional"))
      (node (ref "B12") (pin "R1") (pinfunction "P$2_R1") (pintype "bidirectional"))
      (node (ref "B13") (pin "R1") (pinfunction "P$2_R1") (pintype "bidirectional"))
      (node (ref "B14") (pin "R1") (pinfunction "P$2_R1") (pintype "bidirectional"))
    )
    (net (code "125") (name "Net-(B01AB-P$2)") (class "Default")
      (node (ref "B01") (pin "R2") (pinfunction "P$2_R2") (pintype "bidirectional"))
      (node (ref "B02") (pin "R2") (pinfunction "P$2_R2") (pintype "bidirectional"))
      (node (ref "B03") (pin "R2") (pinfunction "P$2_R2") (pintype "bidirectional"))
      (node (ref "B04") (pin "R2") (pinfunction "P$2_R2") (pintype "bidirectional"))
      (node (ref "B05") (pin "R2") (pinfunction "P$2_R2") (pintype "bidirectional"))
      (node (ref "B06") (pin "R2") (pinfunction "P$2_R2") (pintype "bidirectional"))
      (node (ref "B07") (pin "R2") (pinfunction "P$2_R2") (pintype "bidirectional"))
      (node (ref "B08") (pin "R2") (pinfunction "P$2_R2") (pintype "bidirectional"))
      (node (ref "B09") (pin "R2") (pinfunction "P$2_R2") (pintype "bidirectional"))
      (node (ref "B10") (pin "R2") (pinfunction "P$2_R2") (pintype "bidirectional"))
      (node (ref "B11") (pin "R2") (pinfunction "P$2_R2") (pintype "bidirectional"))
      (node (ref "B12") (pin "R2") (pinfunction "P$2_R2") (pintype "bidirectional"))
      (node (ref "B13") (pin "R2") (pinfunction "P$2_R2") (pintype "bidirectional"))
      (node (ref "B14") (pin "R2") (pinfunction "P$2_R2") (pintype "bidirectional"))
    )
    (net (code "126") (name "Net-(B01AC-P$2)") (class "Default")
      (node (ref "B01") (pin "S1") (pinfunction "P$2_S1") (pintype "bidirectional"))
      (node (ref "B02") (pin "S1") (pinfunction "P$2_S1") (pintype "bidirectional"))
      (node (ref "B03") (pin "S1") (pinfunction "P$2_S1") (pintype "bidirectional"))
      (node (ref "B04") (pin "S1") (pinfunction "P$2_S1") (pintype "bidirectional"))
      (node (ref "B05") (pin "S1") (pinfunction "P$2_S1") (pintype "bidirectional"))
      (node (ref "B06") (pin "S1") (pinfunction "P$2_S1") (pintype "bidirectional"))
      (node (ref "B07") (pin "S1") (pinfunction "P$2_S1") (pintype "bidirectional"))
      (node (ref "B08") (pin "S1") (pinfunction "P$2_S1") (pintype "bidirectional"))
      (node (ref "B09") (pin "S1") (pinfunction "P$2_S1") (pintype "bidirectional"))
      (node (ref "B10") (pin "S1") (pinfunction "P$2_S1") (pintype "bidirectional"))
      (node (ref "B11") (pin "S1") (pinfunction "P$2_S1") (pintype "bidirectional"))
      (node (ref "B12") (pin "S1") (pinfunction "P$2_S1") (pintype "bidirectional"))
      (node (ref "B13") (pin "S1") (pinfunction "P$2_S1") (pintype "bidirectional"))
      (node (ref "B14") (pin "S1") (pinfunction "P$2_S1") (pintype "bidirectional"))
    )
    (net (code "127") (name "Net-(B01AD-P$2)") (class "Default")
      (node (ref "B01") (pin "S2") (pinfunction "P$2_S2") (pintype "bidirectional"))
      (node (ref "B02") (pin "S2") (pinfunction "P$2_S2") (pintype "bidirectional"))
      (node (ref "B03") (pin "S2") (pinfunction "P$2_S2") (pintype "bidirectional"))
      (node (ref "B04") (pin "S2") (pinfunction "P$2_S2") (pintype "bidirectional"))
      (node (ref "B05") (pin "S2") (pinfunction "P$2_S2") (pintype "bidirectional"))
      (node (ref "B06") (pin "S2") (pinfunction "P$2_S2") (pintype "bidirectional"))
      (node (ref "B07") (pin "S2") (pinfunction "P$2_S2") (pintype "bidirectional"))
      (node (ref "B08") (pin "S2") (pinfunction "P$2_S2") (pintype "bidirectional"))
      (node (ref "B09") (pin "S2") (pinfunction "P$2_S2") (pintype "bidirectional"))
      (node (ref "B10") (pin "S2") (pinfunction "P$2_S2") (pintype "bidirectional"))
      (node (ref "B11") (pin "S2") (pinfunction "P$2_S2") (pintype "bidirectional"))
      (node (ref "B12") (pin "S2") (pinfunction "P$2_S2") (pintype "bidirectional"))
      (node (ref "B13") (pin "S2") (pinfunction "P$2_S2") (pintype "bidirectional"))
      (node (ref "B14") (pin "S2") (pinfunction "P$2_S2") (pintype "bidirectional"))
    )
    (net (code "128") (name "Net-(B01AG-P$2)") (class "Default")
      (node (ref "B01") (pin "U1") (pinfunction "P$2_U1") (pintype "bidirectional"))
      (node (ref "B02") (pin "U1") (pinfunction "P$2_U1") (pintype "bidirectional"))
      (node (ref "B03") (pin "U1") (pinfunction "P$2_U1") (pintype "bidirectional"))
      (node (ref "B04") (pin "U1") (pinfunction "P$2_U1") (pintype "bidirectional"))
      (node (ref "B05") (pin "U1") (pinfunction "P$2_U1") (pintype "bidirectional"))
      (node (ref "B06") (pin "U1") (pinfunction "P$2_U1") (pintype "bidirectional"))
      (node (ref "B07") (pin "U1") (pinfunction "P$2_U1") (pintype "bidirectional"))
      (node (ref "B08") (pin "U1") (pinfunction "P$2_U1") (pintype "bidirectional"))
      (node (ref "B09") (pin "U1") (pinfunction "P$2_U1") (pintype "bidirectional"))
      (node (ref "B10") (pin "U1") (pinfunction "P$2_U1") (pintype "bidirectional"))
      (node (ref "B11") (pin "U1") (pinfunction "P$2_U1") (pintype "bidirectional"))
      (node (ref "B12") (pin "U1") (pinfunction "P$2_U1") (pintype "bidirectional"))
      (node (ref "B13") (pin "U1") (pinfunction "P$2_U1") (pintype "bidirectional"))
      (node (ref "B14") (pin "U1") (pinfunction "P$2_U1") (pintype "bidirectional"))
    )
    (net (code "129") (name "Net-(B01AH-P$2)") (class "Default")
      (node (ref "B01") (pin "U2") (pinfunction "P$2_U2") (pintype "bidirectional"))
      (node (ref "B02") (pin "U2") (pinfunction "P$2_U2") (pintype "bidirectional"))
      (node (ref "B03") (pin "U2") (pinfunction "P$2_U2") (pintype "bidirectional"))
      (node (ref "B04") (pin "U2") (pinfunction "P$2_U2") (pintype "bidirectional"))
      (node (ref "B05") (pin "U2") (pinfunction "P$2_U2") (pintype "bidirectional"))
      (node (ref "B06") (pin "U2") (pinfunction "P$2_U2") (pintype "bidirectional"))
      (node (ref "B07") (pin "U2") (pinfunction "P$2_U2") (pintype "bidirectional"))
      (node (ref "B08") (pin "U2") (pinfunction "P$2_U2") (pintype "bidirectional"))
      (node (ref "B09") (pin "U2") (pinfunction "P$2_U2") (pintype "bidirectional"))
      (node (ref "B10") (pin "U2") (pinfunction "P$2_U2") (pintype "bidirectional"))
      (node (ref "B11") (pin "U2") (pinfunction "P$2_U2") (pintype "bidirectional"))
      (node (ref "B12") (pin "U2") (pinfunction "P$2_U2") (pintype "bidirectional"))
      (node (ref "B13") (pin "U2") (pinfunction "P$2_U2") (pintype "bidirectional"))
      (node (ref "B14") (pin "U2") (pinfunction "P$2_U2") (pintype "bidirectional"))
    )
    (net (code "130") (name "Net-(B01AI-P$2)") (class "Default")
      (node (ref "B01") (pin "V1") (pinfunction "P$2_V1") (pintype "bidirectional"))
      (node (ref "B02") (pin "V1") (pinfunction "P$2_V1") (pintype "bidirectional"))
      (node (ref "B03") (pin "V1") (pinfunction "P$2_V1") (pintype "bidirectional"))
      (node (ref "B04") (pin "V1") (pinfunction "P$2_V1") (pintype "bidirectional"))
      (node (ref "B05") (pin "V1") (pinfunction "P$2_V1") (pintype "bidirectional"))
      (node (ref "B06") (pin "V1") (pinfunction "P$2_V1") (pintype "bidirectional"))
      (node (ref "B07") (pin "V1") (pinfunction "P$2_V1") (pintype "bidirectional"))
      (node (ref "B08") (pin "V1") (pinfunction "P$2_V1") (pintype "bidirectional"))
      (node (ref "B09") (pin "V1") (pinfunction "P$2_V1") (pintype "bidirectional"))
      (node (ref "B10") (pin "V1") (pinfunction "P$2_V1") (pintype "bidirectional"))
      (node (ref "B11") (pin "V1") (pinfunction "P$2_V1") (pintype "bidirectional"))
      (node (ref "B12") (pin "V1") (pinfunction "P$2_V1") (pintype "bidirectional"))
      (node (ref "B13") (pin "V1") (pinfunction "P$2_V1") (pintype "bidirectional"))
      (node (ref "B14") (pin "V1") (pinfunction "P$2_V1") (pintype "bidirectional"))
    )
    (net (code "131") (name "Net-(B01C-P$2)") (class "Default")
      (node (ref "B01") (pin "B1") (pinfunction "P$2_B1") (pintype "bidirectional"))
      (node (ref "B02") (pin "B1") (pinfunction "P$2_B1") (pintype "bidirectional"))
      (node (ref "B03") (pin "B1") (pinfunction "P$2_B1") (pintype "bidirectional"))
      (node (ref "B04") (pin "B1") (pinfunction "P$2_B1") (pintype "bidirectional"))
      (node (ref "B05") (pin "B1") (pinfunction "P$2_B1") (pintype "bidirectional"))
      (node (ref "B06") (pin "B1") (pinfunction "P$2_B1") (pintype "bidirectional"))
      (node (ref "B07") (pin "B1") (pinfunction "P$2_B1") (pintype "bidirectional"))
      (node (ref "B08") (pin "B1") (pinfunction "P$2_B1") (pintype "bidirectional"))
      (node (ref "B09") (pin "B1") (pinfunction "P$2_B1") (pintype "bidirectional"))
      (node (ref "B10") (pin "B1") (pinfunction "P$2_B1") (pintype "bidirectional"))
      (node (ref "B11") (pin "B1") (pinfunction "P$2_B1") (pintype "bidirectional"))
      (node (ref "B12") (pin "B1") (pinfunction "P$2_B1") (pintype "bidirectional"))
      (node (ref "B13") (pin "B1") (pinfunction "P$2_B1") (pintype "bidirectional"))
      (node (ref "B14") (pin "B1") (pinfunction "P$2_B1") (pintype "bidirectional"))
    )
    (net (code "132") (name "Net-(B01H-P$2)") (class "Default")
      (node (ref "B01") (pin "D2") (pinfunction "P$2_D2") (pintype "bidirectional"))
      (node (ref "B02") (pin "D2") (pinfunction "P$2_D2") (pintype "bidirectional"))
      (node (ref "B03") (pin "D2") (pinfunction "P$2_D2") (pintype "bidirectional"))
      (node (ref "B04") (pin "D2") (pinfunction "P$2_D2") (pintype "bidirectional"))
      (node (ref "B05") (pin "D2") (pinfunction "P$2_D2") (pintype "bidirectional"))
      (node (ref "B06") (pin "D2") (pinfunction "P$2_D2") (pintype "bidirectional"))
      (node (ref "B07") (pin "D2") (pinfunction "P$2_D2") (pintype "bidirectional"))
      (node (ref "B08") (pin "D2") (pinfunction "P$2_D2") (pintype "bidirectional"))
      (node (ref "B09") (pin "D2") (pinfunction "P$2_D2") (pintype "bidirectional"))
      (node (ref "B10") (pin "D2") (pinfunction "P$2_D2") (pintype "bidirectional"))
      (node (ref "B11") (pin "D2") (pinfunction "P$2_D2") (pintype "bidirectional"))
      (node (ref "B12") (pin "D2") (pinfunction "P$2_D2") (pintype "bidirectional"))
      (node (ref "B13") (pin "D2") (pinfunction "P$2_D2") (pintype "bidirectional"))
      (node (ref "B14") (pin "D2") (pinfunction "P$2_D2") (pintype "bidirectional"))
    )
    (net (code "133") (name "Net-(B01J-P$2)") (class "Default")
      (node (ref "B01") (pin "E2") (pinfunction "P$2_E2") (pintype "bidirectional"))
      (node (ref "B02") (pin "E2") (pinfunction "P$2_E2") (pintype "bidirectional"))
      (node (ref "B03") (pin "E2") (pinfunction "P$2_E2") (pintype "bidirectional"))
      (node (ref "B04") (pin "E2") (pinfunction "P$2_E2") (pintype "bidirectional"))
      (node (ref "B05") (pin "E2") (pinfunction "P$2_E2") (pintype "bidirectional"))
      (node (ref "B06") (pin "E2") (pinfunction "P$2_E2") (pintype "bidirectional"))
      (node (ref "B07") (pin "E2") (pinfunction "P$2_E2") (pintype "bidirectional"))
      (node (ref "B08") (pin "E2") (pinfunction "P$2_E2") (pintype "bidirectional"))
      (node (ref "B09") (pin "E2") (pinfunction "P$2_E2") (pintype "bidirectional"))
      (node (ref "B10") (pin "E2") (pinfunction "P$2_E2") (pintype "bidirectional"))
      (node (ref "B11") (pin "E2") (pinfunction "P$2_E2") (pintype "bidirectional"))
      (node (ref "B12") (pin "E2") (pinfunction "P$2_E2") (pintype "bidirectional"))
      (node (ref "B13") (pin "E2") (pinfunction "P$2_E2") (pintype "bidirectional"))
      (node (ref "B14") (pin "E2") (pinfunction "P$2_E2") (pintype "bidirectional"))
    )
    (net (code "134") (name "Net-(B01N-P$2)") (class "Default")
      (node (ref "B01") (pin "H2") (pinfunction "P$2_H2") (pintype "bidirectional"))
      (node (ref "B02") (pin "H2") (pinfunction "P$2_H2") (pintype "bidirectional"))
      (node (ref "B03") (pin "H2") (pinfunction "P$2_H2") (pintype "bidirectional"))
      (node (ref "B04") (pin "H2") (pinfunction "P$2_H2") (pintype "bidirectional"))
      (node (ref "B05") (pin "H2") (pinfunction "P$2_H2") (pintype "bidirectional"))
      (node (ref "B06") (pin "H2") (pinfunction "P$2_H2") (pintype "bidirectional"))
      (node (ref "B07") (pin "H2") (pinfunction "P$2_H2") (pintype "bidirectional"))
      (node (ref "B08") (pin "H2") (pinfunction "P$2_H2") (pintype "bidirectional"))
      (node (ref "B09") (pin "H2") (pinfunction "P$2_H2") (pintype "bidirectional"))
      (node (ref "B10") (pin "H2") (pinfunction "P$2_H2") (pintype "bidirectional"))
      (node (ref "B11") (pin "H2") (pinfunction "P$2_H2") (pintype "bidirectional"))
      (node (ref "B12") (pin "H2") (pinfunction "P$2_H2") (pintype "bidirectional"))
      (node (ref "B13") (pin "H2") (pinfunction "P$2_H2") (pintype "bidirectional"))
      (node (ref "B14") (pin "H2") (pinfunction "P$2_H2") (pintype "bidirectional"))
    )
    (net (code "135") (name "Net-(B01P-P$2)") (class "Default")
      (node (ref "B01") (pin "J2") (pinfunction "P$2_J2") (pintype "bidirectional"))
      (node (ref "B02") (pin "J2") (pinfunction "P$2_J2") (pintype "bidirectional"))
      (node (ref "B03") (pin "J2") (pinfunction "P$2_J2") (pintype "bidirectional"))
      (node (ref "B04") (pin "J2") (pinfunction "P$2_J2") (pintype "bidirectional"))
      (node (ref "B05") (pin "J2") (pinfunction "P$2_J2") (pintype "bidirectional"))
      (node (ref "B06") (pin "J2") (pinfunction "P$2_J2") (pintype "bidirectional"))
      (node (ref "B07") (pin "J2") (pinfunction "P$2_J2") (pintype "bidirectional"))
      (node (ref "B08") (pin "J2") (pinfunction "P$2_J2") (pintype "bidirectional"))
      (node (ref "B09") (pin "J2") (pinfunction "P$2_J2") (pintype "bidirectional"))
      (node (ref "B10") (pin "J2") (pinfunction "P$2_J2") (pintype "bidirectional"))
      (node (ref "B11") (pin "J2") (pinfunction "P$2_J2") (pintype "bidirectional"))
      (node (ref "B12") (pin "J2") (pinfunction "P$2_J2") (pintype "bidirectional"))
      (node (ref "B13") (pin "J2") (pinfunction "P$2_J2") (pintype "bidirectional"))
      (node (ref "B14") (pin "J2") (pinfunction "P$2_J2") (pintype "bidirectional"))
    )
    (net (code "136") (name "Net-(B01R-P$2)") (class "Default")
      (node (ref "B01") (pin "K2") (pinfunction "P$2_K2") (pintype "bidirectional"))
      (node (ref "B02") (pin "K2") (pinfunction "P$2_K2") (pintype "bidirectional"))
      (node (ref "B03") (pin "K2") (pinfunction "P$2_K2") (pintype "bidirectional"))
      (node (ref "B04") (pin "K2") (pinfunction "P$2_K2") (pintype "bidirectional"))
      (node (ref "B05") (pin "K2") (pinfunction "P$2_K2") (pintype "bidirectional"))
      (node (ref "B06") (pin "K2") (pinfunction "P$2_K2") (pintype "bidirectional"))
      (node (ref "B07") (pin "K2") (pinfunction "P$2_K2") (pintype "bidirectional"))
      (node (ref "B08") (pin "K2") (pinfunction "P$2_K2") (pintype "bidirectional"))
      (node (ref "B09") (pin "K2") (pinfunction "P$2_K2") (pintype "bidirectional"))
      (node (ref "B10") (pin "K2") (pinfunction "P$2_K2") (pintype "bidirectional"))
      (node (ref "B11") (pin "K2") (pinfunction "P$2_K2") (pintype "bidirectional"))
      (node (ref "B12") (pin "K2") (pinfunction "P$2_K2") (pintype "bidirectional"))
      (node (ref "B13") (pin "K2") (pinfunction "P$2_K2") (pintype "bidirectional"))
      (node (ref "B14") (pin "K2") (pinfunction "P$2_K2") (pintype "bidirectional"))
    )
    (net (code "137") (name "Net-(B01T-P$2)") (class "Default")
      (node (ref "B01") (pin "L2") (pinfunction "P$2_L2") (pintype "bidirectional"))
      (node (ref "B02") (pin "L2") (pinfunction "P$2_L2") (pintype "bidirectional"))
      (node (ref "B03") (pin "L2") (pinfunction "P$2_L2") (pintype "bidirectional"))
      (node (ref "B04") (pin "L2") (pinfunction "P$2_L2") (pintype "bidirectional"))
      (node (ref "B05") (pin "L2") (pinfunction "P$2_L2") (pintype "bidirectional"))
      (node (ref "B06") (pin "L2") (pinfunction "P$2_L2") (pintype "bidirectional"))
      (node (ref "B07") (pin "L2") (pinfunction "P$2_L2") (pintype "bidirectional"))
      (node (ref "B08") (pin "L2") (pinfunction "P$2_L2") (pintype "bidirectional"))
      (node (ref "B09") (pin "L2") (pinfunction "P$2_L2") (pintype "bidirectional"))
      (node (ref "B10") (pin "L2") (pinfunction "P$2_L2") (pintype "bidirectional"))
      (node (ref "B11") (pin "L2") (pinfunction "P$2_L2") (pintype "bidirectional"))
      (node (ref "B12") (pin "L2") (pinfunction "P$2_L2") (pintype "bidirectional"))
      (node (ref "B13") (pin "L2") (pinfunction "P$2_L2") (pintype "bidirectional"))
      (node (ref "B14") (pin "L2") (pinfunction "P$2_L2") (pintype "bidirectional"))
    )
    (net (code "138") (name "Net-(B01V-P$2)") (class "Default")
      (node (ref "B01") (pin "M2") (pinfunction "P$2_M2") (pintype "bidirectional"))
      (node (ref "B02") (pin "M2") (pinfunction "P$2_M2") (pintype "bidirectional"))
      (node (ref "B03") (pin "M2") (pinfunction "P$2_M2") (pintype "bidirectional"))
      (node (ref "B04") (pin "M2") (pinfunction "P$2_M2") (pintype "bidirectional"))
      (node (ref "B05") (pin "M2") (pinfunction "P$2_M2") (pintype "bidirectional"))
      (node (ref "B06") (pin "M2") (pinfunction "P$2_M2") (pintype "bidirectional"))
      (node (ref "B07") (pin "M2") (pinfunction "P$2_M2") (pintype "bidirectional"))
      (node (ref "B08") (pin "M2") (pinfunction "P$2_M2") (pintype "bidirectional"))
      (node (ref "B09") (pin "M2") (pinfunction "P$2_M2") (pintype "bidirectional"))
      (node (ref "B10") (pin "M2") (pinfunction "P$2_M2") (pintype "bidirectional"))
      (node (ref "B11") (pin "M2") (pinfunction "P$2_M2") (pintype "bidirectional"))
      (node (ref "B12") (pin "M2") (pinfunction "P$2_M2") (pintype "bidirectional"))
      (node (ref "B13") (pin "M2") (pinfunction "P$2_M2") (pintype "bidirectional"))
      (node (ref "B14") (pin "M2") (pinfunction "P$2_M2") (pintype "bidirectional"))
    )
    (net (code "139") (name "Net-(B01Z-P$2)") (class "Default")
      (node (ref "B01") (pin "P2") (pinfunction "P$2_P2") (pintype "bidirectional"))
      (node (ref "B02") (pin "P2") (pinfunction "P$2_P2") (pintype "bidirectional"))
      (node (ref "B03") (pin "P2") (pinfunction "P$2_P2") (pintype "bidirectional"))
      (node (ref "B04") (pin "P2") (pinfunction "P$2_P2") (pintype "bidirectional"))
      (node (ref "B05") (pin "P2") (pinfunction "P$2_P2") (pintype "bidirectional"))
      (node (ref "B06") (pin "P2") (pinfunction "P$2_P2") (pintype "bidirectional"))
      (node (ref "B07") (pin "P2") (pinfunction "P$2_P2") (pintype "bidirectional"))
      (node (ref "B08") (pin "P2") (pinfunction "P$2_P2") (pintype "bidirectional"))
      (node (ref "B09") (pin "P2") (pinfunction "P$2_P2") (pintype "bidirectional"))
      (node (ref "B10") (pin "P2") (pinfunction "P$2_P2") (pintype "bidirectional"))
      (node (ref "B11") (pin "P2") (pinfunction "P$2_P2") (pintype "bidirectional"))
      (node (ref "B12") (pin "P2") (pinfunction "P$2_P2") (pintype "bidirectional"))
      (node (ref "B13") (pin "P2") (pinfunction "P$2_P2") (pintype "bidirectional"))
      (node (ref "B14") (pin "P2") (pinfunction "P$2_P2") (pintype "bidirectional"))
    )
    (net (code "140") (name "Net-(B15A-IN2)") (class "Default")
      (node (ref "B15") (pin "B1") (pinfunction "IN2_B1") (pintype "input"))
      (node (ref "B15") (pin "C1") (pinfunction "IN3_C1") (pintype "input"))
      (node (ref "B15") (pin "D1") (pinfunction "IN4_D1") (pintype "input"))
      (node (ref "B15") (pin "H1") (pinfunction "IN2_H1") (pintype "input"))
      (node (ref "B15") (pin "J1") (pinfunction "IN3_J1") (pintype "input"))
      (node (ref "B15") (pin "K1") (pinfunction "IN4_K1") (pintype "input"))
      (node (ref "B15") (pin "N1") (pinfunction "IN2_N1") (pintype "input"))
      (node (ref "B15") (pin "P1") (pinfunction "IN3_P1") (pintype "input"))
      (node (ref "B15") (pin "R1") (pinfunction "IN4_R1") (pintype "input"))
      (node (ref "B15") (pin "V1") (pinfunction "P$1_V1") (pintype "passive"))
    )
    (net (code "141") (name "Net-(B15D-IN2)") (class "Default")
      (node (ref "B15") (pin "E2") (pinfunction "IN2_E2") (pintype "input"))
      (node (ref "B15") (pin "F2") (pinfunction "IN3_F2") (pintype "input"))
      (node (ref "B15") (pin "H2") (pinfunction "IN4_H2") (pintype "input"))
      (node (ref "B15") (pin "L2") (pinfunction "IN2_L2") (pintype "input"))
      (node (ref "B15") (pin "M2") (pinfunction "IN3_M2") (pintype "input"))
      (node (ref "B15") (pin "N2") (pinfunction "IN4_N2") (pintype "input"))
      (node (ref "B15") (pin "S2") (pinfunction "IN2_S2") (pintype "input"))
      (node (ref "B15") (pin "T2") (pinfunction "IN3_T2") (pintype "input"))
      (node (ref "B15") (pin "U1") (pinfunction "P$1_U1") (pintype "passive"))
      (node (ref "B15") (pin "U2") (pinfunction "IN4_U2") (pintype "input"))
    )
    (net (code "142") (name "Net-(B16D-OUT)") (class "Default")
      (node (ref "B16") (pin "H2") (pinfunction "OUT_H2") (pintype "output"))
      (node (ref "C17") (pin "N2") (pinfunction "S_N2") (pintype "input"))
    )
    (net (code "143") (name "Net-(B16E-IN1)") (class "Default")
      (node (ref "B16") (pin "E1") (pinfunction "IN1_E1") (pintype "input"))
      (node (ref "D19") (pin "J2") (pinfunction "R1_J2") (pintype "bidirectional"))
    )
    (net (code "144") (name "Net-(B16E-IN2)") (class "Default")
      (node (ref "B16") (pin "F1") (pinfunction "IN2_F1") (pintype "input"))
      (node (ref "D19") (pin "F2") (pinfunction "R1_F2") (pintype "bidirectional"))
    )
    (net (code "145") (name "Net-(B16E-IN3)") (class "Default")
      (node (ref "B16") (pin "H1") (pinfunction "IN3_H1") (pintype "input"))
      (node (ref "D19") (pin "L2") (pinfunction "R1_L2") (pintype "bidirectional"))
    )
    (net (code "146") (name "Net-(B16E-OUT)") (class "Default")
      (node (ref "B16") (pin "J1") (pinfunction "OUT_J1") (pintype "output"))
      (node (ref "B17") (pin "U2") (pinfunction "IN2_U2") (pintype "input"))
    )
    (net (code "147") (name "Net-(B16F-OUT)") (class "Default")
      (node (ref "B16") (pin "M2") (pinfunction "OUT_M2") (pintype "output"))
      (node (ref "C17") (pin "U2") (pinfunction "S_U2") (pintype "input"))
    )
    (net (code "148") (name "Net-(B16I-OUT)") (class "Default")
      (node (ref "B16") (pin "U1") (pinfunction "OUT_U1") (pintype "output"))
      (node (ref "B18") (pin "R2") (pinfunction "A_R2") (pintype "input"))
    )
    (net (code "149") (name "Net-(B16J-OUT)") (class "Default")
      (node (ref "B16") (pin "V1") (pinfunction "OUT_V1") (pintype "output"))
      (node (ref "C20") (pin "H2") (pinfunction "H2_H2") (pintype "input"))
    )
    (net (code "150") (name "Net-(B17A-OUT)") (class "Default")
      (node (ref "B17") (pin "C1") (pinfunction "OUT_C1") (pintype "output"))
      (node (ref "D19") (pin "A1") (pinfunction "L1_A1") (pintype "bidirectional"))
    )
    (net (code "151") (name "Net-(B17B-OUT)") (class "Default")
      (node (ref "B17") (pin "F1") (pinfunction "OUT_F1") (pintype "output"))
      (node (ref "D18") (pin "H2") (pinfunction "IN_H2") (pintype "input"))
    )
    (net (code "152") (name "Net-(B17F-OUT)") (class "Default")
      (node (ref "B17") (pin "K1") (pinfunction "OUT_K1") (pintype "output"))
      (node (ref "D15") (pin "B1") (pinfunction "C_B1") (pintype "input"))
      (node (ref "D15") (pin "D2") (pinfunction "C_D2") (pintype "input"))
      (node (ref "D15") (pin "H1") (pinfunction "C_H1") (pintype "input"))
      (node (ref "D15") (pin "L2") (pinfunction "C_L2") (pintype "input"))
    )
    (net (code "153") (name "Net-(B17G-OUT)") (class "Default")
      (node (ref "B17") (pin "K2") (pinfunction "OUT_K2") (pintype "output"))
      (node (ref "D15") (pin "N1") (pinfunction "C_N1") (pintype "input"))
      (node (ref "D15") (pin "S2") (pinfunction "C_S2") (pintype "input"))
      (node (ref "D16") (pin "B1") (pinfunction "C_B1") (pintype "input"))
      (node (ref "D16") (pin "D2") (pinfunction "C_D2") (pintype "input"))
    )
    (net (code "154") (name "Net-(B17H-OUT)") (class "Default")
      (node (ref "B17") (pin "N1") (pinfunction "OUT_N1") (pintype "output"))
      (node (ref "D16") (pin "H1") (pinfunction "C_H1") (pintype "input"))
      (node (ref "D16") (pin "L2") (pinfunction "C_L2") (pintype "input"))
      (node (ref "D16") (pin "N1") (pinfunction "C_N1") (pintype "input"))
      (node (ref "D16") (pin "S2") (pinfunction "C_S2") (pintype "input"))
    )
    (net (code "155") (name "Net-(B17N-IN1)") (class "Default")
      (node (ref "B17") (pin "T2") (pinfunction "IN1_T2") (pintype "input"))
      (node (ref "D19") (pin "D2") (pinfunction "R1_D2") (pintype "bidirectional"))
    )
    (net (code "156") (name "Net-(B19A-C)") (class "Default")
      (node (ref "B19") (pin "C1") (pinfunction "C_C1") (pintype "input"))
      (node (ref "B19") (pin "F2") (pinfunction "C_F2") (pintype "input"))
      (node (ref "B19") (pin "J1") (pinfunction "C_J1") (pintype "input"))
      (node (ref "B19") (pin "M2") (pinfunction "C_M2") (pintype "input"))
      (node (ref "B19") (pin "P1") (pinfunction "C_P1") (pintype "input"))
      (node (ref "B19") (pin "T2") (pinfunction "C_T2") (pintype "input"))
      (node (ref "C16") (pin "J2") (pinfunction "OUT_J2") (pintype "output"))
    )
    (net (code "157") (name "Net-(B20A-A)") (class "Default")
      (node (ref "B20") (pin "A1") (pinfunction "A_A1") (pintype "input"))
      (node (ref "D15") (pin "F1") (pinfunction "0_F1") (pintype "output"))
    )
    (net (code "158") (name "Net-(B20A-B)") (class "Default")
      (node (ref "B20") (pin "B1") (pinfunction "B_B1") (pintype "input"))
      (node (ref "D15") (pin "J2") (pinfunction "0_J2") (pintype "output"))
    )
    (net (code "159") (name "Net-(B20A-C)") (class "Default")
      (node (ref "B20") (pin "C1") (pinfunction "C_C1") (pintype "input"))
      (node (ref "B20") (pin "F2") (pinfunction "C_F2") (pintype "input"))
      (node (ref "B20") (pin "J1") (pinfunction "C_J1") (pintype "input"))
      (node (ref "B20") (pin "M2") (pinfunction "C_M2") (pintype "input"))
      (node (ref "B20") (pin "P1") (pinfunction "C_P1") (pintype "input"))
      (node (ref "B20") (pin "T2") (pinfunction "C_T2") (pintype "input"))
      (node (ref "C16") (pin "P2") (pinfunction "OUT_P2") (pintype "output"))
    )
    (net (code "160") (name "Net-(B20F-A)") (class "Default")
      (node (ref "B20") (pin "D2") (pinfunction "A_D2") (pintype "input"))
      (node (ref "D16") (pin "F1") (pinfunction "0_F1") (pintype "output"))
    )
    (net (code "161") (name "Net-(B20F-B)") (class "Default")
      (node (ref "B20") (pin "E2") (pinfunction "B_E2") (pintype "input"))
      (node (ref "D16") (pin "J2") (pinfunction "0_J2") (pintype "output"))
    )
    (net (code "162") (name "Net-(B20G-A)") (class "Default")
      (node (ref "B20") (pin "F1") (pinfunction "A_F1") (pintype "input"))
      (node (ref "D15") (pin "M1") (pinfunction "0_M1") (pintype "output"))
    )
    (net (code "163") (name "Net-(B20G-B)") (class "Default")
      (node (ref "B20") (pin "H1") (pinfunction "B_H1") (pintype "input"))
      (node (ref "D15") (pin "R2") (pinfunction "0_R2") (pintype "output"))
    )
    (net (code "164") (name "Net-(B20H-A)") (class "Default")
      (node (ref "B20") (pin "K2") (pinfunction "A_K2") (pintype "input"))
      (node (ref "D16") (pin "M1") (pinfunction "0_M1") (pintype "output"))
    )
    (net (code "165") (name "Net-(B20H-B)") (class "Default")
      (node (ref "B20") (pin "L2") (pinfunction "B_L2") (pintype "input"))
      (node (ref "D16") (pin "R2") (pinfunction "0_R2") (pintype "output"))
    )
    (net (code "166") (name "Net-(B20I-A)") (class "Default")
      (node (ref "B20") (pin "M1") (pinfunction "A_M1") (pintype "input"))
      (node (ref "D15") (pin "U1") (pinfunction "0_U1") (pintype "output"))
    )
    (net (code "167") (name "Net-(B20I-B)") (class "Default")
      (node (ref "B20") (pin "N1") (pinfunction "B_N1") (pintype "input"))
      (node (ref "D15") (pin "V1") (pinfunction "0_V1") (pintype "output"))
    )
    (net (code "168") (name "Net-(B20J-A)") (class "Default")
      (node (ref "B20") (pin "R2") (pinfunction "A_R2") (pintype "input"))
      (node (ref "D16") (pin "U1") (pinfunction "0_U1") (pintype "output"))
    )
    (net (code "169") (name "Net-(B20J-B)") (class "Default")
      (node (ref "B20") (pin "S2") (pinfunction "B_S2") (pintype "input"))
      (node (ref "D16") (pin "V1") (pinfunction "0_V1") (pintype "output"))
    )
    (net (code "170") (name "Net-(C01A-P$2)") (class "Default")
      (node (ref "C01") (pin "A1") (pinfunction "P$2_A1") (pintype "bidirectional"))
      (node (ref "C02") (pin "A1") (pinfunction "P$2_A1") (pintype "bidirectional"))
      (node (ref "C03") (pin "A1") (pinfunction "P$2_A1") (pintype "bidirectional"))
      (node (ref "C04") (pin "A1") (pinfunction "P$2_A1") (pintype "bidirectional"))
      (node (ref "C05") (pin "A1") (pinfunction "P$2_A1") (pintype "bidirectional"))
      (node (ref "C06") (pin "A1") (pinfunction "P$2_A1") (pintype "bidirectional"))
      (node (ref "C07") (pin "A1") (pinfunction "P$2_A1") (pintype "bidirectional"))
      (node (ref "C08") (pin "A1") (pinfunction "P$2_A1") (pintype "bidirectional"))
      (node (ref "C09") (pin "A1") (pinfunction "P$2_A1") (pintype "bidirectional"))
      (node (ref "C10") (pin "A1") (pinfunction "P$2_A1") (pintype "bidirectional"))
      (node (ref "C11") (pin "A1") (pinfunction "P$2_A1") (pintype "bidirectional"))
      (node (ref "C12") (pin "A1") (pinfunction "P$2_A1") (pintype "bidirectional"))
      (node (ref "C13") (pin "A1") (pinfunction "P$2_A1") (pintype "bidirectional"))
      (node (ref "C14") (pin "A1") (pinfunction "P$2_A1") (pintype "bidirectional"))
    )
    (net (code "171") (name "Net-(C01AA-P$2)") (class "Default")
      (node (ref "C01") (pin "R1") (pinfunction "P$2_R1") (pintype "bidirectional"))
      (node (ref "C02") (pin "R1") (pinfunction "P$2_R1") (pintype "bidirectional"))
      (node (ref "C03") (pin "R1") (pinfunction "P$2_R1") (pintype "bidirectional"))
      (node (ref "C04") (pin "R1") (pinfunction "P$2_R1") (pintype "bidirectional"))
      (node (ref "C05") (pin "R1") (pinfunction "P$2_R1") (pintype "bidirectional"))
      (node (ref "C06") (pin "R1") (pinfunction "P$2_R1") (pintype "bidirectional"))
      (node (ref "C07") (pin "R1") (pinfunction "P$2_R1") (pintype "bidirectional"))
      (node (ref "C08") (pin "R1") (pinfunction "P$2_R1") (pintype "bidirectional"))
      (node (ref "C09") (pin "R1") (pinfunction "P$2_R1") (pintype "bidirectional"))
      (node (ref "C10") (pin "R1") (pinfunction "P$2_R1") (pintype "bidirectional"))
      (node (ref "C11") (pin "R1") (pinfunction "P$2_R1") (pintype "bidirectional"))
      (node (ref "C12") (pin "R1") (pinfunction "P$2_R1") (pintype "bidirectional"))
      (node (ref "C13") (pin "R1") (pinfunction "P$2_R1") (pintype "bidirectional"))
      (node (ref "C14") (pin "R1") (pinfunction "P$2_R1") (pintype "bidirectional"))
    )
    (net (code "172") (name "Net-(C01AB-P$2)") (class "Default")
      (node (ref "C01") (pin "R2") (pinfunction "P$2_R2") (pintype "bidirectional"))
      (node (ref "C02") (pin "R2") (pinfunction "P$2_R2") (pintype "bidirectional"))
      (node (ref "C03") (pin "R2") (pinfunction "P$2_R2") (pintype "bidirectional"))
      (node (ref "C04") (pin "R2") (pinfunction "P$2_R2") (pintype "bidirectional"))
      (node (ref "C05") (pin "R2") (pinfunction "P$2_R2") (pintype "bidirectional"))
      (node (ref "C06") (pin "R2") (pinfunction "P$2_R2") (pintype "bidirectional"))
      (node (ref "C07") (pin "R2") (pinfunction "P$2_R2") (pintype "bidirectional"))
      (node (ref "C08") (pin "R2") (pinfunction "P$2_R2") (pintype "bidirectional"))
      (node (ref "C09") (pin "R2") (pinfunction "P$2_R2") (pintype "bidirectional"))
      (node (ref "C10") (pin "R2") (pinfunction "P$2_R2") (pintype "bidirectional"))
      (node (ref "C11") (pin "R2") (pinfunction "P$2_R2") (pintype "bidirectional"))
      (node (ref "C12") (pin "R2") (pinfunction "P$2_R2") (pintype "bidirectional"))
      (node (ref "C13") (pin "R2") (pinfunction "P$2_R2") (pintype "bidirectional"))
      (node (ref "C14") (pin "R2") (pinfunction "P$2_R2") (pintype "bidirectional"))
    )
    (net (code "173") (name "Net-(C01AC-P$2)") (class "Default")
      (node (ref "C01") (pin "S1") (pinfunction "P$2_S1") (pintype "bidirectional"))
      (node (ref "C02") (pin "S1") (pinfunction "P$2_S1") (pintype "bidirectional"))
      (node (ref "C03") (pin "S1") (pinfunction "P$2_S1") (pintype "bidirectional"))
      (node (ref "C04") (pin "S1") (pinfunction "P$2_S1") (pintype "bidirectional"))
      (node (ref "C05") (pin "S1") (pinfunction "P$2_S1") (pintype "bidirectional"))
      (node (ref "C06") (pin "S1") (pinfunction "P$2_S1") (pintype "bidirectional"))
      (node (ref "C07") (pin "S1") (pinfunction "P$2_S1") (pintype "bidirectional"))
      (node (ref "C08") (pin "S1") (pinfunction "P$2_S1") (pintype "bidirectional"))
      (node (ref "C09") (pin "S1") (pinfunction "P$2_S1") (pintype "bidirectional"))
      (node (ref "C10") (pin "S1") (pinfunction "P$2_S1") (pintype "bidirectional"))
      (node (ref "C11") (pin "S1") (pinfunction "P$2_S1") (pintype "bidirectional"))
      (node (ref "C12") (pin "S1") (pinfunction "P$2_S1") (pintype "bidirectional"))
      (node (ref "C13") (pin "S1") (pinfunction "P$2_S1") (pintype "bidirectional"))
      (node (ref "C14") (pin "S1") (pinfunction "P$2_S1") (pintype "bidirectional"))
    )
    (net (code "174") (name "Net-(C01AD-P$2)") (class "Default")
      (node (ref "C01") (pin "S2") (pinfunction "P$2_S2") (pintype "bidirectional"))
      (node (ref "C02") (pin "S2") (pinfunction "P$2_S2") (pintype "bidirectional"))
      (node (ref "C03") (pin "S2") (pinfunction "P$2_S2") (pintype "bidirectional"))
      (node (ref "C04") (pin "S2") (pinfunction "P$2_S2") (pintype "bidirectional"))
      (node (ref "C05") (pin "S2") (pinfunction "P$2_S2") (pintype "bidirectional"))
      (node (ref "C06") (pin "S2") (pinfunction "P$2_S2") (pintype "bidirectional"))
      (node (ref "C07") (pin "S2") (pinfunction "P$2_S2") (pintype "bidirectional"))
      (node (ref "C08") (pin "S2") (pinfunction "P$2_S2") (pintype "bidirectional"))
      (node (ref "C09") (pin "S2") (pinfunction "P$2_S2") (pintype "bidirectional"))
      (node (ref "C10") (pin "S2") (pinfunction "P$2_S2") (pintype "bidirectional"))
      (node (ref "C11") (pin "S2") (pinfunction "P$2_S2") (pintype "bidirectional"))
      (node (ref "C12") (pin "S2") (pinfunction "P$2_S2") (pintype "bidirectional"))
      (node (ref "C13") (pin "S2") (pinfunction "P$2_S2") (pintype "bidirectional"))
      (node (ref "C14") (pin "S2") (pinfunction "P$2_S2") (pintype "bidirectional"))
    )
    (net (code "175") (name "Net-(C01AG-P$2)") (class "Default")
      (node (ref "C01") (pin "U1") (pinfunction "P$2_U1") (pintype "bidirectional"))
      (node (ref "C02") (pin "U1") (pinfunction "P$2_U1") (pintype "bidirectional"))
      (node (ref "C03") (pin "U1") (pinfunction "P$2_U1") (pintype "bidirectional"))
      (node (ref "C04") (pin "U1") (pinfunction "P$2_U1") (pintype "bidirectional"))
      (node (ref "C05") (pin "U1") (pinfunction "P$2_U1") (pintype "bidirectional"))
      (node (ref "C06") (pin "U1") (pinfunction "P$2_U1") (pintype "bidirectional"))
      (node (ref "C07") (pin "U1") (pinfunction "P$2_U1") (pintype "bidirectional"))
      (node (ref "C08") (pin "U1") (pinfunction "P$2_U1") (pintype "bidirectional"))
      (node (ref "C09") (pin "U1") (pinfunction "P$2_U1") (pintype "bidirectional"))
      (node (ref "C10") (pin "U1") (pinfunction "P$2_U1") (pintype "bidirectional"))
      (node (ref "C11") (pin "U1") (pinfunction "P$2_U1") (pintype "bidirectional"))
      (node (ref "C12") (pin "U1") (pinfunction "P$2_U1") (pintype "bidirectional"))
      (node (ref "C13") (pin "U1") (pinfunction "P$2_U1") (pintype "bidirectional"))
      (node (ref "C14") (pin "U1") (pinfunction "P$2_U1") (pintype "bidirectional"))
    )
    (net (code "176") (name "Net-(C01AH-P$2)") (class "Default")
      (node (ref "C01") (pin "U2") (pinfunction "P$2_U2") (pintype "bidirectional"))
      (node (ref "C02") (pin "U2") (pinfunction "P$2_U2") (pintype "bidirectional"))
      (node (ref "C03") (pin "U2") (pinfunction "P$2_U2") (pintype "bidirectional"))
      (node (ref "C04") (pin "U2") (pinfunction "P$2_U2") (pintype "bidirectional"))
      (node (ref "C05") (pin "U2") (pinfunction "P$2_U2") (pintype "bidirectional"))
      (node (ref "C06") (pin "U2") (pinfunction "P$2_U2") (pintype "bidirectional"))
      (node (ref "C07") (pin "U2") (pinfunction "P$2_U2") (pintype "bidirectional"))
      (node (ref "C08") (pin "U2") (pinfunction "P$2_U2") (pintype "bidirectional"))
      (node (ref "C09") (pin "U2") (pinfunction "P$2_U2") (pintype "bidirectional"))
      (node (ref "C10") (pin "U2") (pinfunction "P$2_U2") (pintype "bidirectional"))
      (node (ref "C11") (pin "U2") (pinfunction "P$2_U2") (pintype "bidirectional"))
      (node (ref "C12") (pin "U2") (pinfunction "P$2_U2") (pintype "bidirectional"))
      (node (ref "C13") (pin "U2") (pinfunction "P$2_U2") (pintype "bidirectional"))
      (node (ref "C14") (pin "U2") (pinfunction "P$2_U2") (pintype "bidirectional"))
    )
    (net (code "177") (name "Net-(C01AI-P$2)") (class "Default")
      (node (ref "C01") (pin "V1") (pinfunction "P$2_V1") (pintype "bidirectional"))
      (node (ref "C02") (pin "V1") (pinfunction "P$2_V1") (pintype "bidirectional"))
      (node (ref "C03") (pin "V1") (pinfunction "P$2_V1") (pintype "bidirectional"))
      (node (ref "C04") (pin "V1") (pinfunction "P$2_V1") (pintype "bidirectional"))
      (node (ref "C05") (pin "V1") (pinfunction "P$2_V1") (pintype "bidirectional"))
      (node (ref "C06") (pin "V1") (pinfunction "P$2_V1") (pintype "bidirectional"))
      (node (ref "C07") (pin "V1") (pinfunction "P$2_V1") (pintype "bidirectional"))
      (node (ref "C08") (pin "V1") (pinfunction "P$2_V1") (pintype "bidirectional"))
      (node (ref "C09") (pin "V1") (pinfunction "P$2_V1") (pintype "bidirectional"))
      (node (ref "C10") (pin "V1") (pinfunction "P$2_V1") (pintype "bidirectional"))
      (node (ref "C11") (pin "V1") (pinfunction "P$2_V1") (pintype "bidirectional"))
      (node (ref "C12") (pin "V1") (pinfunction "P$2_V1") (pintype "bidirectional"))
      (node (ref "C13") (pin "V1") (pinfunction "P$2_V1") (pintype "bidirectional"))
      (node (ref "C14") (pin "V1") (pinfunction "P$2_V1") (pintype "bidirectional"))
    )
    (net (code "178") (name "Net-(C01AJ-P$2)") (class "Default")
      (node (ref "C01") (pin "V2") (pinfunction "P$2_V2") (pintype "bidirectional"))
      (node (ref "C02") (pin "V2") (pinfunction "P$2_V2") (pintype "bidirectional"))
      (node (ref "C03") (pin "V2") (pinfunction "P$2_V2") (pintype "bidirectional"))
      (node (ref "C04") (pin "V2") (pinfunction "P$2_V2") (pintype "bidirectional"))
      (node (ref "C05") (pin "V2") (pinfunction "P$2_V2") (pintype "bidirectional"))
      (node (ref "C06") (pin "V2") (pinfunction "P$2_V2") (pintype "bidirectional"))
      (node (ref "C07") (pin "V2") (pinfunction "P$2_V2") (pintype "bidirectional"))
      (node (ref "C08") (pin "V2") (pinfunction "P$2_V2") (pintype "bidirectional"))
      (node (ref "C09") (pin "V2") (pinfunction "P$2_V2") (pintype "bidirectional"))
      (node (ref "C10") (pin "V2") (pinfunction "P$2_V2") (pintype "bidirectional"))
      (node (ref "C11") (pin "V2") (pinfunction "P$2_V2") (pintype "bidirectional"))
      (node (ref "C12") (pin "V2") (pinfunction "P$2_V2") (pintype "bidirectional"))
      (node (ref "C13") (pin "V2") (pinfunction "P$2_V2") (pintype "bidirectional"))
      (node (ref "C14") (pin "V2") (pinfunction "P$2_V2") (pintype "bidirectional"))
    )
    (net (code "179") (name "Net-(C01C-P$2)") (class "Default")
      (node (ref "C01") (pin "B1") (pinfunction "P$2_B1") (pintype "bidirectional"))
      (node (ref "C02") (pin "B1") (pinfunction "P$2_B1") (pintype "bidirectional"))
      (node (ref "C03") (pin "B1") (pinfunction "P$2_B1") (pintype "bidirectional"))
      (node (ref "C04") (pin "B1") (pinfunction "P$2_B1") (pintype "bidirectional"))
      (node (ref "C05") (pin "B1") (pinfunction "P$2_B1") (pintype "bidirectional"))
      (node (ref "C06") (pin "B1") (pinfunction "P$2_B1") (pintype "bidirectional"))
      (node (ref "C07") (pin "B1") (pinfunction "P$2_B1") (pintype "bidirectional"))
      (node (ref "C08") (pin "B1") (pinfunction "P$2_B1") (pintype "bidirectional"))
      (node (ref "C09") (pin "B1") (pinfunction "P$2_B1") (pintype "bidirectional"))
      (node (ref "C10") (pin "B1") (pinfunction "P$2_B1") (pintype "bidirectional"))
      (node (ref "C11") (pin "B1") (pinfunction "P$2_B1") (pintype "bidirectional"))
      (node (ref "C12") (pin "B1") (pinfunction "P$2_B1") (pintype "bidirectional"))
      (node (ref "C13") (pin "B1") (pinfunction "P$2_B1") (pintype "bidirectional"))
      (node (ref "C14") (pin "B1") (pinfunction "P$2_B1") (pintype "bidirectional"))
    )
    (net (code "180") (name "Net-(C01G-P$2)") (class "Default")
      (node (ref "C01") (pin "D1") (pinfunction "P$2_D1") (pintype "bidirectional"))
      (node (ref "C02") (pin "D1") (pinfunction "P$2_D1") (pintype "bidirectional"))
      (node (ref "C03") (pin "D1") (pinfunction "P$2_D1") (pintype "bidirectional"))
      (node (ref "C04") (pin "D1") (pinfunction "P$2_D1") (pintype "bidirectional"))
      (node (ref "C05") (pin "D1") (pinfunction "P$2_D1") (pintype "bidirectional"))
      (node (ref "C06") (pin "D1") (pinfunction "P$2_D1") (pintype "bidirectional"))
      (node (ref "C07") (pin "D1") (pinfunction "P$2_D1") (pintype "bidirectional"))
      (node (ref "C08") (pin "D1") (pinfunction "P$2_D1") (pintype "bidirectional"))
      (node (ref "C09") (pin "D1") (pinfunction "P$2_D1") (pintype "bidirectional"))
      (node (ref "C10") (pin "D1") (pinfunction "P$2_D1") (pintype "bidirectional"))
      (node (ref "C11") (pin "D1") (pinfunction "P$2_D1") (pintype "bidirectional"))
      (node (ref "C12") (pin "D1") (pinfunction "P$2_D1") (pintype "bidirectional"))
      (node (ref "C13") (pin "D1") (pinfunction "P$2_D1") (pintype "bidirectional"))
      (node (ref "C14") (pin "D1") (pinfunction "P$2_D1") (pintype "bidirectional"))
    )
    (net (code "181") (name "Net-(C01H-P$2)") (class "Default")
      (node (ref "C01") (pin "D2") (pinfunction "P$2_D2") (pintype "bidirectional"))
      (node (ref "C02") (pin "D2") (pinfunction "P$2_D2") (pintype "bidirectional"))
      (node (ref "C03") (pin "D2") (pinfunction "P$2_D2") (pintype "bidirectional"))
      (node (ref "C04") (pin "D2") (pinfunction "P$2_D2") (pintype "bidirectional"))
      (node (ref "C05") (pin "D2") (pinfunction "P$2_D2") (pintype "bidirectional"))
      (node (ref "C06") (pin "D2") (pinfunction "P$2_D2") (pintype "bidirectional"))
      (node (ref "C07") (pin "D2") (pinfunction "P$2_D2") (pintype "bidirectional"))
      (node (ref "C08") (pin "D2") (pinfunction "P$2_D2") (pintype "bidirectional"))
      (node (ref "C09") (pin "D2") (pinfunction "P$2_D2") (pintype "bidirectional"))
      (node (ref "C10") (pin "D2") (pinfunction "P$2_D2") (pintype "bidirectional"))
      (node (ref "C11") (pin "D2") (pinfunction "P$2_D2") (pintype "bidirectional"))
      (node (ref "C12") (pin "D2") (pinfunction "P$2_D2") (pintype "bidirectional"))
      (node (ref "C13") (pin "D2") (pinfunction "P$2_D2") (pintype "bidirectional"))
      (node (ref "C14") (pin "D2") (pinfunction "P$2_D2") (pintype "bidirectional"))
    )
    (net (code "182") (name "Net-(C01I-P$2)") (class "Default")
      (node (ref "C01") (pin "E1") (pinfunction "P$2_E1") (pintype "bidirectional"))
      (node (ref "C02") (pin "E1") (pinfunction "P$2_E1") (pintype "bidirectional"))
      (node (ref "C03") (pin "E1") (pinfunction "P$2_E1") (pintype "bidirectional"))
      (node (ref "C04") (pin "E1") (pinfunction "P$2_E1") (pintype "bidirectional"))
      (node (ref "C05") (pin "E1") (pinfunction "P$2_E1") (pintype "bidirectional"))
      (node (ref "C06") (pin "E1") (pinfunction "P$2_E1") (pintype "bidirectional"))
      (node (ref "C07") (pin "E1") (pinfunction "P$2_E1") (pintype "bidirectional"))
      (node (ref "C08") (pin "E1") (pinfunction "P$2_E1") (pintype "bidirectional"))
      (node (ref "C09") (pin "E1") (pinfunction "P$2_E1") (pintype "bidirectional"))
      (node (ref "C10") (pin "E1") (pinfunction "P$2_E1") (pintype "bidirectional"))
      (node (ref "C11") (pin "E1") (pinfunction "P$2_E1") (pintype "bidirectional"))
      (node (ref "C12") (pin "E1") (pinfunction "P$2_E1") (pintype "bidirectional"))
      (node (ref "C13") (pin "E1") (pinfunction "P$2_E1") (pintype "bidirectional"))
      (node (ref "C14") (pin "E1") (pinfunction "P$2_E1") (pintype "bidirectional"))
    )
    (net (code "183") (name "Net-(C01J-P$2)") (class "Default")
      (node (ref "C01") (pin "E2") (pinfunction "P$2_E2") (pintype "bidirectional"))
      (node (ref "C02") (pin "E2") (pinfunction "P$2_E2") (pintype "bidirectional"))
      (node (ref "C03") (pin "E2") (pinfunction "P$2_E2") (pintype "bidirectional"))
      (node (ref "C04") (pin "E2") (pinfunction "P$2_E2") (pintype "bidirectional"))
      (node (ref "C05") (pin "E2") (pinfunction "P$2_E2") (pintype "bidirectional"))
      (node (ref "C06") (pin "E2") (pinfunction "P$2_E2") (pintype "bidirectional"))
      (node (ref "C07") (pin "E2") (pinfunction "P$2_E2") (pintype "bidirectional"))
      (node (ref "C08") (pin "E2") (pinfunction "P$2_E2") (pintype "bidirectional"))
      (node (ref "C09") (pin "E2") (pinfunction "P$2_E2") (pintype "bidirectional"))
      (node (ref "C10") (pin "E2") (pinfunction "P$2_E2") (pintype "bidirectional"))
      (node (ref "C11") (pin "E2") (pinfunction "P$2_E2") (pintype "bidirectional"))
      (node (ref "C12") (pin "E2") (pinfunction "P$2_E2") (pintype "bidirectional"))
      (node (ref "C13") (pin "E2") (pinfunction "P$2_E2") (pintype "bidirectional"))
      (node (ref "C14") (pin "E2") (pinfunction "P$2_E2") (pintype "bidirectional"))
    )
    (net (code "184") (name "Net-(C01M-P$2)") (class "Default")
      (node (ref "C01") (pin "H1") (pinfunction "P$2_H1") (pintype "bidirectional"))
      (node (ref "C02") (pin "H1") (pinfunction "P$2_H1") (pintype "bidirectional"))
      (node (ref "C03") (pin "H1") (pinfunction "P$2_H1") (pintype "bidirectional"))
      (node (ref "C04") (pin "H1") (pinfunction "P$2_H1") (pintype "bidirectional"))
      (node (ref "C05") (pin "H1") (pinfunction "P$2_H1") (pintype "bidirectional"))
      (node (ref "C06") (pin "H1") (pinfunction "P$2_H1") (pintype "bidirectional"))
      (node (ref "C07") (pin "H1") (pinfunction "P$2_H1") (pintype "bidirectional"))
      (node (ref "C08") (pin "H1") (pinfunction "P$2_H1") (pintype "bidirectional"))
      (node (ref "C09") (pin "H1") (pinfunction "P$2_H1") (pintype "bidirectional"))
      (node (ref "C10") (pin "H1") (pinfunction "P$2_H1") (pintype "bidirectional"))
      (node (ref "C11") (pin "H1") (pinfunction "P$2_H1") (pintype "bidirectional"))
      (node (ref "C12") (pin "H1") (pinfunction "P$2_H1") (pintype "bidirectional"))
      (node (ref "C13") (pin "H1") (pinfunction "P$2_H1") (pintype "bidirectional"))
      (node (ref "C14") (pin "H1") (pinfunction "P$2_H1") (pintype "bidirectional"))
    )
    (net (code "185") (name "Net-(C01N-P$2)") (class "Default")
      (node (ref "C01") (pin "H2") (pinfunction "P$2_H2") (pintype "bidirectional"))
      (node (ref "C02") (pin "H2") (pinfunction "P$2_H2") (pintype "bidirectional"))
      (node (ref "C03") (pin "H2") (pinfunction "P$2_H2") (pintype "bidirectional"))
      (node (ref "C04") (pin "H2") (pinfunction "P$2_H2") (pintype "bidirectional"))
      (node (ref "C05") (pin "H2") (pinfunction "P$2_H2") (pintype "bidirectional"))
      (node (ref "C06") (pin "H2") (pinfunction "P$2_H2") (pintype "bidirectional"))
      (node (ref "C07") (pin "H2") (pinfunction "P$2_H2") (pintype "bidirectional"))
      (node (ref "C08") (pin "H2") (pinfunction "P$2_H2") (pintype "bidirectional"))
      (node (ref "C09") (pin "H2") (pinfunction "P$2_H2") (pintype "bidirectional"))
      (node (ref "C10") (pin "H2") (pinfunction "P$2_H2") (pintype "bidirectional"))
      (node (ref "C11") (pin "H2") (pinfunction "P$2_H2") (pintype "bidirectional"))
      (node (ref "C12") (pin "H2") (pinfunction "P$2_H2") (pintype "bidirectional"))
      (node (ref "C13") (pin "H2") (pinfunction "P$2_H2") (pintype "bidirectional"))
      (node (ref "C14") (pin "H2") (pinfunction "P$2_H2") (pintype "bidirectional"))
    )
    (net (code "186") (name "Net-(C01O-P$2)") (class "Default")
      (node (ref "C01") (pin "J1") (pinfunction "P$2_J1") (pintype "bidirectional"))
      (node (ref "C02") (pin "J1") (pinfunction "P$2_J1") (pintype "bidirectional"))
      (node (ref "C03") (pin "J1") (pinfunction "P$2_J1") (pintype "bidirectional"))
      (node (ref "C04") (pin "J1") (pinfunction "P$2_J1") (pintype "bidirectional"))
      (node (ref "C05") (pin "J1") (pinfunction "P$2_J1") (pintype "bidirectional"))
      (node (ref "C06") (pin "J1") (pinfunction "P$2_J1") (pintype "bidirectional"))
      (node (ref "C07") (pin "J1") (pinfunction "P$2_J1") (pintype "bidirectional"))
      (node (ref "C08") (pin "J1") (pinfunction "P$2_J1") (pintype "bidirectional"))
      (node (ref "C09") (pin "J1") (pinfunction "P$2_J1") (pintype "bidirectional"))
      (node (ref "C10") (pin "J1") (pinfunction "P$2_J1") (pintype "bidirectional"))
      (node (ref "C11") (pin "J1") (pinfunction "P$2_J1") (pintype "bidirectional"))
      (node (ref "C12") (pin "J1") (pinfunction "P$2_J1") (pintype "bidirectional"))
      (node (ref "C13") (pin "J1") (pinfunction "P$2_J1") (pintype "bidirectional"))
      (node (ref "C14") (pin "J1") (pinfunction "P$2_J1") (pintype "bidirectional"))
    )
    (net (code "187") (name "Net-(C01P-P$2)") (class "Default")
      (node (ref "C01") (pin "J2") (pinfunction "P$2_J2") (pintype "bidirectional"))
      (node (ref "C02") (pin "J2") (pinfunction "P$2_J2") (pintype "bidirectional"))
      (node (ref "C03") (pin "J2") (pinfunction "P$2_J2") (pintype "bidirectional"))
      (node (ref "C04") (pin "J2") (pinfunction "P$2_J2") (pintype "bidirectional"))
      (node (ref "C05") (pin "J2") (pinfunction "P$2_J2") (pintype "bidirectional"))
      (node (ref "C06") (pin "J2") (pinfunction "P$2_J2") (pintype "bidirectional"))
      (node (ref "C07") (pin "J2") (pinfunction "P$2_J2") (pintype "bidirectional"))
      (node (ref "C08") (pin "J2") (pinfunction "P$2_J2") (pintype "bidirectional"))
      (node (ref "C09") (pin "J2") (pinfunction "P$2_J2") (pintype "bidirectional"))
      (node (ref "C10") (pin "J2") (pinfunction "P$2_J2") (pintype "bidirectional"))
      (node (ref "C11") (pin "J2") (pinfunction "P$2_J2") (pintype "bidirectional"))
      (node (ref "C12") (pin "J2") (pinfunction "P$2_J2") (pintype "bidirectional"))
      (node (ref "C13") (pin "J2") (pinfunction "P$2_J2") (pintype "bidirectional"))
      (node (ref "C14") (pin "J2") (pinfunction "P$2_J2") (pintype "bidirectional"))
    )
    (net (code "188") (name "Net-(C01Q-P$2)") (class "Default")
      (node (ref "C01") (pin "K1") (pinfunction "P$2_K1") (pintype "bidirectional"))
      (node (ref "C02") (pin "K1") (pinfunction "P$2_K1") (pintype "bidirectional"))
      (node (ref "C03") (pin "K1") (pinfunction "P$2_K1") (pintype "bidirectional"))
      (node (ref "C04") (pin "K1") (pinfunction "P$2_K1") (pintype "bidirectional"))
      (node (ref "C05") (pin "K1") (pinfunction "P$2_K1") (pintype "bidirectional"))
      (node (ref "C06") (pin "K1") (pinfunction "P$2_K1") (pintype "bidirectional"))
      (node (ref "C07") (pin "K1") (pinfunction "P$2_K1") (pintype "bidirectional"))
      (node (ref "C08") (pin "K1") (pinfunction "P$2_K1") (pintype "bidirectional"))
      (node (ref "C09") (pin "K1") (pinfunction "P$2_K1") (pintype "bidirectional"))
      (node (ref "C10") (pin "K1") (pinfunction "P$2_K1") (pintype "bidirectional"))
      (node (ref "C11") (pin "K1") (pinfunction "P$2_K1") (pintype "bidirectional"))
      (node (ref "C12") (pin "K1") (pinfunction "P$2_K1") (pintype "bidirectional"))
      (node (ref "C13") (pin "K1") (pinfunction "P$2_K1") (pintype "bidirectional"))
      (node (ref "C14") (pin "K1") (pinfunction "P$2_K1") (pintype "bidirectional"))
    )
    (net (code "189") (name "Net-(C01R-P$2)") (class "Default")
      (node (ref "C01") (pin "K2") (pinfunction "P$2_K2") (pintype "bidirectional"))
      (node (ref "C02") (pin "K2") (pinfunction "P$2_K2") (pintype "bidirectional"))
      (node (ref "C03") (pin "K2") (pinfunction "P$2_K2") (pintype "bidirectional"))
      (node (ref "C04") (pin "K2") (pinfunction "P$2_K2") (pintype "bidirectional"))
      (node (ref "C05") (pin "K2") (pinfunction "P$2_K2") (pintype "bidirectional"))
      (node (ref "C06") (pin "K2") (pinfunction "P$2_K2") (pintype "bidirectional"))
      (node (ref "C07") (pin "K2") (pinfunction "P$2_K2") (pintype "bidirectional"))
      (node (ref "C08") (pin "K2") (pinfunction "P$2_K2") (pintype "bidirectional"))
      (node (ref "C09") (pin "K2") (pinfunction "P$2_K2") (pintype "bidirectional"))
      (node (ref "C10") (pin "K2") (pinfunction "P$2_K2") (pintype "bidirectional"))
      (node (ref "C11") (pin "K2") (pinfunction "P$2_K2") (pintype "bidirectional"))
      (node (ref "C12") (pin "K2") (pinfunction "P$2_K2") (pintype "bidirectional"))
      (node (ref "C13") (pin "K2") (pinfunction "P$2_K2") (pintype "bidirectional"))
      (node (ref "C14") (pin "K2") (pinfunction "P$2_K2") (pintype "bidirectional"))
    )
    (net (code "190") (name "Net-(C01S-P$2)") (class "Default")
      (node (ref "C01") (pin "L1") (pinfunction "P$2_L1") (pintype "bidirectional"))
      (node (ref "C02") (pin "L1") (pinfunction "P$2_L1") (pintype "bidirectional"))
      (node (ref "C03") (pin "L1") (pinfunction "P$2_L1") (pintype "bidirectional"))
      (node (ref "C04") (pin "L1") (pinfunction "P$2_L1") (pintype "bidirectional"))
      (node (ref "C05") (pin "L1") (pinfunction "P$2_L1") (pintype "bidirectional"))
      (node (ref "C06") (pin "L1") (pinfunction "P$2_L1") (pintype "bidirectional"))
      (node (ref "C07") (pin "L1") (pinfunction "P$2_L1") (pintype "bidirectional"))
      (node (ref "C08") (pin "L1") (pinfunction "P$2_L1") (pintype "bidirectional"))
      (node (ref "C09") (pin "L1") (pinfunction "P$2_L1") (pintype "bidirectional"))
      (node (ref "C10") (pin "L1") (pinfunction "P$2_L1") (pintype "bidirectional"))
      (node (ref "C11") (pin "L1") (pinfunction "P$2_L1") (pintype "bidirectional"))
      (node (ref "C12") (pin "L1") (pinfunction "P$2_L1") (pintype "bidirectional"))
      (node (ref "C13") (pin "L1") (pinfunction "P$2_L1") (pintype "bidirectional"))
      (node (ref "C14") (pin "L1") (pinfunction "P$2_L1") (pintype "bidirectional"))
    )
    (net (code "191") (name "Net-(C01T-P$2)") (class "Default")
      (node (ref "C01") (pin "L2") (pinfunction "P$2_L2") (pintype "bidirectional"))
      (node (ref "C02") (pin "L2") (pinfunction "P$2_L2") (pintype "bidirectional"))
      (node (ref "C03") (pin "L2") (pinfunction "P$2_L2") (pintype "bidirectional"))
      (node (ref "C04") (pin "L2") (pinfunction "P$2_L2") (pintype "bidirectional"))
      (node (ref "C05") (pin "L2") (pinfunction "P$2_L2") (pintype "bidirectional"))
      (node (ref "C06") (pin "L2") (pinfunction "P$2_L2") (pintype "bidirectional"))
      (node (ref "C07") (pin "L2") (pinfunction "P$2_L2") (pintype "bidirectional"))
      (node (ref "C08") (pin "L2") (pinfunction "P$2_L2") (pintype "bidirectional"))
      (node (ref "C09") (pin "L2") (pinfunction "P$2_L2") (pintype "bidirectional"))
      (node (ref "C10") (pin "L2") (pinfunction "P$2_L2") (pintype "bidirectional"))
      (node (ref "C11") (pin "L2") (pinfunction "P$2_L2") (pintype "bidirectional"))
      (node (ref "C12") (pin "L2") (pinfunction "P$2_L2") (pintype "bidirectional"))
      (node (ref "C13") (pin "L2") (pinfunction "P$2_L2") (pintype "bidirectional"))
      (node (ref "C14") (pin "L2") (pinfunction "P$2_L2") (pintype "bidirectional"))
    )
    (net (code "192") (name "Net-(C01U-P$2)") (class "Default")
      (node (ref "C01") (pin "M1") (pinfunction "P$2_M1") (pintype "bidirectional"))
      (node (ref "C02") (pin "M1") (pinfunction "P$2_M1") (pintype "bidirectional"))
      (node (ref "C03") (pin "M1") (pinfunction "P$2_M1") (pintype "bidirectional"))
      (node (ref "C04") (pin "M1") (pinfunction "P$2_M1") (pintype "bidirectional"))
      (node (ref "C05") (pin "M1") (pinfunction "P$2_M1") (pintype "bidirectional"))
      (node (ref "C06") (pin "M1") (pinfunction "P$2_M1") (pintype "bidirectional"))
      (node (ref "C07") (pin "M1") (pinfunction "P$2_M1") (pintype "bidirectional"))
      (node (ref "C08") (pin "M1") (pinfunction "P$2_M1") (pintype "bidirectional"))
      (node (ref "C09") (pin "M1") (pinfunction "P$2_M1") (pintype "bidirectional"))
      (node (ref "C10") (pin "M1") (pinfunction "P$2_M1") (pintype "bidirectional"))
      (node (ref "C11") (pin "M1") (pinfunction "P$2_M1") (pintype "bidirectional"))
      (node (ref "C12") (pin "M1") (pinfunction "P$2_M1") (pintype "bidirectional"))
      (node (ref "C13") (pin "M1") (pinfunction "P$2_M1") (pintype "bidirectional"))
      (node (ref "C14") (pin "M1") (pinfunction "P$2_M1") (pintype "bidirectional"))
    )
    (net (code "193") (name "Net-(C01V-P$2)") (class "Default")
      (node (ref "C01") (pin "M2") (pinfunction "P$2_M2") (pintype "bidirectional"))
      (node (ref "C02") (pin "M2") (pinfunction "P$2_M2") (pintype "bidirectional"))
      (node (ref "C03") (pin "M2") (pinfunction "P$2_M2") (pintype "bidirectional"))
      (node (ref "C04") (pin "M2") (pinfunction "P$2_M2") (pintype "bidirectional"))
      (node (ref "C05") (pin "M2") (pinfunction "P$2_M2") (pintype "bidirectional"))
      (node (ref "C06") (pin "M2") (pinfunction "P$2_M2") (pintype "bidirectional"))
      (node (ref "C07") (pin "M2") (pinfunction "P$2_M2") (pintype "bidirectional"))
      (node (ref "C08") (pin "M2") (pinfunction "P$2_M2") (pintype "bidirectional"))
      (node (ref "C09") (pin "M2") (pinfunction "P$2_M2") (pintype "bidirectional"))
      (node (ref "C10") (pin "M2") (pinfunction "P$2_M2") (pintype "bidirectional"))
      (node (ref "C11") (pin "M2") (pinfunction "P$2_M2") (pintype "bidirectional"))
      (node (ref "C12") (pin "M2") (pinfunction "P$2_M2") (pintype "bidirectional"))
      (node (ref "C13") (pin "M2") (pinfunction "P$2_M2") (pintype "bidirectional"))
      (node (ref "C14") (pin "M2") (pinfunction "P$2_M2") (pintype "bidirectional"))
    )
    (net (code "194") (name "Net-(C01Y-P$2)") (class "Default")
      (node (ref "C01") (pin "P1") (pinfunction "P$2_P1") (pintype "bidirectional"))
      (node (ref "C02") (pin "P1") (pinfunction "P$2_P1") (pintype "bidirectional"))
      (node (ref "C03") (pin "P1") (pinfunction "P$2_P1") (pintype "bidirectional"))
      (node (ref "C04") (pin "P1") (pinfunction "P$2_P1") (pintype "bidirectional"))
      (node (ref "C05") (pin "P1") (pinfunction "P$2_P1") (pintype "bidirectional"))
      (node (ref "C06") (pin "P1") (pinfunction "P$2_P1") (pintype "bidirectional"))
      (node (ref "C07") (pin "P1") (pinfunction "P$2_P1") (pintype "bidirectional"))
      (node (ref "C08") (pin "P1") (pinfunction "P$2_P1") (pintype "bidirectional"))
      (node (ref "C09") (pin "P1") (pinfunction "P$2_P1") (pintype "bidirectional"))
      (node (ref "C10") (pin "P1") (pinfunction "P$2_P1") (pintype "bidirectional"))
      (node (ref "C11") (pin "P1") (pinfunction "P$2_P1") (pintype "bidirectional"))
      (node (ref "C12") (pin "P1") (pinfunction "P$2_P1") (pintype "bidirectional"))
      (node (ref "C13") (pin "P1") (pinfunction "P$2_P1") (pintype "bidirectional"))
      (node (ref "C14") (pin "P1") (pinfunction "P$2_P1") (pintype "bidirectional"))
    )
    (net (code "195") (name "Net-(C01Z-P$2)") (class "Default")
      (node (ref "C01") (pin "P2") (pinfunction "P$2_P2") (pintype "bidirectional"))
      (node (ref "C02") (pin "P2") (pinfunction "P$2_P2") (pintype "bidirectional"))
      (node (ref "C03") (pin "P2") (pinfunction "P$2_P2") (pintype "bidirectional"))
      (node (ref "C04") (pin "P2") (pinfunction "P$2_P2") (pintype "bidirectional"))
      (node (ref "C05") (pin "P2") (pinfunction "P$2_P2") (pintype "bidirectional"))
      (node (ref "C06") (pin "P2") (pinfunction "P$2_P2") (pintype "bidirectional"))
      (node (ref "C07") (pin "P2") (pinfunction "P$2_P2") (pintype "bidirectional"))
      (node (ref "C08") (pin "P2") (pinfunction "P$2_P2") (pintype "bidirectional"))
      (node (ref "C09") (pin "P2") (pinfunction "P$2_P2") (pintype "bidirectional"))
      (node (ref "C10") (pin "P2") (pinfunction "P$2_P2") (pintype "bidirectional"))
      (node (ref "C11") (pin "P2") (pinfunction "P$2_P2") (pintype "bidirectional"))
      (node (ref "C12") (pin "P2") (pinfunction "P$2_P2") (pintype "bidirectional"))
      (node (ref "C13") (pin "P2") (pinfunction "P$2_P2") (pintype "bidirectional"))
      (node (ref "C14") (pin "P2") (pinfunction "P$2_P2") (pintype "bidirectional"))
    )
    (net (code "196") (name "Net-(C15A-IN2)") (class "Default")
      (node (ref "C15") (pin "B1") (pinfunction "IN2_B1") (pintype "input"))
      (node (ref "C15") (pin "C1") (pinfunction "IN3_C1") (pintype "input"))
      (node (ref "C15") (pin "D1") (pinfunction "IN4_D1") (pintype "input"))
      (node (ref "C15") (pin "H1") (pinfunction "IN2_H1") (pintype "input"))
      (node (ref "C15") (pin "J1") (pinfunction "IN3_J1") (pintype "input"))
      (node (ref "C15") (pin "K1") (pinfunction "IN4_K1") (pintype "input"))
      (node (ref "C15") (pin "N1") (pinfunction "IN2_N1") (pintype "input"))
      (node (ref "C15") (pin "P1") (pinfunction "IN3_P1") (pintype "input"))
      (node (ref "C15") (pin "R1") (pinfunction "IN4_R1") (pintype "input"))
      (node (ref "C15") (pin "V1") (pinfunction "P$1_V1") (pintype "passive"))
    )
    (net (code "197") (name "Net-(C15D-IN2)") (class "Default")
      (node (ref "C15") (pin "E2") (pinfunction "IN2_E2") (pintype "input"))
      (node (ref "C15") (pin "F2") (pinfunction "IN3_F2") (pintype "input"))
      (node (ref "C15") (pin "H2") (pinfunction "IN4_H2") (pintype "input"))
      (node (ref "C15") (pin "L2") (pinfunction "IN2_L2") (pintype "input"))
      (node (ref "C15") (pin "M2") (pinfunction "IN3_M2") (pintype "input"))
      (node (ref "C15") (pin "N2") (pinfunction "IN4_N2") (pintype "input"))
      (node (ref "C15") (pin "S2") (pinfunction "IN2_S2") (pintype "input"))
      (node (ref "C15") (pin "T2") (pinfunction "IN3_T2") (pintype "input"))
      (node (ref "C15") (pin "U1") (pinfunction "P$1_U1") (pintype "passive"))
      (node (ref "C15") (pin "U2") (pinfunction "IN4_U2") (pintype "input"))
    )
    (net (code "198") (name "Net-(C16A-IN2)") (class "Default")
      (node (ref "C16") (pin "B1") (pinfunction "IN2_B1") (pintype "input"))
      (node (ref "C16") (pin "C1") (pinfunction "IN3_C1") (pintype "input"))
      (node (ref "C16") (pin "D1") (pinfunction "IN4_D1") (pintype "input"))
      (node (ref "C16") (pin "H1") (pinfunction "IN2_H1") (pintype "input"))
      (node (ref "C16") (pin "J1") (pinfunction "IN3_J1") (pintype "input"))
      (node (ref "C16") (pin "K1") (pinfunction "IN4_K1") (pintype "input"))
      (node (ref "C16") (pin "N1") (pinfunction "IN2_N1") (pintype "input"))
      (node (ref "C16") (pin "P1") (pinfunction "IN3_P1") (pintype "input"))
      (node (ref "C16") (pin "R1") (pinfunction "IN4_R1") (pintype "input"))
      (node (ref "C16") (pin "V1") (pinfunction "P$1_V1") (pintype "passive"))
    )
    (net (code "199") (name "Net-(C16J-OUT)") (class "Default")
      (node (ref "C16") (pin "V2") (pinfunction "OUT_V2") (pintype "output"))
      (node (ref "D15") (pin "D1") (pinfunction "S_D1") (pintype "input"))
      (node (ref "D15") (pin "F2") (pinfunction "S_F2") (pintype "input"))
      (node (ref "D15") (pin "K1") (pinfunction "S_K1") (pintype "input"))
      (node (ref "D15") (pin "N2") (pinfunction "S_N2") (pintype "input"))
      (node (ref "D15") (pin "R1") (pinfunction "S_R1") (pintype "input"))
      (node (ref "D15") (pin "U2") (pinfunction "S_U2") (pintype "input"))
      (node (ref "D16") (pin "D1") (pinfunction "S_D1") (pintype "input"))
      (node (ref "D16") (pin "F2") (pinfunction "S_F2") (pintype "input"))
      (node (ref "D16") (pin "K1") (pinfunction "S_K1") (pintype "input"))
      (node (ref "D16") (pin "N2") (pinfunction "S_N2") (pintype "input"))
      (node (ref "D16") (pin "R1") (pinfunction "S_R1") (pintype "input"))
      (node (ref "D16") (pin "U2") (pinfunction "S_U2") (pintype "input"))
    )
    (net (code "200") (name "Net-(C18A-IN)") (class "Default")
      (node (ref "C18") (pin "E1") (pinfunction "IN_E1") (pintype "input"))
      (node (ref "C18") (pin "J2") (pinfunction "J2_J2") (pintype "output"))
    )
    (net (code "201") (name "Net-(C19A-IN)") (class "Default")
      (node (ref "C19") (pin "E1") (pinfunction "IN_E1") (pintype "input"))
      (node (ref "C19") (pin "L2") (pinfunction "L2_L2") (pintype "output"))
    )
    (net (code "202") (name "Net-(C19E-IN)") (class "Default")
      (node (ref "C19") (pin "H1") (pinfunction "IN_H1") (pintype "input"))
      (node (ref "C19") (pin "M2") (pinfunction "M2_M2") (pintype "output"))
    )
    (net (code "203") (name "Net-(C20A-IN)") (class "Default")
      (node (ref "C20") (pin "E1") (pinfunction "IN_E1") (pintype "input"))
      (node (ref "C20") (pin "K2") (pinfunction "K2_K2") (pintype "output"))
    )
    (net (code "204") (name "Net-(C20E-IN)") (class "Default")
      (node (ref "C20") (pin "H1") (pinfunction "IN_H1") (pintype "input"))
      (node (ref "C20") (pin "N2") (pinfunction "N2_N2") (pintype "output"))
    )
    (net (code "205") (name "Net-(D01A-P$2)") (class "Default")
      (node (ref "D01") (pin "A1") (pinfunction "P$2_A1") (pintype "bidirectional"))
      (node (ref "D02") (pin "A1") (pinfunction "P$2_A1") (pintype "bidirectional"))
      (node (ref "D03") (pin "A1") (pinfunction "P$2_A1") (pintype "bidirectional"))
      (node (ref "D04") (pin "A1") (pinfunction "P$2_A1") (pintype "bidirectional"))
      (node (ref "D05") (pin "A1") (pinfunction "P$2_A1") (pintype "bidirectional"))
      (node (ref "D06") (pin "A1") (pinfunction "P$2_A1") (pintype "bidirectional"))
      (node (ref "D07") (pin "A1") (pinfunction "P$2_A1") (pintype "bidirectional"))
      (node (ref "D08") (pin "A1") (pinfunction "P$2_A1") (pintype "bidirectional"))
      (node (ref "D09") (pin "A1") (pinfunction "P$2_A1") (pintype "bidirectional"))
      (node (ref "D10") (pin "A1") (pinfunction "P$2_A1") (pintype "bidirectional"))
      (node (ref "D11") (pin "A1") (pinfunction "P$2_A1") (pintype "bidirectional"))
      (node (ref "D12") (pin "A1") (pinfunction "P$2_A1") (pintype "bidirectional"))
      (node (ref "D13") (pin "A1") (pinfunction "P$2_A1") (pintype "bidirectional"))
      (node (ref "D14") (pin "A1") (pinfunction "P$2_A1") (pintype "bidirectional"))
    )
    (net (code "206") (name "Net-(D01AA-P$2)") (class "Default")
      (node (ref "D01") (pin "R1") (pinfunction "P$2_R1") (pintype "bidirectional"))
      (node (ref "D02") (pin "R1") (pinfunction "P$2_R1") (pintype "bidirectional"))
      (node (ref "D03") (pin "R1") (pinfunction "P$2_R1") (pintype "bidirectional"))
      (node (ref "D04") (pin "R1") (pinfunction "P$2_R1") (pintype "bidirectional"))
      (node (ref "D05") (pin "R1") (pinfunction "P$2_R1") (pintype "bidirectional"))
      (node (ref "D06") (pin "R1") (pinfunction "P$2_R1") (pintype "bidirectional"))
      (node (ref "D07") (pin "R1") (pinfunction "P$2_R1") (pintype "bidirectional"))
      (node (ref "D08") (pin "R1") (pinfunction "P$2_R1") (pintype "bidirectional"))
      (node (ref "D09") (pin "R1") (pinfunction "P$2_R1") (pintype "bidirectional"))
      (node (ref "D10") (pin "R1") (pinfunction "P$2_R1") (pintype "bidirectional"))
      (node (ref "D11") (pin "R1") (pinfunction "P$2_R1") (pintype "bidirectional"))
      (node (ref "D12") (pin "R1") (pinfunction "P$2_R1") (pintype "bidirectional"))
      (node (ref "D13") (pin "R1") (pinfunction "P$2_R1") (pintype "bidirectional"))
      (node (ref "D14") (pin "R1") (pinfunction "P$2_R1") (pintype "bidirectional"))
    )
    (net (code "207") (name "Net-(D01AB-P$2)") (class "Default")
      (node (ref "D01") (pin "R2") (pinfunction "P$2_R2") (pintype "bidirectional"))
      (node (ref "D02") (pin "R2") (pinfunction "P$2_R2") (pintype "bidirectional"))
      (node (ref "D03") (pin "R2") (pinfunction "P$2_R2") (pintype "bidirectional"))
      (node (ref "D04") (pin "R2") (pinfunction "P$2_R2") (pintype "bidirectional"))
      (node (ref "D05") (pin "R2") (pinfunction "P$2_R2") (pintype "bidirectional"))
      (node (ref "D06") (pin "R2") (pinfunction "P$2_R2") (pintype "bidirectional"))
      (node (ref "D07") (pin "R2") (pinfunction "P$2_R2") (pintype "bidirectional"))
      (node (ref "D08") (pin "R2") (pinfunction "P$2_R2") (pintype "bidirectional"))
      (node (ref "D09") (pin "R2") (pinfunction "P$2_R2") (pintype "bidirectional"))
      (node (ref "D10") (pin "R2") (pinfunction "P$2_R2") (pintype "bidirectional"))
      (node (ref "D11") (pin "R2") (pinfunction "P$2_R2") (pintype "bidirectional"))
      (node (ref "D12") (pin "R2") (pinfunction "P$2_R2") (pintype "bidirectional"))
      (node (ref "D13") (pin "R2") (pinfunction "P$2_R2") (pintype "bidirectional"))
      (node (ref "D14") (pin "R2") (pinfunction "P$2_R2") (pintype "bidirectional"))
    )
    (net (code "208") (name "Net-(D01AD-P$2)") (class "Default")
      (node (ref "D01") (pin "S2") (pinfunction "P$2_S2") (pintype "bidirectional"))
      (node (ref "D02") (pin "S2") (pinfunction "P$2_S2") (pintype "bidirectional"))
      (node (ref "D03") (pin "S2") (pinfunction "P$2_S2") (pintype "bidirectional"))
      (node (ref "D04") (pin "S2") (pinfunction "P$2_S2") (pintype "bidirectional"))
      (node (ref "D05") (pin "S2") (pinfunction "P$2_S2") (pintype "bidirectional"))
      (node (ref "D06") (pin "S2") (pinfunction "P$2_S2") (pintype "bidirectional"))
      (node (ref "D07") (pin "S2") (pinfunction "P$2_S2") (pintype "bidirectional"))
      (node (ref "D08") (pin "S2") (pinfunction "P$2_S2") (pintype "bidirectional"))
      (node (ref "D09") (pin "S2") (pinfunction "P$2_S2") (pintype "bidirectional"))
      (node (ref "D10") (pin "S2") (pinfunction "P$2_S2") (pintype "bidirectional"))
      (node (ref "D11") (pin "S2") (pinfunction "P$2_S2") (pintype "bidirectional"))
      (node (ref "D12") (pin "S2") (pinfunction "P$2_S2") (pintype "bidirectional"))
      (node (ref "D13") (pin "S2") (pinfunction "P$2_S2") (pintype "bidirectional"))
      (node (ref "D14") (pin "S2") (pinfunction "P$2_S2") (pintype "bidirectional"))
    )
    (net (code "209") (name "Net-(D01AG-P$2)") (class "Default")
      (node (ref "D01") (pin "U1") (pinfunction "P$2_U1") (pintype "bidirectional"))
      (node (ref "D02") (pin "U1") (pinfunction "P$2_U1") (pintype "bidirectional"))
      (node (ref "D03") (pin "U1") (pinfunction "P$2_U1") (pintype "bidirectional"))
      (node (ref "D04") (pin "U1") (pinfunction "P$2_U1") (pintype "bidirectional"))
      (node (ref "D05") (pin "U1") (pinfunction "P$2_U1") (pintype "bidirectional"))
      (node (ref "D06") (pin "U1") (pinfunction "P$2_U1") (pintype "bidirectional"))
      (node (ref "D07") (pin "U1") (pinfunction "P$2_U1") (pintype "bidirectional"))
      (node (ref "D08") (pin "U1") (pinfunction "P$2_U1") (pintype "bidirectional"))
      (node (ref "D09") (pin "U1") (pinfunction "P$2_U1") (pintype "bidirectional"))
      (node (ref "D10") (pin "U1") (pinfunction "P$2_U1") (pintype "bidirectional"))
      (node (ref "D11") (pin "U1") (pinfunction "P$2_U1") (pintype "bidirectional"))
      (node (ref "D12") (pin "U1") (pinfunction "P$2_U1") (pintype "bidirectional"))
      (node (ref "D13") (pin "U1") (pinfunction "P$2_U1") (pintype "bidirectional"))
      (node (ref "D14") (pin "U1") (pinfunction "P$2_U1") (pintype "bidirectional"))
    )
    (net (code "210") (name "Net-(D01AH-P$2)") (class "Default")
      (node (ref "D01") (pin "U2") (pinfunction "P$2_U2") (pintype "bidirectional"))
      (node (ref "D02") (pin "U2") (pinfunction "P$2_U2") (pintype "bidirectional"))
      (node (ref "D03") (pin "U2") (pinfunction "P$2_U2") (pintype "bidirectional"))
      (node (ref "D04") (pin "U2") (pinfunction "P$2_U2") (pintype "bidirectional"))
      (node (ref "D05") (pin "U2") (pinfunction "P$2_U2") (pintype "bidirectional"))
      (node (ref "D06") (pin "U2") (pinfunction "P$2_U2") (pintype "bidirectional"))
      (node (ref "D07") (pin "U2") (pinfunction "P$2_U2") (pintype "bidirectional"))
      (node (ref "D08") (pin "U2") (pinfunction "P$2_U2") (pintype "bidirectional"))
      (node (ref "D09") (pin "U2") (pinfunction "P$2_U2") (pintype "bidirectional"))
      (node (ref "D10") (pin "U2") (pinfunction "P$2_U2") (pintype "bidirectional"))
      (node (ref "D11") (pin "U2") (pinfunction "P$2_U2") (pintype "bidirectional"))
      (node (ref "D12") (pin "U2") (pinfunction "P$2_U2") (pintype "bidirectional"))
      (node (ref "D13") (pin "U2") (pinfunction "P$2_U2") (pintype "bidirectional"))
      (node (ref "D14") (pin "U2") (pinfunction "P$2_U2") (pintype "bidirectional"))
    )
    (net (code "211") (name "Net-(D01AI-P$2)") (class "Default")
      (node (ref "D01") (pin "V1") (pinfunction "P$2_V1") (pintype "bidirectional"))
      (node (ref "D02") (pin "V1") (pinfunction "P$2_V1") (pintype "bidirectional"))
      (node (ref "D03") (pin "V1") (pinfunction "P$2_V1") (pintype "bidirectional"))
      (node (ref "D04") (pin "V1") (pinfunction "P$2_V1") (pintype "bidirectional"))
      (node (ref "D05") (pin "V1") (pinfunction "P$2_V1") (pintype "bidirectional"))
      (node (ref "D06") (pin "V1") (pinfunction "P$2_V1") (pintype "bidirectional"))
      (node (ref "D07") (pin "V1") (pinfunction "P$2_V1") (pintype "bidirectional"))
      (node (ref "D08") (pin "V1") (pinfunction "P$2_V1") (pintype "bidirectional"))
      (node (ref "D09") (pin "V1") (pinfunction "P$2_V1") (pintype "bidirectional"))
      (node (ref "D10") (pin "V1") (pinfunction "P$2_V1") (pintype "bidirectional"))
      (node (ref "D11") (pin "V1") (pinfunction "P$2_V1") (pintype "bidirectional"))
      (node (ref "D12") (pin "V1") (pinfunction "P$2_V1") (pintype "bidirectional"))
      (node (ref "D13") (pin "V1") (pinfunction "P$2_V1") (pintype "bidirectional"))
      (node (ref "D14") (pin "V1") (pinfunction "P$2_V1") (pintype "bidirectional"))
    )
    (net (code "212") (name "Net-(D01AJ-P$2)") (class "Default")
      (node (ref "D01") (pin "V2") (pinfunction "P$2_V2") (pintype "bidirectional"))
      (node (ref "D02") (pin "V2") (pinfunction "P$2_V2") (pintype "bidirectional"))
      (node (ref "D03") (pin "V2") (pinfunction "P$2_V2") (pintype "bidirectional"))
      (node (ref "D04") (pin "V2") (pinfunction "P$2_V2") (pintype "bidirectional"))
      (node (ref "D05") (pin "V2") (pinfunction "P$2_V2") (pintype "bidirectional"))
      (node (ref "D06") (pin "V2") (pinfunction "P$2_V2") (pintype "bidirectional"))
      (node (ref "D07") (pin "V2") (pinfunction "P$2_V2") (pintype "bidirectional"))
      (node (ref "D08") (pin "V2") (pinfunction "P$2_V2") (pintype "bidirectional"))
      (node (ref "D09") (pin "V2") (pinfunction "P$2_V2") (pintype "bidirectional"))
      (node (ref "D10") (pin "V2") (pinfunction "P$2_V2") (pintype "bidirectional"))
      (node (ref "D11") (pin "V2") (pinfunction "P$2_V2") (pintype "bidirectional"))
      (node (ref "D12") (pin "V2") (pinfunction "P$2_V2") (pintype "bidirectional"))
      (node (ref "D13") (pin "V2") (pinfunction "P$2_V2") (pintype "bidirectional"))
      (node (ref "D14") (pin "V2") (pinfunction "P$2_V2") (pintype "bidirectional"))
    )
    (net (code "213") (name "Net-(D01C-P$2)") (class "Default")
      (node (ref "D01") (pin "B1") (pinfunction "P$2_B1") (pintype "bidirectional"))
      (node (ref "D02") (pin "B1") (pinfunction "P$2_B1") (pintype "bidirectional"))
      (node (ref "D03") (pin "B1") (pinfunction "P$2_B1") (pintype "bidirectional"))
      (node (ref "D04") (pin "B1") (pinfunction "P$2_B1") (pintype "bidirectional"))
      (node (ref "D05") (pin "B1") (pinfunction "P$2_B1") (pintype "bidirectional"))
      (node (ref "D06") (pin "B1") (pinfunction "P$2_B1") (pintype "bidirectional"))
      (node (ref "D07") (pin "B1") (pinfunction "P$2_B1") (pintype "bidirectional"))
      (node (ref "D08") (pin "B1") (pinfunction "P$2_B1") (pintype "bidirectional"))
      (node (ref "D09") (pin "B1") (pinfunction "P$2_B1") (pintype "bidirectional"))
      (node (ref "D10") (pin "B1") (pinfunction "P$2_B1") (pintype "bidirectional"))
      (node (ref "D11") (pin "B1") (pinfunction "P$2_B1") (pintype "bidirectional"))
      (node (ref "D12") (pin "B1") (pinfunction "P$2_B1") (pintype "bidirectional"))
      (node (ref "D13") (pin "B1") (pinfunction "P$2_B1") (pintype "bidirectional"))
      (node (ref "D14") (pin "B1") (pinfunction "P$2_B1") (pintype "bidirectional"))
    )
    (net (code "214") (name "Net-(D01H-P$2)") (class "Default")
      (node (ref "D01") (pin "D2") (pinfunction "P$2_D2") (pintype "bidirectional"))
      (node (ref "D02") (pin "D2") (pinfunction "P$2_D2") (pintype "bidirectional"))
      (node (ref "D03") (pin "D2") (pinfunction "P$2_D2") (pintype "bidirectional"))
      (node (ref "D04") (pin "D2") (pinfunction "P$2_D2") (pintype "bidirectional"))
      (node (ref "D05") (pin "D2") (pinfunction "P$2_D2") (pintype "bidirectional"))
      (node (ref "D06") (pin "D2") (pinfunction "P$2_D2") (pintype "bidirectional"))
      (node (ref "D07") (pin "D2") (pinfunction "P$2_D2") (pintype "bidirectional"))
      (node (ref "D08") (pin "D2") (pinfunction "P$2_D2") (pintype "bidirectional"))
      (node (ref "D09") (pin "D2") (pinfunction "P$2_D2") (pintype "bidirectional"))
      (node (ref "D10") (pin "D2") (pinfunction "P$2_D2") (pintype "bidirectional"))
      (node (ref "D11") (pin "D2") (pinfunction "P$2_D2") (pintype "bidirectional"))
      (node (ref "D12") (pin "D2") (pinfunction "P$2_D2") (pintype "bidirectional"))
      (node (ref "D13") (pin "D2") (pinfunction "P$2_D2") (pintype "bidirectional"))
      (node (ref "D14") (pin "D2") (pinfunction "P$2_D2") (pintype "bidirectional"))
    )
    (net (code "215") (name "Net-(D01J-P$2)") (class "Default")
      (node (ref "D01") (pin "E2") (pinfunction "P$2_E2") (pintype "bidirectional"))
      (node (ref "D02") (pin "E2") (pinfunction "P$2_E2") (pintype "bidirectional"))
      (node (ref "D03") (pin "E2") (pinfunction "P$2_E2") (pintype "bidirectional"))
      (node (ref "D04") (pin "E2") (pinfunction "P$2_E2") (pintype "bidirectional"))
      (node (ref "D05") (pin "E2") (pinfunction "P$2_E2") (pintype "bidirectional"))
      (node (ref "D06") (pin "E2") (pinfunction "P$2_E2") (pintype "bidirectional"))
      (node (ref "D07") (pin "E2") (pinfunction "P$2_E2") (pintype "bidirectional"))
      (node (ref "D08") (pin "E2") (pinfunction "P$2_E2") (pintype "bidirectional"))
      (node (ref "D09") (pin "E2") (pinfunction "P$2_E2") (pintype "bidirectional"))
      (node (ref "D10") (pin "E2") (pinfunction "P$2_E2") (pintype "bidirectional"))
      (node (ref "D11") (pin "E2") (pinfunction "P$2_E2") (pintype "bidirectional"))
      (node (ref "D12") (pin "E2") (pinfunction "P$2_E2") (pintype "bidirectional"))
      (node (ref "D13") (pin "E2") (pinfunction "P$2_E2") (pintype "bidirectional"))
      (node (ref "D14") (pin "E2") (pinfunction "P$2_E2") (pintype "bidirectional"))
    )
    (net (code "216") (name "Net-(D01N-P$2)") (class "Default")
      (node (ref "D01") (pin "H2") (pinfunction "P$2_H2") (pintype "bidirectional"))
      (node (ref "D02") (pin "H2") (pinfunction "P$2_H2") (pintype "bidirectional"))
      (node (ref "D03") (pin "H2") (pinfunction "P$2_H2") (pintype "bidirectional"))
      (node (ref "D04") (pin "H2") (pinfunction "P$2_H2") (pintype "bidirectional"))
      (node (ref "D05") (pin "H2") (pinfunction "P$2_H2") (pintype "bidirectional"))
      (node (ref "D06") (pin "H2") (pinfunction "P$2_H2") (pintype "bidirectional"))
      (node (ref "D07") (pin "H2") (pinfunction "P$2_H2") (pintype "bidirectional"))
      (node (ref "D08") (pin "H2") (pinfunction "P$2_H2") (pintype "bidirectional"))
      (node (ref "D09") (pin "H2") (pinfunction "P$2_H2") (pintype "bidirectional"))
      (node (ref "D10") (pin "H2") (pinfunction "P$2_H2") (pintype "bidirectional"))
      (node (ref "D11") (pin "H2") (pinfunction "P$2_H2") (pintype "bidirectional"))
      (node (ref "D12") (pin "H2") (pinfunction "P$2_H2") (pintype "bidirectional"))
      (node (ref "D13") (pin "H2") (pinfunction "P$2_H2") (pintype "bidirectional"))
      (node (ref "D14") (pin "H2") (pinfunction "P$2_H2") (pintype "bidirectional"))
    )
    (net (code "217") (name "Net-(D01P-P$2)") (class "Default")
      (node (ref "D01") (pin "J2") (pinfunction "P$2_J2") (pintype "bidirectional"))
      (node (ref "D02") (pin "J2") (pinfunction "P$2_J2") (pintype "bidirectional"))
      (node (ref "D03") (pin "J2") (pinfunction "P$2_J2") (pintype "bidirectional"))
      (node (ref "D04") (pin "J2") (pinfunction "P$2_J2") (pintype "bidirectional"))
      (node (ref "D05") (pin "J2") (pinfunction "P$2_J2") (pintype "bidirectional"))
      (node (ref "D06") (pin "J2") (pinfunction "P$2_J2") (pintype "bidirectional"))
      (node (ref "D07") (pin "J2") (pinfunction "P$2_J2") (pintype "bidirectional"))
      (node (ref "D08") (pin "J2") (pinfunction "P$2_J2") (pintype "bidirectional"))
      (node (ref "D09") (pin "J2") (pinfunction "P$2_J2") (pintype "bidirectional"))
      (node (ref "D10") (pin "J2") (pinfunction "P$2_J2") (pintype "bidirectional"))
      (node (ref "D11") (pin "J2") (pinfunction "P$2_J2") (pintype "bidirectional"))
      (node (ref "D12") (pin "J2") (pinfunction "P$2_J2") (pintype "bidirectional"))
      (node (ref "D13") (pin "J2") (pinfunction "P$2_J2") (pintype "bidirectional"))
      (node (ref "D14") (pin "J2") (pinfunction "P$2_J2") (pintype "bidirectional"))
    )
    (net (code "218") (name "Net-(D01R-P$2)") (class "Default")
      (node (ref "D01") (pin "K2") (pinfunction "P$2_K2") (pintype "bidirectional"))
      (node (ref "D02") (pin "K2") (pinfunction "P$2_K2") (pintype "bidirectional"))
      (node (ref "D03") (pin "K2") (pinfunction "P$2_K2") (pintype "bidirectional"))
      (node (ref "D04") (pin "K2") (pinfunction "P$2_K2") (pintype "bidirectional"))
      (node (ref "D05") (pin "K2") (pinfunction "P$2_K2") (pintype "bidirectional"))
      (node (ref "D06") (pin "K2") (pinfunction "P$2_K2") (pintype "bidirectional"))
      (node (ref "D07") (pin "K2") (pinfunction "P$2_K2") (pintype "bidirectional"))
      (node (ref "D08") (pin "K2") (pinfunction "P$2_K2") (pintype "bidirectional"))
      (node (ref "D09") (pin "K2") (pinfunction "P$2_K2") (pintype "bidirectional"))
      (node (ref "D10") (pin "K2") (pinfunction "P$2_K2") (pintype "bidirectional"))
      (node (ref "D11") (pin "K2") (pinfunction "P$2_K2") (pintype "bidirectional"))
      (node (ref "D12") (pin "K2") (pinfunction "P$2_K2") (pintype "bidirectional"))
      (node (ref "D13") (pin "K2") (pinfunction "P$2_K2") (pintype "bidirectional"))
      (node (ref "D14") (pin "K2") (pinfunction "P$2_K2") (pintype "bidirectional"))
    )
    (net (code "219") (name "Net-(D01T-P$2)") (class "Default")
      (node (ref "D01") (pin "L2") (pinfunction "P$2_L2") (pintype "bidirectional"))
      (node (ref "D02") (pin "L2") (pinfunction "P$2_L2") (pintype "bidirectional"))
      (node (ref "D03") (pin "L2") (pinfunction "P$2_L2") (pintype "bidirectional"))
      (node (ref "D04") (pin "L2") (pinfunction "P$2_L2") (pintype "bidirectional"))
      (node (ref "D05") (pin "L2") (pinfunction "P$2_L2") (pintype "bidirectional"))
      (node (ref "D06") (pin "L2") (pinfunction "P$2_L2") (pintype "bidirectional"))
      (node (ref "D07") (pin "L2") (pinfunction "P$2_L2") (pintype "bidirectional"))
      (node (ref "D08") (pin "L2") (pinfunction "P$2_L2") (pintype "bidirectional"))
      (node (ref "D09") (pin "L2") (pinfunction "P$2_L2") (pintype "bidirectional"))
      (node (ref "D10") (pin "L2") (pinfunction "P$2_L2") (pintype "bidirectional"))
      (node (ref "D11") (pin "L2") (pinfunction "P$2_L2") (pintype "bidirectional"))
      (node (ref "D12") (pin "L2") (pinfunction "P$2_L2") (pintype "bidirectional"))
      (node (ref "D13") (pin "L2") (pinfunction "P$2_L2") (pintype "bidirectional"))
      (node (ref "D14") (pin "L2") (pinfunction "P$2_L2") (pintype "bidirectional"))
    )
    (net (code "220") (name "Net-(D01V-P$2)") (class "Default")
      (node (ref "D01") (pin "M2") (pinfunction "P$2_M2") (pintype "bidirectional"))
      (node (ref "D02") (pin "M2") (pinfunction "P$2_M2") (pintype "bidirectional"))
      (node (ref "D03") (pin "M2") (pinfunction "P$2_M2") (pintype "bidirectional"))
      (node (ref "D04") (pin "M2") (pinfunction "P$2_M2") (pintype "bidirectional"))
      (node (ref "D05") (pin "M2") (pinfunction "P$2_M2") (pintype "bidirectional"))
      (node (ref "D06") (pin "M2") (pinfunction "P$2_M2") (pintype "bidirectional"))
      (node (ref "D07") (pin "M2") (pinfunction "P$2_M2") (pintype "bidirectional"))
      (node (ref "D08") (pin "M2") (pinfunction "P$2_M2") (pintype "bidirectional"))
      (node (ref "D09") (pin "M2") (pinfunction "P$2_M2") (pintype "bidirectional"))
      (node (ref "D10") (pin "M2") (pinfunction "P$2_M2") (pintype "bidirectional"))
      (node (ref "D11") (pin "M2") (pinfunction "P$2_M2") (pintype "bidirectional"))
      (node (ref "D12") (pin "M2") (pinfunction "P$2_M2") (pintype "bidirectional"))
      (node (ref "D13") (pin "M2") (pinfunction "P$2_M2") (pintype "bidirectional"))
      (node (ref "D14") (pin "M2") (pinfunction "P$2_M2") (pintype "bidirectional"))
    )
    (net (code "221") (name "Net-(D01Z-P$2)") (class "Default")
      (node (ref "D01") (pin "P2") (pinfunction "P$2_P2") (pintype "bidirectional"))
      (node (ref "D02") (pin "P2") (pinfunction "P$2_P2") (pintype "bidirectional"))
      (node (ref "D03") (pin "P2") (pinfunction "P$2_P2") (pintype "bidirectional"))
      (node (ref "D04") (pin "P2") (pinfunction "P$2_P2") (pintype "bidirectional"))
      (node (ref "D05") (pin "P2") (pinfunction "P$2_P2") (pintype "bidirectional"))
      (node (ref "D06") (pin "P2") (pinfunction "P$2_P2") (pintype "bidirectional"))
      (node (ref "D07") (pin "P2") (pinfunction "P$2_P2") (pintype "bidirectional"))
      (node (ref "D08") (pin "P2") (pinfunction "P$2_P2") (pintype "bidirectional"))
      (node (ref "D09") (pin "P2") (pinfunction "P$2_P2") (pintype "bidirectional"))
      (node (ref "D10") (pin "P2") (pinfunction "P$2_P2") (pintype "bidirectional"))
      (node (ref "D11") (pin "P2") (pinfunction "P$2_P2") (pintype "bidirectional"))
      (node (ref "D12") (pin "P2") (pinfunction "P$2_P2") (pintype "bidirectional"))
      (node (ref "D13") (pin "P2") (pinfunction "P$2_P2") (pintype "bidirectional"))
      (node (ref "D14") (pin "P2") (pinfunction "P$2_P2") (pintype "bidirectional"))
    )
    (net (code "222") (name "Net-(D18B-OUT)") (class "Default")
      (node (ref "D18") (pin "D2") (pinfunction "OUT_D2") (pintype "output"))
      (node (ref "D19") (pin "B1") (pinfunction "L2_B1") (pintype "bidirectional"))
    )
    (net (code "223") (name "Net-(D18H-OUT)") (class "Default")
      (node (ref "D18") (pin "J2") (pinfunction "OUT_J2") (pintype "output"))
      (node (ref "D19") (pin "C1") (pinfunction "L3_C1") (pintype "bidirectional"))
    )
    (net (code "224") (name "VCC") (class "Default")
      (node (ref "+5V") (pin "1") (pinfunction "P_1") (pintype "passive"))
      (node (ref "A01") (pin "A2") (pinfunction "P$2_A2") (pintype "bidirectional"))
      (node (ref "A02") (pin "A2") (pinfunction "P$2_A2") (pintype "bidirectional"))
      (node (ref "A03") (pin "A2") (pinfunction "P$2_A2") (pintype "bidirectional"))
      (node (ref "A04") (pin "A2") (pinfunction "P$2_A2") (pintype "bidirectional"))
      (node (ref "A05") (pin "A2") (pinfunction "P$2_A2") (pintype "bidirectional"))
      (node (ref "A06") (pin "A2") (pinfunction "P$2_A2") (pintype "bidirectional"))
      (node (ref "A07") (pin "A2") (pinfunction "P$2_A2") (pintype "bidirectional"))
      (node (ref "A08") (pin "A2") (pinfunction "P$2_A2") (pintype "bidirectional"))
      (node (ref "A09") (pin "A2") (pinfunction "P$2_A2") (pintype "bidirectional"))
      (node (ref "A10") (pin "A2") (pinfunction "P$2_A2") (pintype "bidirectional"))
      (node (ref "A11") (pin "A2") (pinfunction "P$2_A2") (pintype "bidirectional"))
      (node (ref "A12") (pin "A2") (pinfunction "P$2_A2") (pintype "bidirectional"))
      (node (ref "A13") (pin "A2") (pinfunction "P$2_A2") (pintype "bidirectional"))
      (node (ref "A14") (pin "A2") (pinfunction "P$2_A2") (pintype "bidirectional"))
      (node (ref "B01") (pin "A2") (pinfunction "P$2_A2") (pintype "bidirectional"))
      (node (ref "B02") (pin "A2") (pinfunction "P$2_A2") (pintype "bidirectional"))
      (node (ref "B03") (pin "A2") (pinfunction "P$2_A2") (pintype "bidirectional"))
      (node (ref "B04") (pin "A2") (pinfunction "P$2_A2") (pintype "bidirectional"))
      (node (ref "B05") (pin "A2") (pinfunction "P$2_A2") (pintype "bidirectional"))
      (node (ref "B06") (pin "A2") (pinfunction "P$2_A2") (pintype "bidirectional"))
      (node (ref "B07") (pin "A2") (pinfunction "P$2_A2") (pintype "bidirectional"))
      (node (ref "B08") (pin "A2") (pinfunction "P$2_A2") (pintype "bidirectional"))
      (node (ref "B09") (pin "A2") (pinfunction "P$2_A2") (pintype "bidirectional"))
      (node (ref "B10") (pin "A2") (pinfunction "P$2_A2") (pintype "bidirectional"))
      (node (ref "B11") (pin "A2") (pinfunction "P$2_A2") (pintype "bidirectional"))
      (node (ref "B12") (pin "A2") (pinfunction "P$2_A2") (pintype "bidirectional"))
      (node (ref "B13") (pin "A2") (pinfunction "P$2_A2") (pintype "bidirectional"))
      (node (ref "B14") (pin "A2") (pinfunction "P$2_A2") (pintype "bidirectional"))
      (node (ref "C01") (pin "A2") (pinfunction "P$2_A2") (pintype "bidirectional"))
      (node (ref "C02") (pin "A2") (pinfunction "P$2_A2") (pintype "bidirectional"))
      (node (ref "C03") (pin "A2") (pinfunction "P$2_A2") (pintype "bidirectional"))
      (node (ref "C04") (pin "A2") (pinfunction "P$2_A2") (pintype "bidirectional"))
      (node (ref "C05") (pin "A2") (pinfunction "P$2_A2") (pintype "bidirectional"))
      (node (ref "C06") (pin "A2") (pinfunction "P$2_A2") (pintype "bidirectional"))
      (node (ref "C07") (pin "A2") (pinfunction "P$2_A2") (pintype "bidirectional"))
      (node (ref "C08") (pin "A2") (pinfunction "P$2_A2") (pintype "bidirectional"))
      (node (ref "C09") (pin "A2") (pinfunction "P$2_A2") (pintype "bidirectional"))
      (node (ref "C10") (pin "A2") (pinfunction "P$2_A2") (pintype "bidirectional"))
      (node (ref "C11") (pin "A2") (pinfunction "P$2_A2") (pintype "bidirectional"))
      (node (ref "C12") (pin "A2") (pinfunction "P$2_A2") (pintype "bidirectional"))
      (node (ref "C13") (pin "A2") (pinfunction "P$2_A2") (pintype "bidirectional"))
      (node (ref "C14") (pin "A2") (pinfunction "P$2_A2") (pintype "bidirectional"))
      (node (ref "D01") (pin "A2") (pinfunction "P$2_A2") (pintype "bidirectional"))
      (node (ref "D02") (pin "A2") (pinfunction "P$2_A2") (pintype "bidirectional"))
      (node (ref "D03") (pin "A2") (pinfunction "P$2_A2") (pintype "bidirectional"))
      (node (ref "D04") (pin "A2") (pinfunction "P$2_A2") (pintype "bidirectional"))
      (node (ref "D05") (pin "A2") (pinfunction "P$2_A2") (pintype "bidirectional"))
      (node (ref "D06") (pin "A2") (pinfunction "P$2_A2") (pintype "bidirectional"))
      (node (ref "D07") (pin "A2") (pinfunction "P$2_A2") (pintype "bidirectional"))
      (node (ref "D08") (pin "A2") (pinfunction "P$2_A2") (pintype "bidirectional"))
      (node (ref "D09") (pin "A2") (pinfunction "P$2_A2") (pintype "bidirectional"))
      (node (ref "D10") (pin "A2") (pinfunction "P$2_A2") (pintype "bidirectional"))
      (node (ref "D11") (pin "A2") (pinfunction "P$2_A2") (pintype "bidirectional"))
      (node (ref "D12") (pin "A2") (pinfunction "P$2_A2") (pintype "bidirectional"))
      (node (ref "D13") (pin "A2") (pinfunction "P$2_A2") (pintype "bidirectional"))
      (node (ref "D14") (pin "A2") (pinfunction "P$2_A2") (pintype "bidirectional"))
    )
    (net (code "225") (name "unconnected-(C17D-1-PadH2)") (class "Default")
      (node (ref "C17") (pin "H2") (pinfunction "1_H2") (pintype "output"))
    )
    (net (code "226") (name "unconnected-(C17E-1-PadL1)") (class "Default")
      (node (ref "C17") (pin "L1") (pinfunction "1_L1") (pintype "output"))
    )
    (net (code "227") (name "unconnected-(C17F-1-PadP2)") (class "Default")
      (node (ref "C17") (pin "P2") (pinfunction "1_P2") (pintype "output"))
    )
    (net (code "228") (name "unconnected-(C17H-1-PadV2)") (class "Default")
      (node (ref "C17") (pin "V2") (pinfunction "1_V2") (pintype "output"))
    )
    (net (code "229") (name "unconnected-(C18-PadK2)") (class "Default")
      (node (ref "C18") (pin "K2") (pinfunction "K2_K2") (pintype "output"))
    )
    (net (code "230") (name "unconnected-(C18-PadL2)") (class "Default")
      (node (ref "C18") (pin "L2") (pinfunction "L2_L2") (pintype "output"))
    )
    (net (code "231") (name "unconnected-(C18-PadM2)") (class "Default")
      (node (ref "C18") (pin "M2") (pinfunction "M2_M2") (pintype "output"))
    )
    (net (code "232") (name "unconnected-(C18-PadN2)") (class "Default")
      (node (ref "C18") (pin "N2") (pinfunction "N2_N2") (pintype "output"))
    )
    (net (code "233") (name "unconnected-(C18-PadP2)") (class "Default")
      (node (ref "C18") (pin "P2") (pinfunction "P2_P2") (pintype "output"))
    )
    (net (code "234") (name "unconnected-(C18-PadR2)") (class "Default")
      (node (ref "C18") (pin "R2") (pinfunction "R2_R2") (pintype "output"))
    )
    (net (code "235") (name "unconnected-(C18-PadS2)") (class "Default")
      (node (ref "C18") (pin "S2") (pinfunction "S2_S2") (pintype "output"))
    )
    (net (code "236") (name "unconnected-(C18-PadT2)") (class "Default")
      (node (ref "C18") (pin "T2") (pinfunction "T2_T2") (pintype "output"))
    )
    (net (code "237") (name "unconnected-(C18-PadU2)") (class "Default")
      (node (ref "C18") (pin "U2") (pinfunction "U2_U2") (pintype "output"))
    )
    (net (code "238") (name "unconnected-(C18-PadV2)") (class "Default")
      (node (ref "C18") (pin "V2") (pinfunction "V2_V2") (pintype "output"))
    )
    (net (code "239") (name "unconnected-(C19-PadJ2)") (class "Default")
      (node (ref "C19") (pin "J2") (pinfunction "J2_J2") (pintype "output"))
    )
    (net (code "240") (name "unconnected-(C19-PadK2)") (class "Default")
      (node (ref "C19") (pin "K2") (pinfunction "K2_K2") (pintype "output"))
    )
    (net (code "241") (name "unconnected-(C19-PadN2)") (class "Default")
      (node (ref "C19") (pin "N2") (pinfunction "N2_N2") (pintype "output"))
    )
    (net (code "242") (name "unconnected-(C19-PadP2)") (class "Default")
      (node (ref "C19") (pin "P2") (pinfunction "P2_P2") (pintype "output"))
    )
    (net (code "243") (name "unconnected-(C19-PadR2)") (class "Default")
      (node (ref "C19") (pin "R2") (pinfunction "R2_R2") (pintype "output"))
    )
    (net (code "244") (name "unconnected-(C19-PadS2)") (class "Default")
      (node (ref "C19") (pin "S2") (pinfunction "S2_S2") (pintype "output"))
    )
    (net (code "245") (name "unconnected-(C19-PadT2)") (class "Default")
      (node (ref "C19") (pin "T2") (pinfunction "T2_T2") (pintype "output"))
    )
    (net (code "246") (name "unconnected-(C19-PadU2)") (class "Default")
      (node (ref "C19") (pin "U2") (pinfunction "U2_U2") (pintype "output"))
    )
    (net (code "247") (name "unconnected-(C19-PadV2)") (class "Default")
      (node (ref "C19") (pin "V2") (pinfunction "V2_V2") (pintype "output"))
    )
    (net (code "248") (name "unconnected-(C20-PadJ2)") (class "Default")
      (node (ref "C20") (pin "J2") (pinfunction "J2_J2") (pintype "output"))
    )
    (net (code "249") (name "unconnected-(C20-PadL2)") (class "Default")
      (node (ref "C20") (pin "L2") (pinfunction "L2_L2") (pintype "output"))
    )
    (net (code "250") (name "unconnected-(C20-PadM2)") (class "Default")
      (node (ref "C20") (pin "M2") (pinfunction "M2_M2") (pintype "output"))
    )
    (net (code "251") (name "unconnected-(C20-PadP2)") (class "Default")
      (node (ref "C20") (pin "P2") (pinfunction "P2_P2") (pintype "output"))
    )
    (net (code "252") (name "unconnected-(C20-PadR2)") (class "Default")
      (node (ref "C20") (pin "R2") (pinfunction "R2_R2") (pintype "output"))
    )
    (net (code "253") (name "unconnected-(C20-PadS2)") (class "Default")
      (node (ref "C20") (pin "S2") (pinfunction "S2_S2") (pintype "output"))
    )
    (net (code "254") (name "unconnected-(C20-PadT2)") (class "Default")
      (node (ref "C20") (pin "T2") (pinfunction "T2_T2") (pintype "output"))
    )
    (net (code "255") (name "unconnected-(C20-PadU2)") (class "Default")
      (node (ref "C20") (pin "U2") (pinfunction "U2_U2") (pintype "output"))
    )
    (net (code "256") (name "unconnected-(C20-PadV2)") (class "Default")
      (node (ref "C20") (pin "V2") (pinfunction "V2_V2") (pintype "output"))
    )
    (net (code "257") (name "unconnected-(D15A-1-PadE1)") (class "Default")
      (node (ref "D15") (pin "E1") (pinfunction "1_E1") (pintype "output"))
    )
    (net (code "258") (name "unconnected-(D15D-1-PadH2)") (class "Default")
      (node (ref "D15") (pin "H2") (pinfunction "1_H2") (pintype "output"))
    )
    (net (code "259") (name "unconnected-(D15E-1-PadL1)") (class "Default")
      (node (ref "D15") (pin "L1") (pinfunction "1_L1") (pintype "output"))
    )
    (net (code "260") (name "unconnected-(D15F-1-PadP2)") (class "Default")
      (node (ref "D15") (pin "P2") (pinfunction "1_P2") (pintype "output"))
    )
    (net (code "261") (name "unconnected-(D15G-1-PadS1)") (class "Default")
      (node (ref "D15") (pin "S1") (pinfunction "1_S1") (pintype "output"))
    )
    (net (code "262") (name "unconnected-(D15H-1-PadV2)") (class "Default")
      (node (ref "D15") (pin "V2") (pinfunction "1_V2") (pintype "output"))
    )
    (net (code "263") (name "unconnected-(D16A-1-PadE1)") (class "Default")
      (node (ref "D16") (pin "E1") (pinfunction "1_E1") (pintype "output"))
    )
    (net (code "264") (name "unconnected-(D16D-1-PadH2)") (class "Default")
      (node (ref "D16") (pin "H2") (pinfunction "1_H2") (pintype "output"))
    )
    (net (code "265") (name "unconnected-(D16E-1-PadL1)") (class "Default")
      (node (ref "D16") (pin "L1") (pinfunction "1_L1") (pintype "output"))
    )
    (net (code "266") (name "unconnected-(D16F-1-PadP2)") (class "Default")
      (node (ref "D16") (pin "P2") (pinfunction "1_P2") (pintype "output"))
    )
    (net (code "267") (name "unconnected-(D16G-1-PadS1)") (class "Default")
      (node (ref "D16") (pin "S1") (pinfunction "1_S1") (pintype "output"))
    )
    (net (code "268") (name "unconnected-(D16H-1-PadV2)") (class "Default")
      (node (ref "D16") (pin "V2") (pinfunction "1_V2") (pintype "output"))
    )
    (net (code "269") (name "unconnected-(D17F-1-PadP2)") (class "Default")
      (node (ref "D17") (pin "P2") (pinfunction "1_P2") (pintype "output"))
    )
    (net (code "270") (name "unconnected-(D17G-1-PadS1)") (class "Default")
      (node (ref "D17") (pin "S1") (pinfunction "1_S1") (pintype "output"))
    )
    (net (code "271") (name "unconnected-(D17H-1-PadV2)") (class "Default")
      (node (ref "D17") (pin "V2") (pinfunction "1_V2") (pintype "output"))
    )
    (net (code "272") (name "unconnected-(D19A-R2-PadE2)") (class "Default")
      (node (ref "D19") (pin "E2") (pinfunction "R2_E2") (pintype "bidirectional"))
    )
    (net (code "273") (name "unconnected-(D19B-R2-PadH2)") (class "Default")
      (node (ref "D19") (pin "H2") (pinfunction "R2_H2") (pintype "bidirectional"))
    )
    (net (code "274") (name "unconnected-(D19C-L3-PadK1)") (class "Default")
      (node (ref "D19") (pin "K1") (pinfunction "L3_K1") (pintype "bidirectional"))
    )
    (net (code "275") (name "unconnected-(D19C-R2-PadK2)") (class "Default")
      (node (ref "D19") (pin "K2") (pinfunction "R2_K2") (pintype "bidirectional"))
    )
    (net (code "276") (name "unconnected-(D19D-L3-PadN1)") (class "Default")
      (node (ref "D19") (pin "N1") (pinfunction "L3_N1") (pintype "bidirectional"))
    )
    (net (code "277") (name "unconnected-(D19D-R2-PadM2)") (class "Default")
      (node (ref "D19") (pin "M2") (pinfunction "R2_M2") (pintype "bidirectional"))
    )
  )
)
